# PinHeck.net
KiCad netlist of a schematic drawn in EAGLE
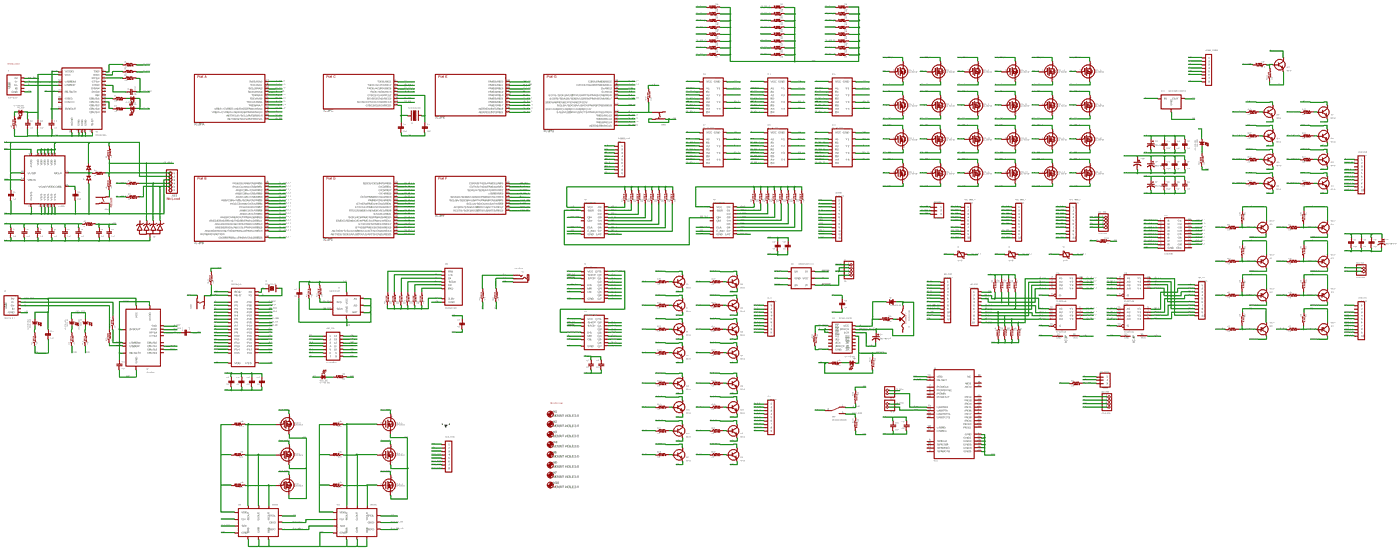
[diagram p0: schematic, sheet 1, overview]
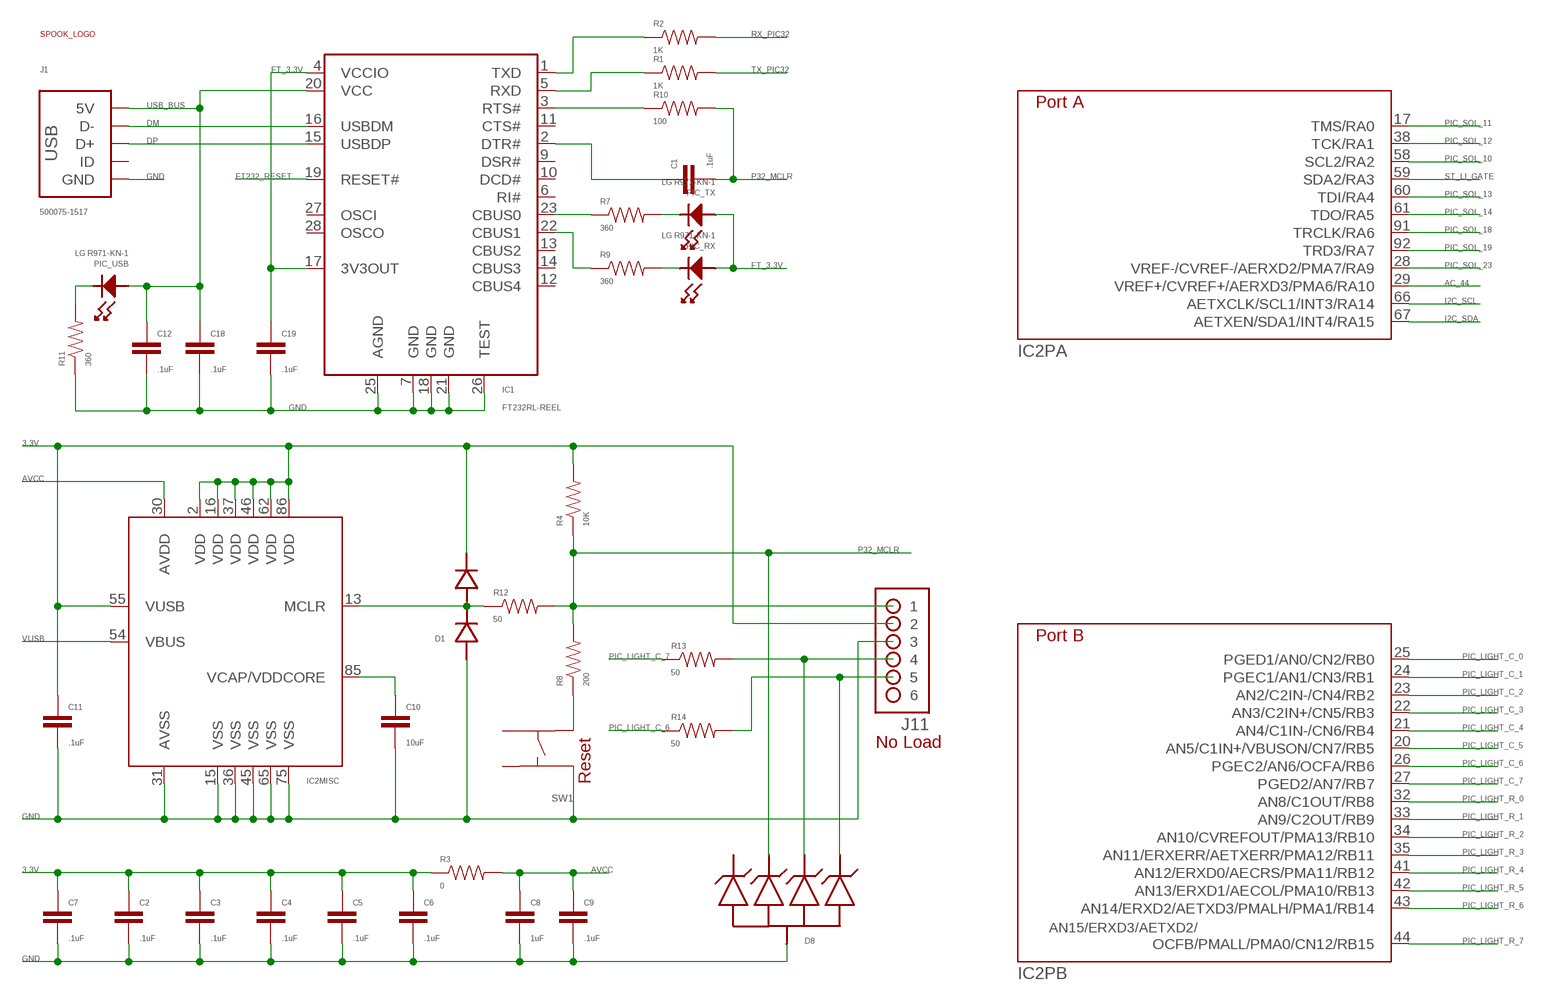
[diagram p1: schematic, sheet 1, part 1 of 9]
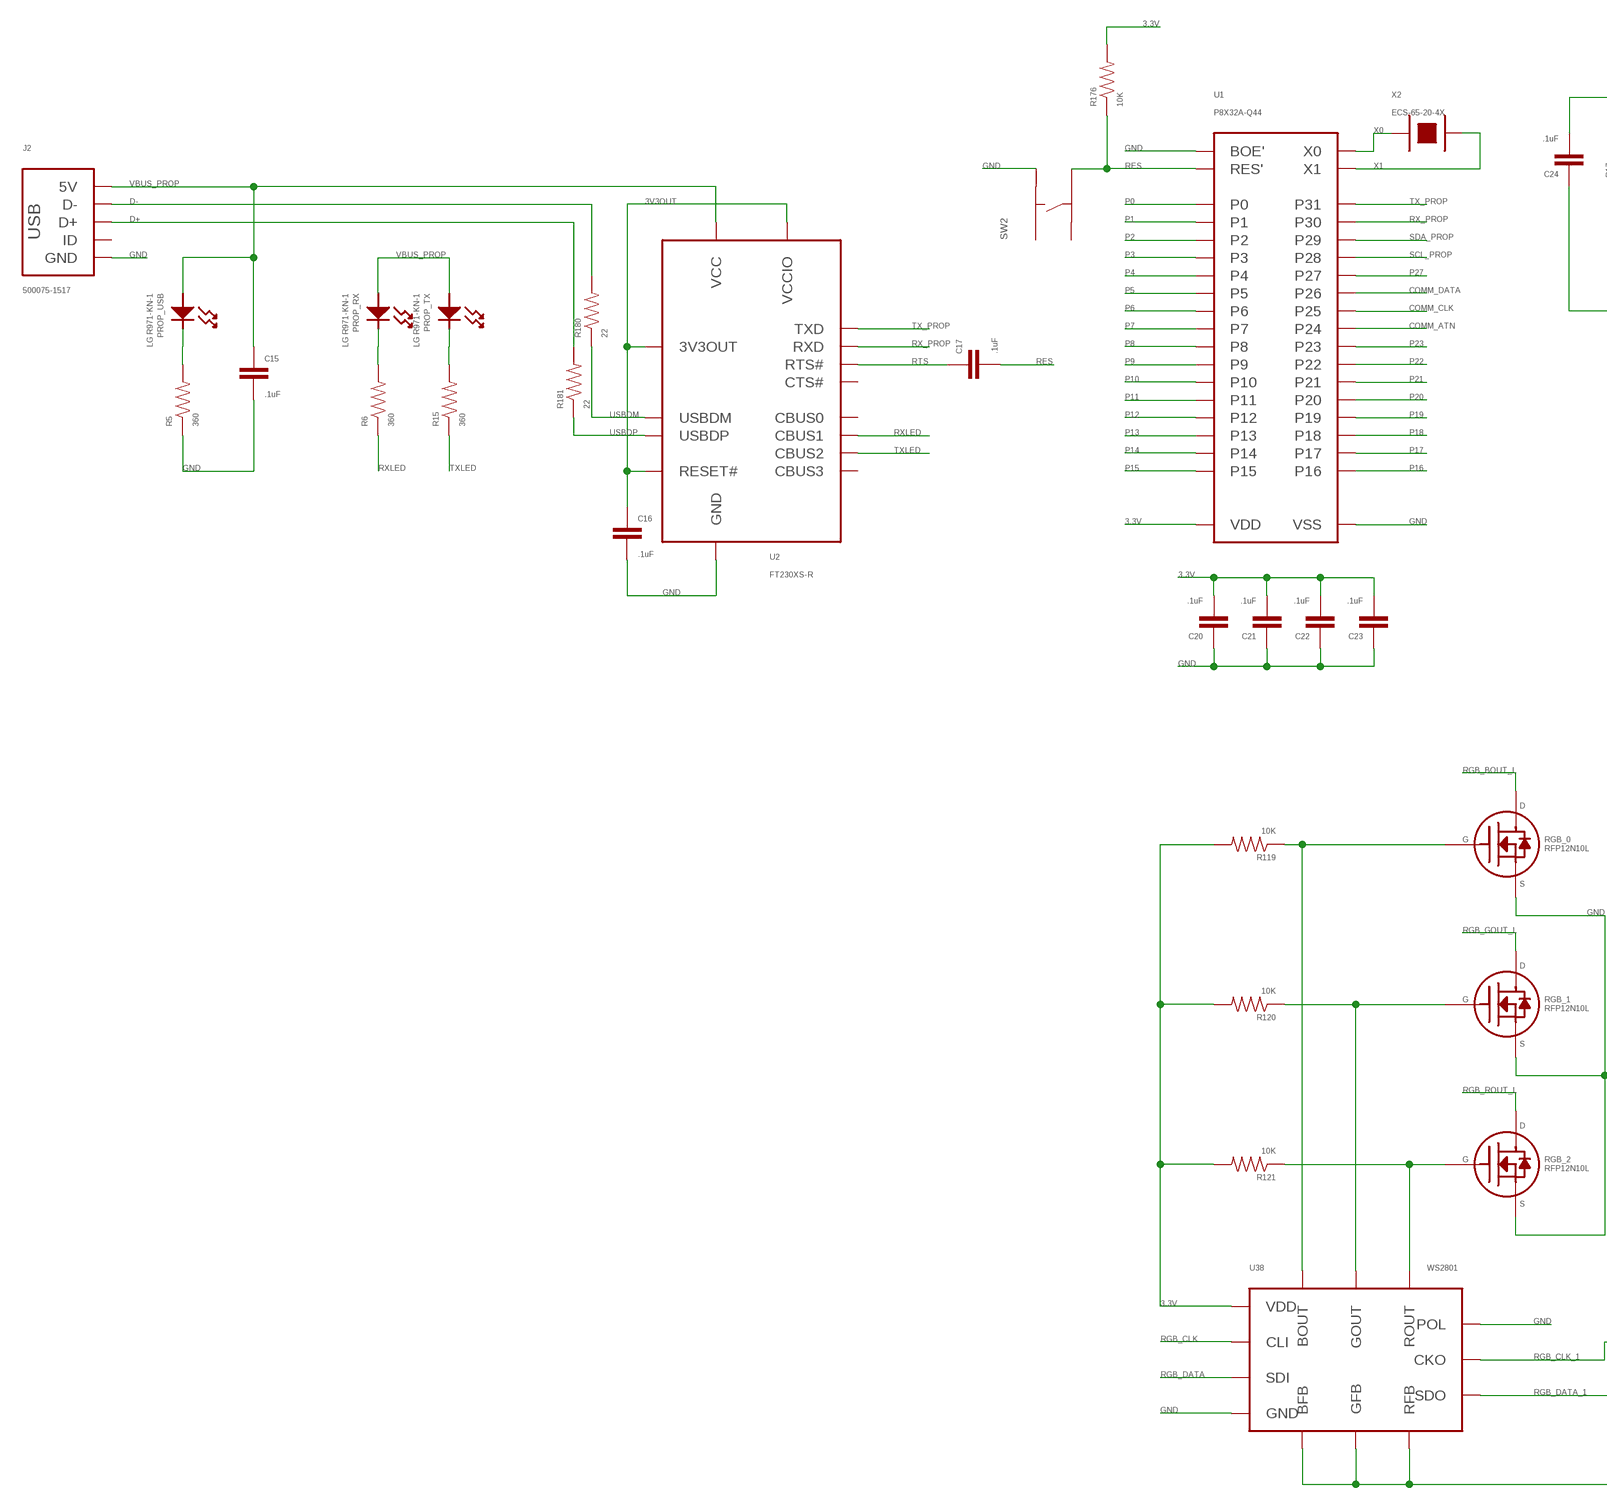
[diagram p2: schematic, sheet 1, part 2 of 9]
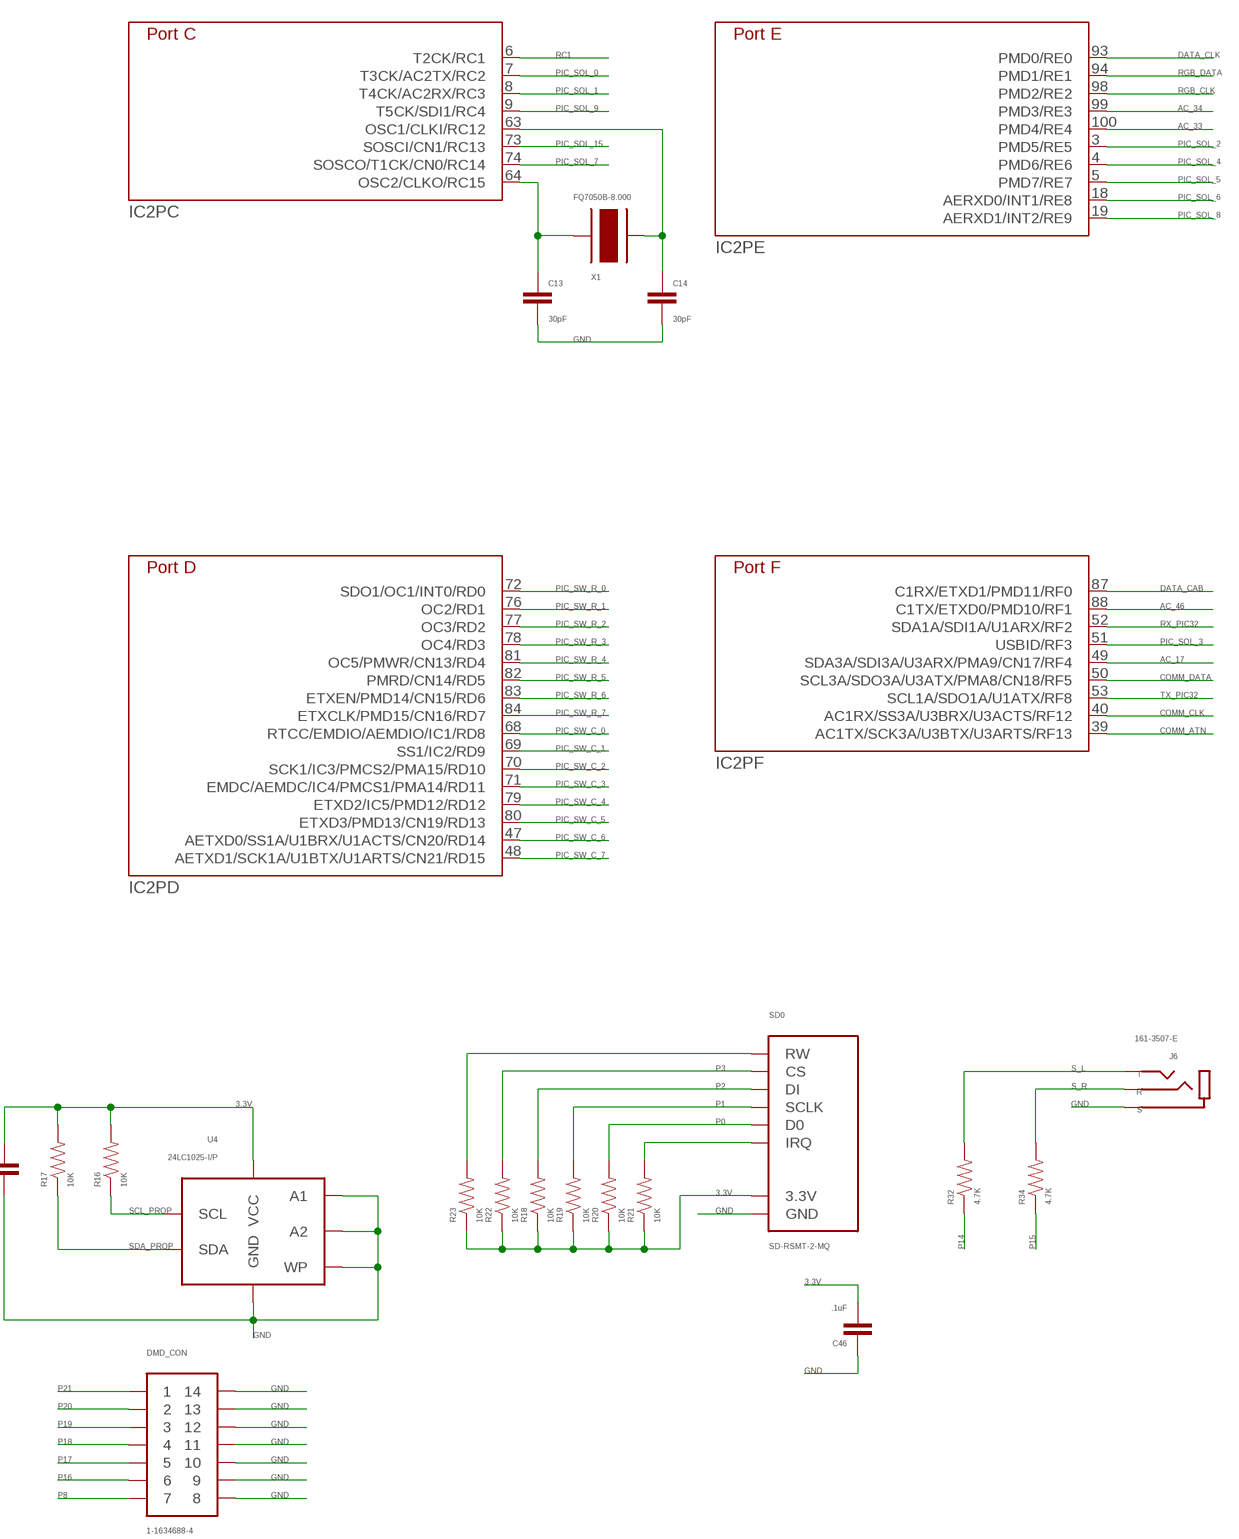
[diagram p3: schematic, sheet 1, part 3 of 9]
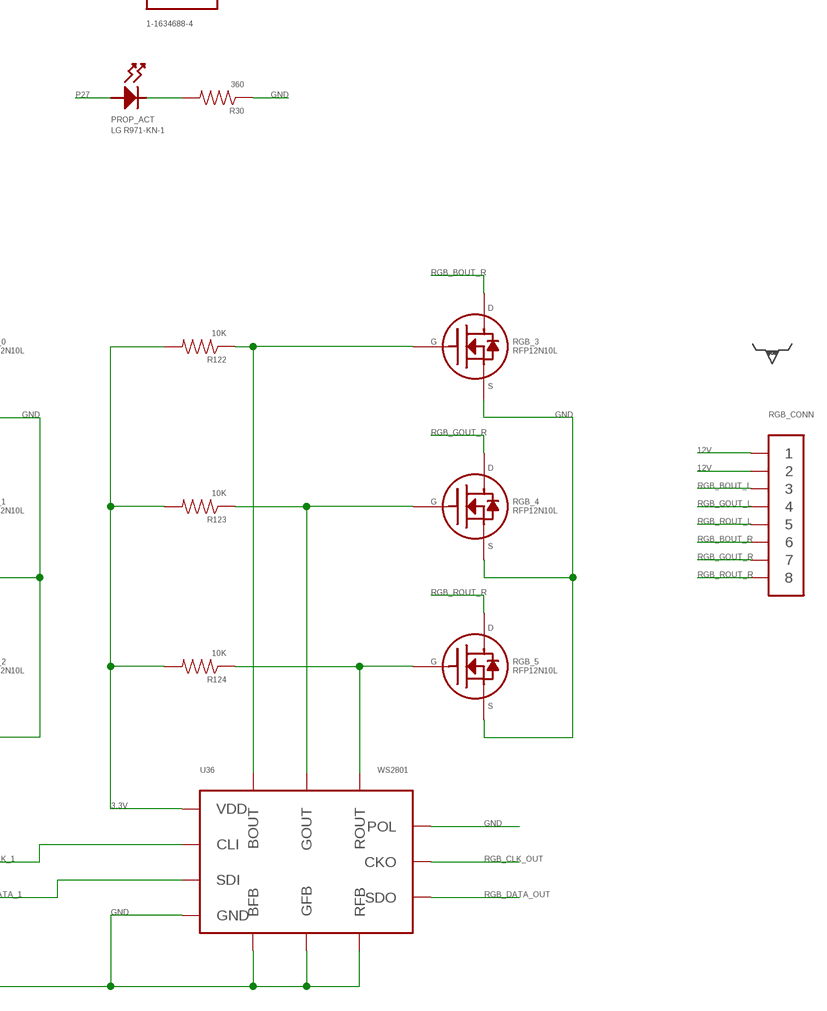
[diagram p4: schematic, sheet 1, part 4 of 9]
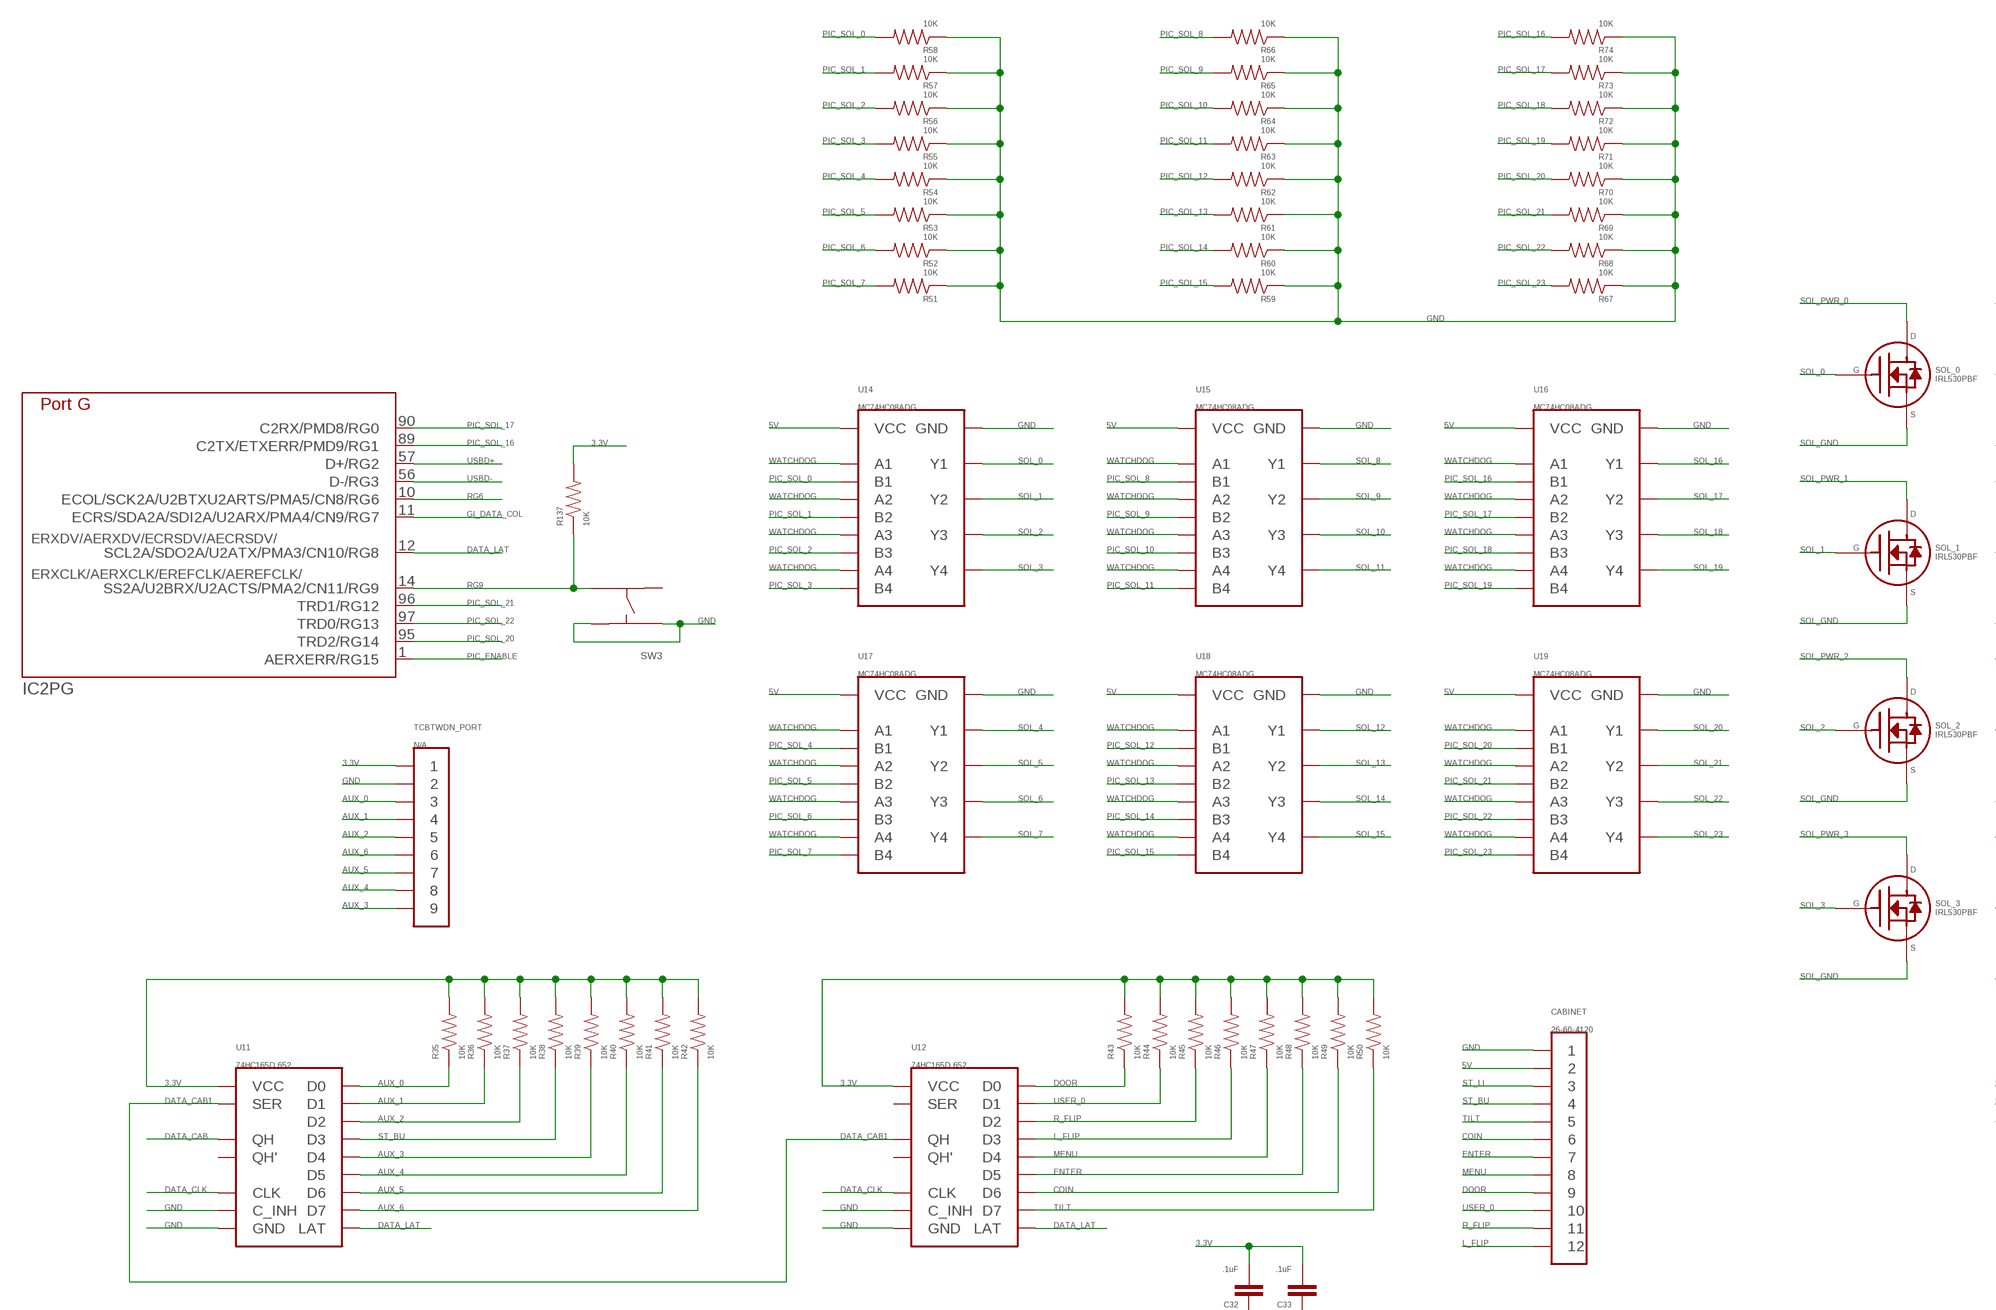
[diagram p5: schematic, sheet 1, part 5 of 9]
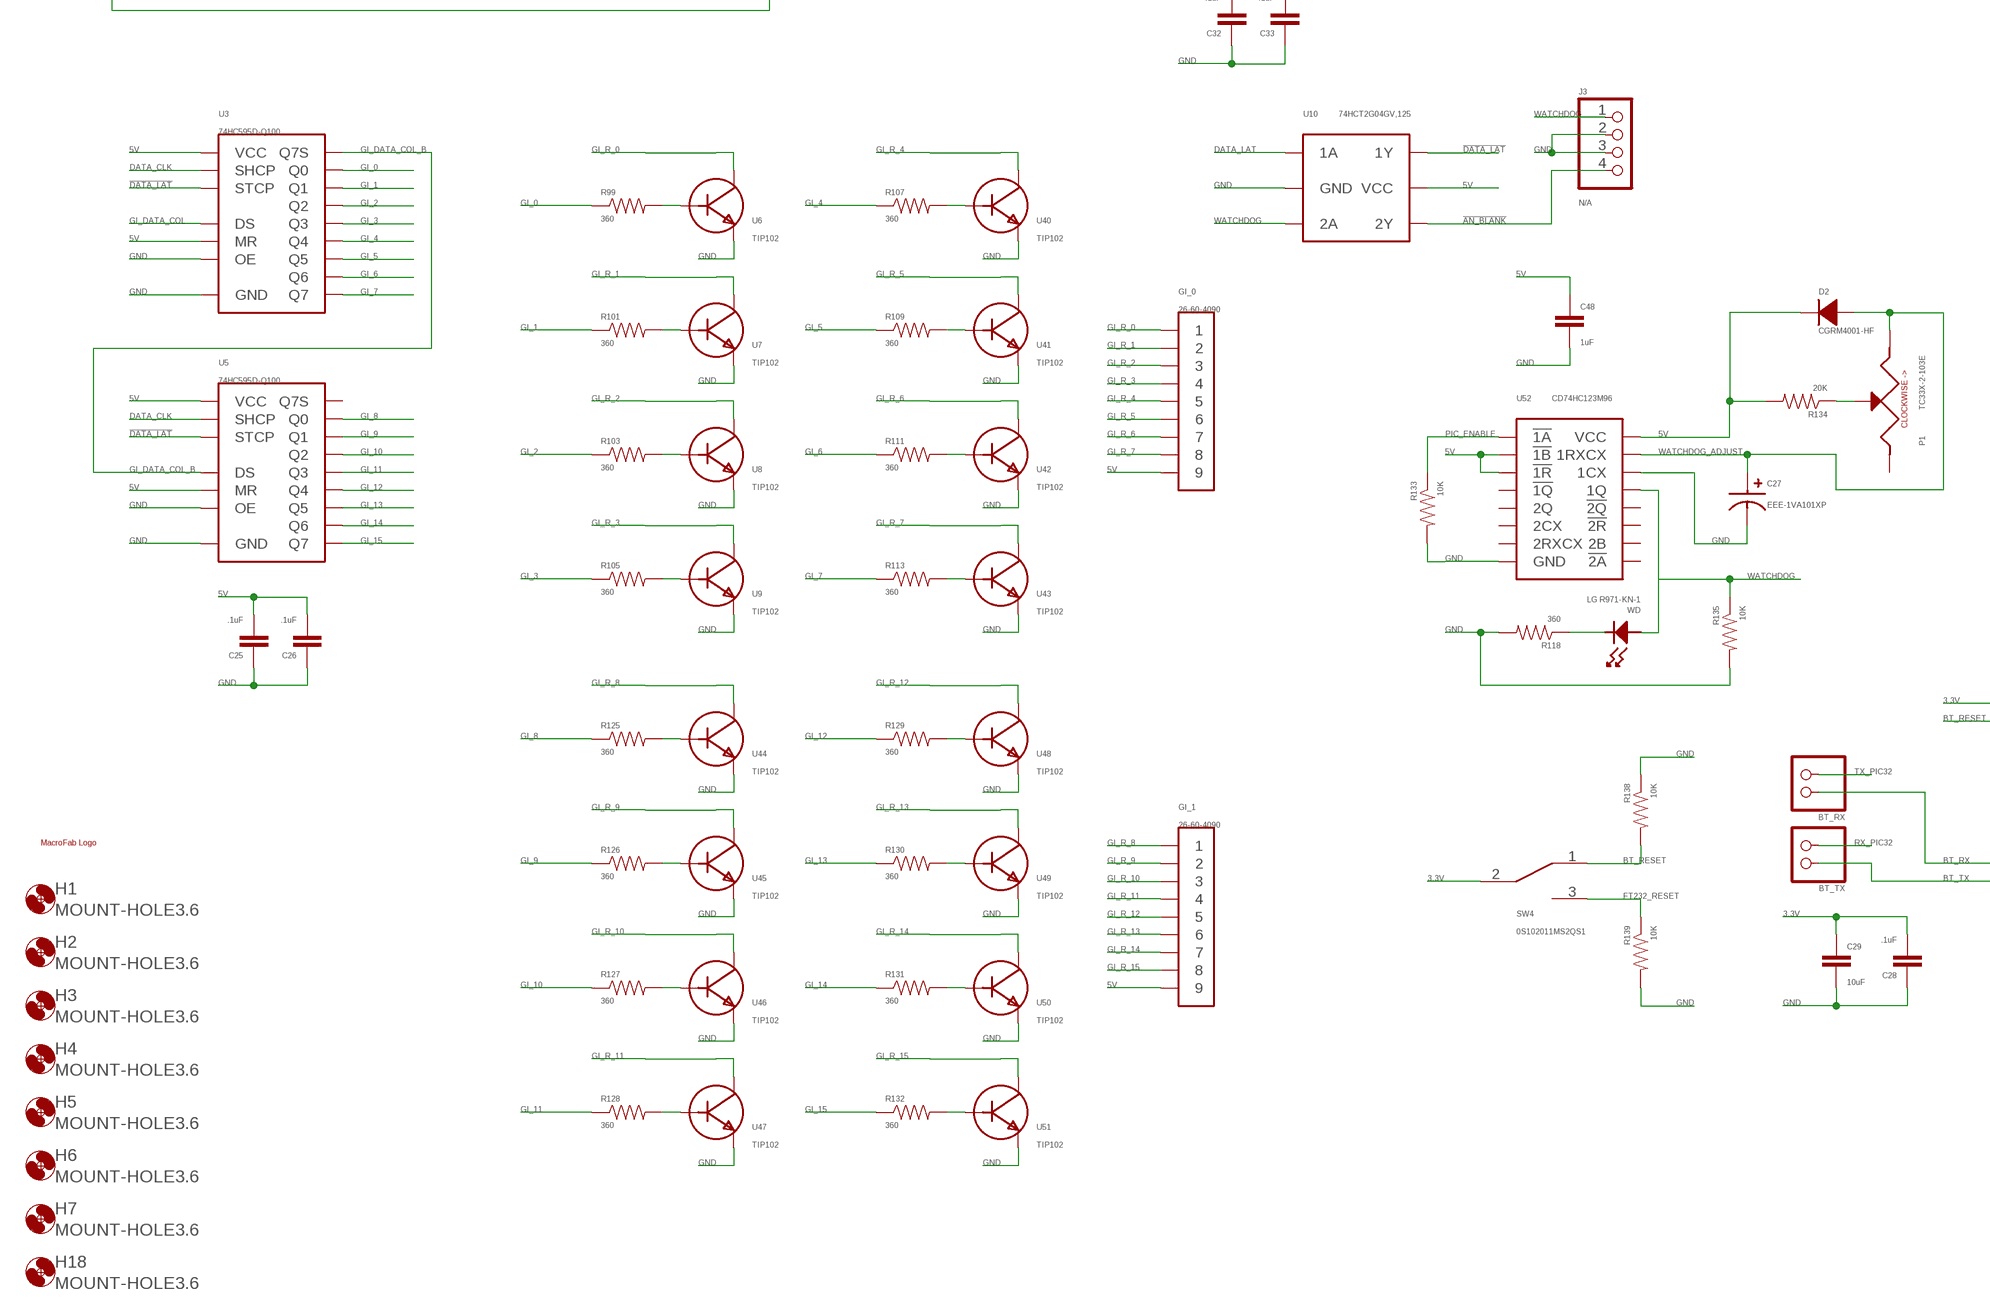
[diagram p6: schematic, sheet 1, part 6 of 9]
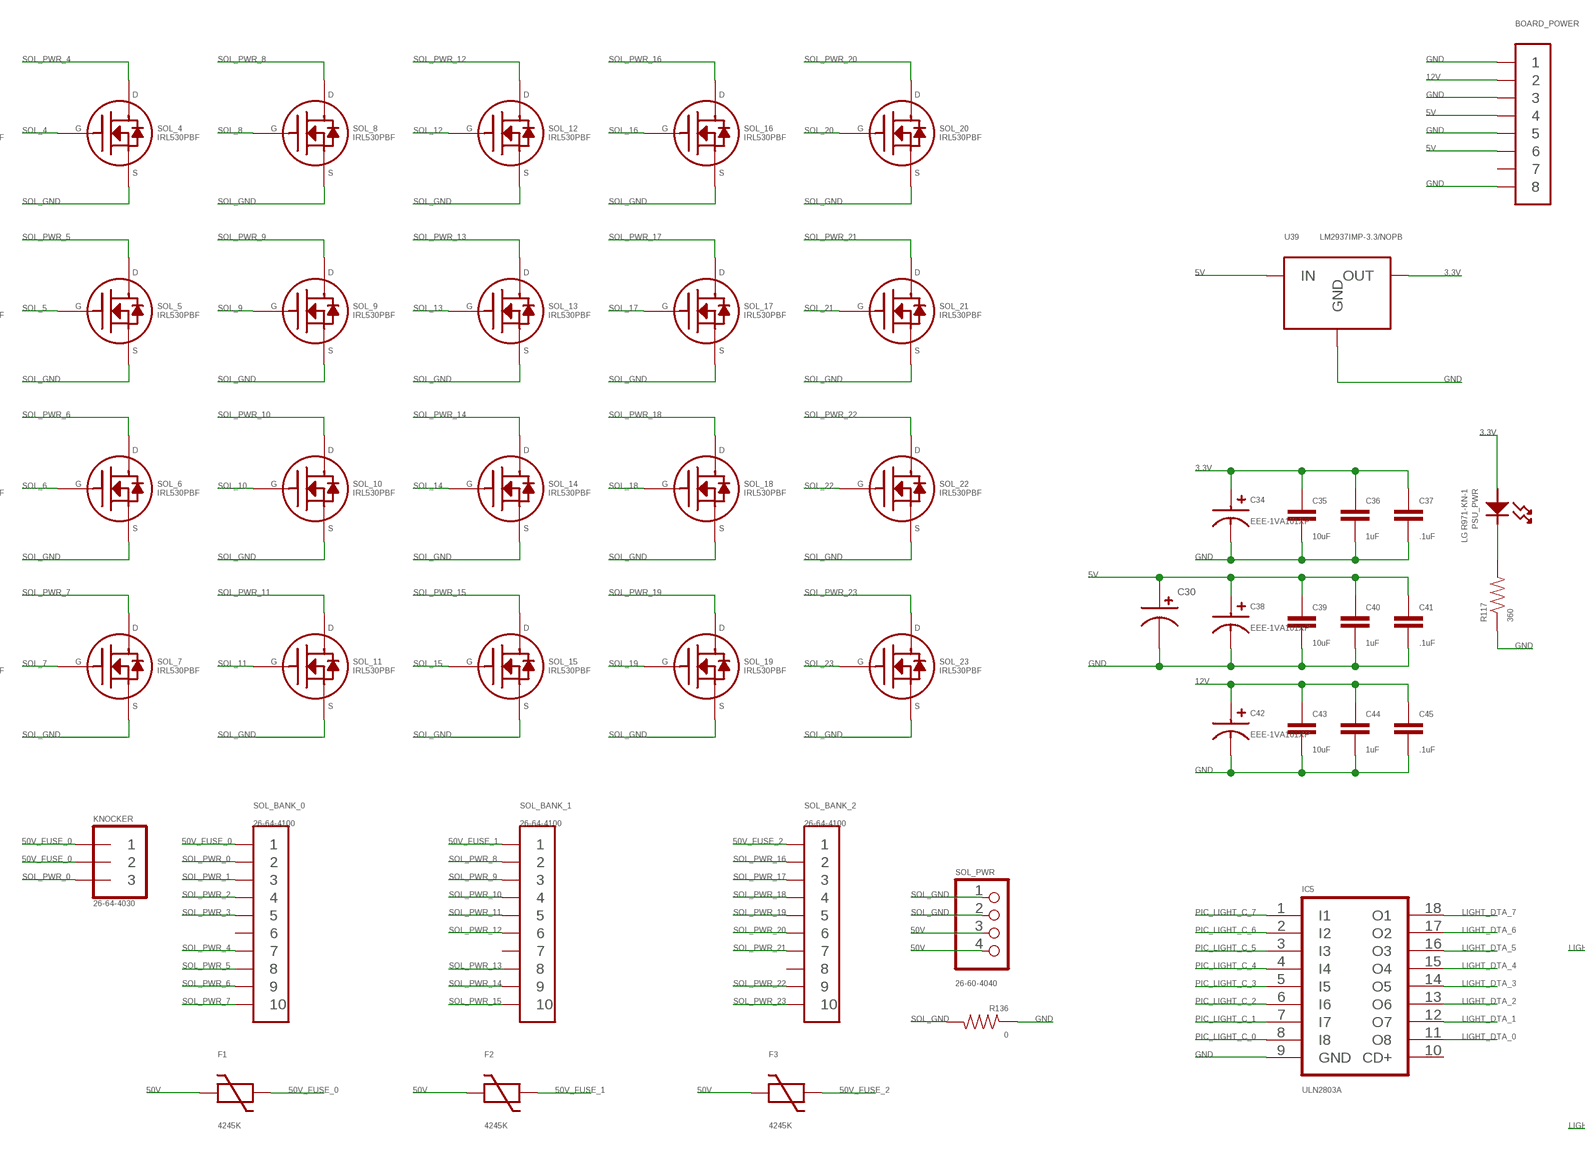
[diagram p7: schematic, sheet 1, part 7 of 9]
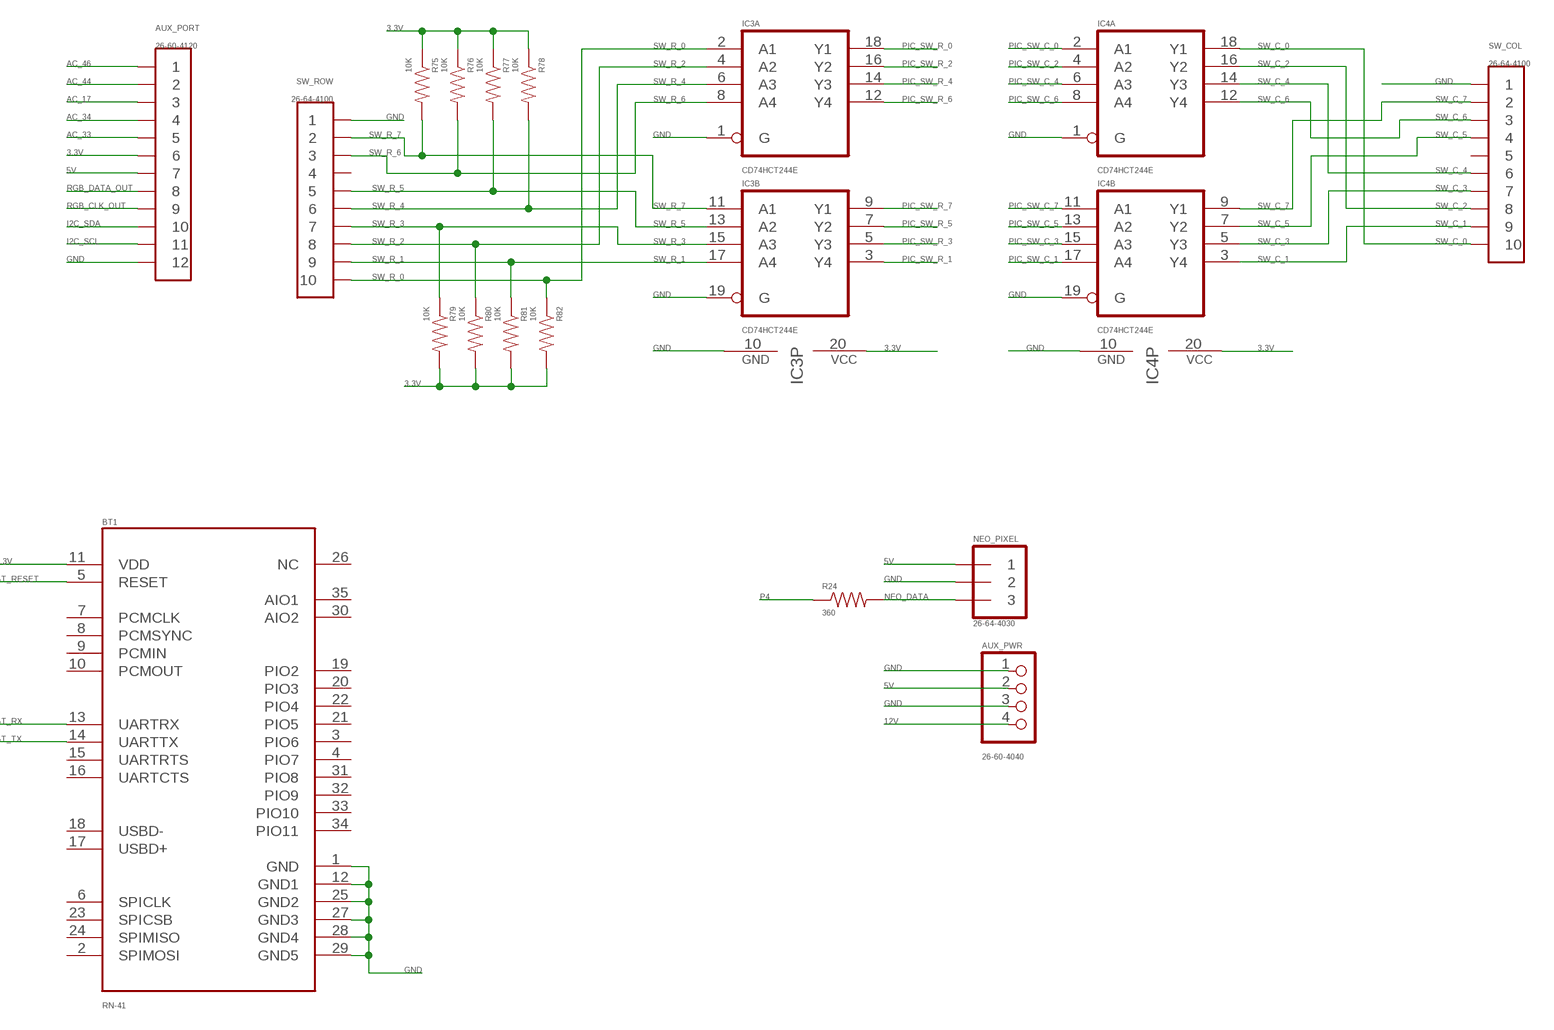
[diagram p8: schematic, sheet 1, part 8 of 9]
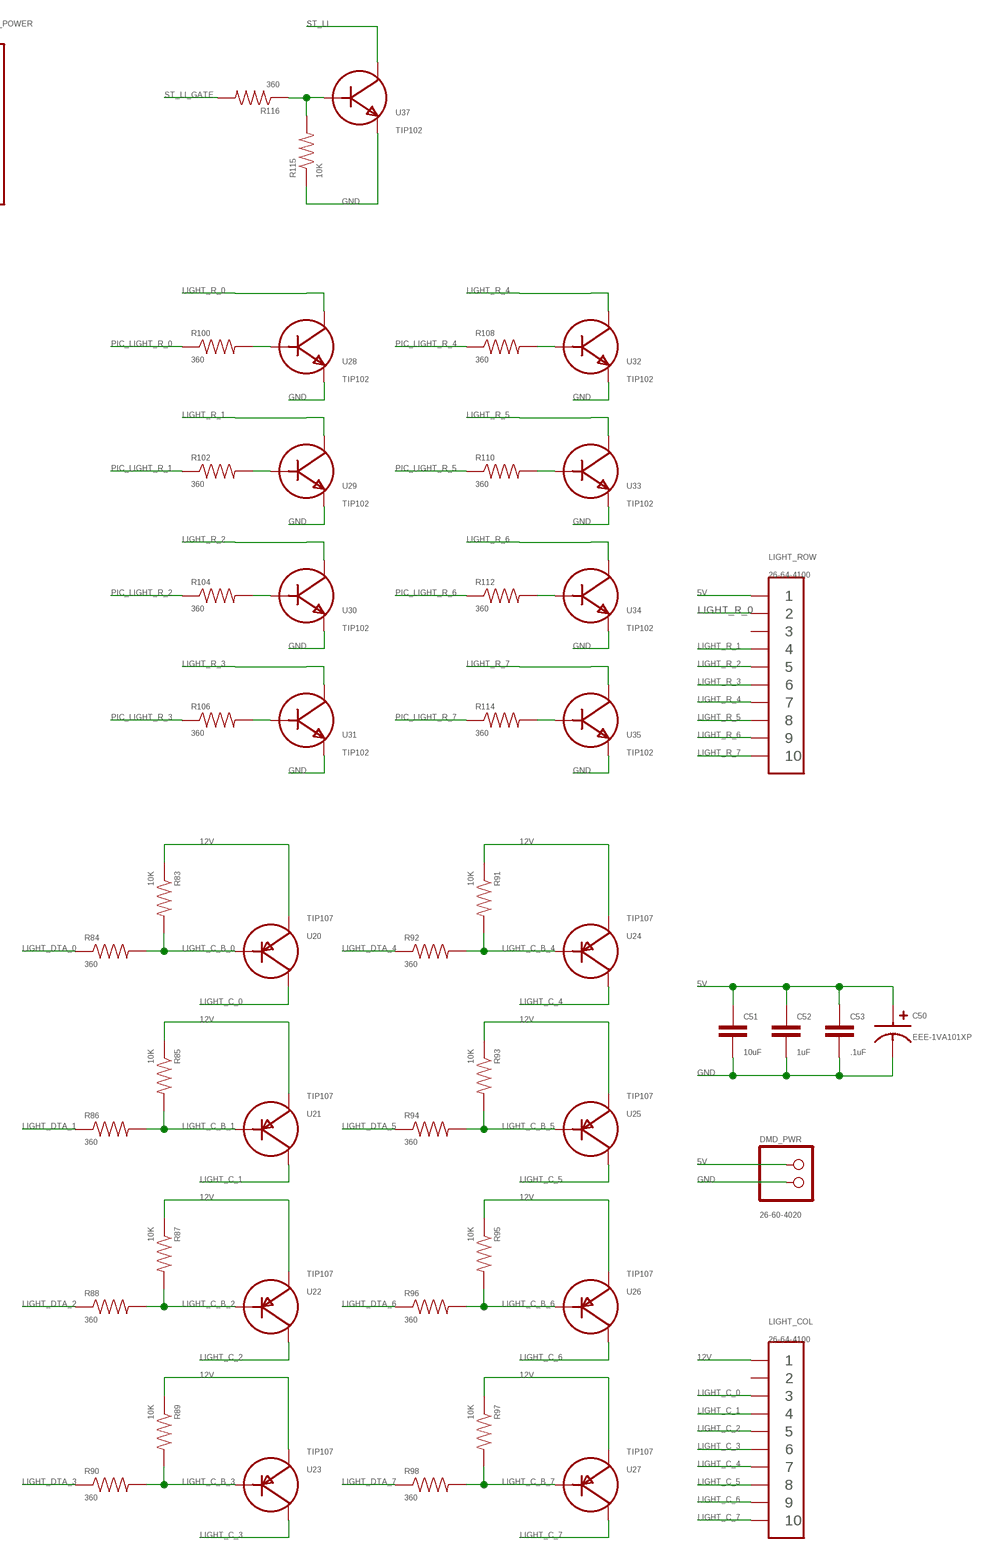
[diagram p9: schematic, sheet 1, part 9 of 9]

(export (version "E")
  (design (tool "Eeschema 10.0.6"))
  (components
    (comp (ref "AUX_PORT")
      (value "26-60-4120")
      (footprint "eagle-import:MOLEX_KK_12")
      (libsource (lib "eagle-import") (part "PH_1X12KK_12"))
    )
    (comp (ref "AUX_PWR")
      (value "26-60-4040")
      (footprint "eagle-import:MOLEX_KK_4")
      (libsource (lib "eagle-import") (part "PH_1X04KK_4"))
    )
    (comp (ref "BOARD_POWER")
      (value "PH_1X08MOLEX_KK_8")
      (footprint "eagle-import:MOLEX_KK_8")
      (libsource (lib "eagle-import") (part "PH_1X08MOLEX_KK_8"))
    )
    (comp (ref "BT1")
      (value "RN-41")
      (footprint "eagle-import:RN-41")
      (libsource (lib "eagle-import") (part "RN-41RN-41"))
    )
    (comp (ref "BT_RX")
      (value "PH_1X02HEADER_PTH")
      (footprint "eagle-import:HEADER_01X02_PTH")
      (libsource (lib "eagle-import") (part "PH_1X02HEADER_PTH"))
    )
    (comp (ref "BT_TX")
      (value "PH_1X02HEADER_PTH")
      (footprint "eagle-import:HEADER_01X02_PTH")
      (libsource (lib "eagle-import") (part "PH_1X02HEADER_PTH"))
    )
    (comp (ref "C1")
      (value ".1uF")
      (footprint "eagle-import:0805")
      (libsource (lib "eagle-import") (part "CAPACITOR_NON_POLAR0805"))
    )
    (comp (ref "C2")
      (value ".1uF")
      (footprint "eagle-import:0805")
      (libsource (lib "eagle-import") (part "CAPACITOR_NON_POLAR0805"))
    )
    (comp (ref "C3")
      (value ".1uF")
      (footprint "eagle-import:0805")
      (libsource (lib "eagle-import") (part "CAPACITOR_NON_POLAR0805"))
    )
    (comp (ref "C4")
      (value ".1uF")
      (footprint "eagle-import:0805")
      (libsource (lib "eagle-import") (part "CAPACITOR_NON_POLAR0805"))
    )
    (comp (ref "C5")
      (value ".1uF")
      (footprint "eagle-import:0805")
      (libsource (lib "eagle-import") (part "CAPACITOR_NON_POLAR0805"))
    )
    (comp (ref "C6")
      (value ".1uF")
      (footprint "eagle-import:0805")
      (libsource (lib "eagle-import") (part "CAPACITOR_NON_POLAR0805"))
    )
    (comp (ref "C7")
      (value ".1uF")
      (footprint "eagle-import:0805")
      (libsource (lib "eagle-import") (part "CAPACITOR_NON_POLAR0805"))
    )
    (comp (ref "C8")
      (value "1uF")
      (footprint "eagle-import:0805")
      (libsource (lib "eagle-import") (part "CAPACITOR_NON_POLAR0805"))
    )
    (comp (ref "C9")
      (value ".1uF")
      (footprint "eagle-import:0805")
      (libsource (lib "eagle-import") (part "CAPACITOR_NON_POLAR0805"))
    )
    (comp (ref "C10")
      (value "10uF")
      (footprint "eagle-import:1206")
      (libsource (lib "eagle-import") (part "CAPACITOR_NON_POLAR1206"))
    )
    (comp (ref "C11")
      (value ".1uF")
      (footprint "eagle-import:0805")
      (libsource (lib "eagle-import") (part "CAPACITOR_NON_POLAR0805"))
    )
    (comp (ref "C12")
      (value ".1uF")
      (footprint "eagle-import:0805")
      (libsource (lib "eagle-import") (part "CAPACITOR_NON_POLAR0805"))
    )
    (comp (ref "C13")
      (value "30pF")
      (footprint "eagle-import:0805")
      (libsource (lib "eagle-import") (part "CAPACITOR_NON_POLAR0805"))
    )
    (comp (ref "C14")
      (value "30pF")
      (footprint "eagle-import:0805")
      (libsource (lib "eagle-import") (part "CAPACITOR_NON_POLAR0805"))
    )
    (comp (ref "C15")
      (value ".1uF")
      (footprint "eagle-import:0805")
      (libsource (lib "eagle-import") (part "CAPACITOR_NON_POLAR0805"))
    )
    (comp (ref "C16")
      (value ".1uF")
      (footprint "eagle-import:0805")
      (libsource (lib "eagle-import") (part "CAPACITOR_NON_POLAR0805"))
    )
    (comp (ref "C17")
      (value ".1uF")
      (footprint "eagle-import:0805")
      (libsource (lib "eagle-import") (part "CAPACITOR_NON_POLAR0805"))
    )
    (comp (ref "C18")
      (value ".1uF")
      (footprint "eagle-import:0805")
      (libsource (lib "eagle-import") (part "CAPACITOR_NON_POLAR0805"))
    )
    (comp (ref "C19")
      (value ".1uF")
      (footprint "eagle-import:0805")
      (libsource (lib "eagle-import") (part "CAPACITOR_NON_POLAR0805"))
    )
    (comp (ref "C20")
      (value ".1uF")
      (footprint "eagle-import:0805")
      (libsource (lib "eagle-import") (part "CAPACITOR_NON_POLAR0805"))
    )
    (comp (ref "C21")
      (value ".1uF")
      (footprint "eagle-import:0805")
      (libsource (lib "eagle-import") (part "CAPACITOR_NON_POLAR0805"))
    )
    (comp (ref "C22")
      (value ".1uF")
      (footprint "eagle-import:0805")
      (libsource (lib "eagle-import") (part "CAPACITOR_NON_POLAR0805"))
    )
    (comp (ref "C23")
      (value ".1uF")
      (footprint "eagle-import:0805")
      (libsource (lib "eagle-import") (part "CAPACITOR_NON_POLAR0805"))
    )
    (comp (ref "C24")
      (value ".1uF")
      (footprint "eagle-import:0805")
      (libsource (lib "eagle-import") (part "CAPACITOR_NON_POLAR0805"))
    )
    (comp (ref "C25")
      (value ".1uF")
      (footprint "eagle-import:0805")
      (libsource (lib "eagle-import") (part "CAPACITOR_NON_POLAR0805"))
    )
    (comp (ref "C26")
      (value ".1uF")
      (footprint "eagle-import:0805")
      (libsource (lib "eagle-import") (part "CAPACITOR_NON_POLAR0805"))
    )
    (comp (ref "C27")
      (value "EEE-1VA101XP")
      (footprint "eagle-import:6.3MM_CAP_SMD")
      (libsource (lib "eagle-import") (part "CAPACITOR_POLARIZED6.3MM_SMD"))
    )
    (comp (ref "C28")
      (value ".1uF")
      (footprint "eagle-import:0805")
      (libsource (lib "eagle-import") (part "CAPACITOR_NON_POLAR0805"))
    )
    (comp (ref "C29")
      (value "10uF")
      (footprint "eagle-import:1206")
      (libsource (lib "eagle-import") (part "CAPACITOR_NON_POLAR1206"))
    )
    (comp (ref "C30")
      (value "CAPACITOR_P_12.5MM")
      (footprint "eagle-import:CP12.5MM")
      (libsource (lib "eagle-import") (part "CAPACITOR_P_12.5MM"))
    )
    (comp (ref "C32")
      (value ".1uF")
      (footprint "eagle-import:0805")
      (libsource (lib "eagle-import") (part "CAPACITOR_NON_POLAR0805"))
    )
    (comp (ref "C33")
      (value ".1uF")
      (footprint "eagle-import:0805")
      (libsource (lib "eagle-import") (part "CAPACITOR_NON_POLAR0805"))
    )
    (comp (ref "C34")
      (value "EEE-1VA101XP")
      (footprint "eagle-import:6.3MM_CAP_SMD")
      (libsource (lib "eagle-import") (part "CAPACITOR_POLARIZED6.3MM_SMD"))
    )
    (comp (ref "C35")
      (value "10uF")
      (footprint "eagle-import:1206")
      (libsource (lib "eagle-import") (part "CAPACITOR_NON_POLAR1206"))
    )
    (comp (ref "C36")
      (value "1uF")
      (footprint "eagle-import:0805")
      (libsource (lib "eagle-import") (part "CAPACITOR_NON_POLAR0805"))
    )
    (comp (ref "C37")
      (value ".1uF")
      (footprint "eagle-import:0805")
      (libsource (lib "eagle-import") (part "CAPACITOR_NON_POLAR0805"))
    )
    (comp (ref "C38")
      (value "EEE-1VA101XP")
      (footprint "eagle-import:6.3MM_CAP_SMD")
      (libsource (lib "eagle-import") (part "CAPACITOR_POLARIZED6.3MM_SMD"))
    )
    (comp (ref "C39")
      (value "10uF")
      (footprint "eagle-import:1206")
      (libsource (lib "eagle-import") (part "CAPACITOR_NON_POLAR1206"))
    )
    (comp (ref "C40")
      (value "1uF")
      (footprint "eagle-import:0805")
      (libsource (lib "eagle-import") (part "CAPACITOR_NON_POLAR0805"))
    )
    (comp (ref "C41")
      (value ".1uF")
      (footprint "eagle-import:0805")
      (libsource (lib "eagle-import") (part "CAPACITOR_NON_POLAR0805"))
    )
    (comp (ref "C42")
      (value "EEE-1VA101XP")
      (footprint "eagle-import:6.3MM_CAP_SMD")
      (libsource (lib "eagle-import") (part "CAPACITOR_POLARIZED6.3MM_SMD"))
    )
    (comp (ref "C43")
      (value "10uF")
      (footprint "eagle-import:1206")
      (libsource (lib "eagle-import") (part "CAPACITOR_NON_POLAR1206"))
    )
    (comp (ref "C44")
      (value "1uF")
      (footprint "eagle-import:0805")
      (libsource (lib "eagle-import") (part "CAPACITOR_NON_POLAR0805"))
    )
    (comp (ref "C45")
      (value ".1uF")
      (footprint "eagle-import:0805")
      (libsource (lib "eagle-import") (part "CAPACITOR_NON_POLAR0805"))
    )
    (comp (ref "C46")
      (value ".1uF")
      (footprint "eagle-import:0805")
      (libsource (lib "eagle-import") (part "CAPACITOR_NON_POLAR0805"))
    )
    (comp (ref "C48")
      (value "1uF")
      (footprint "eagle-import:0805")
      (libsource (lib "eagle-import") (part "CAPACITOR_NON_POLAR0805"))
    )
    (comp (ref "C50")
      (value "EEE-1VA101XP")
      (footprint "eagle-import:6.3MM_CAP_SMD")
      (libsource (lib "eagle-import") (part "CAPACITOR_POLARIZED6.3MM_SMD"))
    )
    (comp (ref "C51")
      (value "10uF")
      (footprint "eagle-import:1206")
      (libsource (lib "eagle-import") (part "CAPACITOR_NON_POLAR1206"))
    )
    (comp (ref "C52")
      (value "1uF")
      (footprint "eagle-import:0805")
      (libsource (lib "eagle-import") (part "CAPACITOR_NON_POLAR0805"))
    )
    (comp (ref "C53")
      (value ".1uF")
      (footprint "eagle-import:0805")
      (libsource (lib "eagle-import") (part "CAPACITOR_NON_POLAR0805"))
    )
    (comp (ref "CABINET")
      (value "26-60-4120")
      (footprint "eagle-import:MOLEX_KK_12")
      (libsource (lib "eagle-import") (part "PH_1X12KK_12"))
    )
    (comp (ref "D1")
      (value "BAV99W,115")
      (footprint "eagle-import:SOT-323")
      (libsource (lib "eagle-import") (part "BAV99W"))
    )
    (comp (ref "D2")
      (value "CGRM4001-HF")
      (footprint "eagle-import:SOD-123")
      (libsource (lib "eagle-import") (part "DIODESOD-123"))
    )
    (comp (ref "D8")
      (value "NSQA6V8AW5T2G")
      (footprint "eagle-import:SOT-323-5")
      (libsource (lib "eagle-import") (part "NSQA6V8"))
    )
    (comp (ref "DMD_CON")
      (value "1-1634688-4")
      (footprint "eagle-import:HEADER_02X07_PTH")
      (libsource (lib "eagle-import") (part "PH_2X07PTH"))
    )
    (comp (ref "DMD_PWR")
      (value "26-60-4020")
      (footprint "eagle-import:MOLEX_KK_2")
      (libsource (lib "eagle-import") (part "PH_1X02MOLEX_26-61-4020"))
    )
    (comp (ref "F1")
      (value "4245K")
      (footprint "eagle-import:4245K")
      (libsource (lib "eagle-import") (part "PTC_FUSE4245K"))
    )
    (comp (ref "F2")
      (value "4245K")
      (footprint "eagle-import:4245K")
      (libsource (lib "eagle-import") (part "PTC_FUSE4245K"))
    )
    (comp (ref "F3")
      (value "4245K")
      (footprint "eagle-import:4245K")
      (libsource (lib "eagle-import") (part "PTC_FUSE4245K"))
    )
    (comp (ref "GI_0")
      (value "26-60-4090")
      (footprint "eagle-import:MOLEX_KK_9")
      (libsource (lib "eagle-import") (part "PH_1X09MOLEX_KK_9"))
    )
    (comp (ref "GI_1")
      (value "26-60-4090")
      (footprint "eagle-import:MOLEX_KK_9")
      (libsource (lib "eagle-import") (part "PH_1X09MOLEX_KK_9"))
    )
    (comp (ref "H1")
      (value "MOUNT-HOLE3.6")
      (footprint "eagle-import:3,6")
      (libsource (lib "eagle-import") (part "MOUNT-HOLE3.6"))
    )
    (comp (ref "H2")
      (value "MOUNT-HOLE3.6")
      (footprint "eagle-import:3,6")
      (libsource (lib "eagle-import") (part "MOUNT-HOLE3.6"))
    )
    (comp (ref "H3")
      (value "MOUNT-HOLE3.6")
      (footprint "eagle-import:3,6")
      (libsource (lib "eagle-import") (part "MOUNT-HOLE3.6"))
    )
    (comp (ref "H4")
      (value "MOUNT-HOLE3.6")
      (footprint "eagle-import:3,6")
      (libsource (lib "eagle-import") (part "MOUNT-HOLE3.6"))
    )
    (comp (ref "H5")
      (value "MOUNT-HOLE3.6")
      (footprint "eagle-import:3,6")
      (libsource (lib "eagle-import") (part "MOUNT-HOLE3.6"))
    )
    (comp (ref "H6")
      (value "MOUNT-HOLE3.6")
      (footprint "eagle-import:3,6")
      (libsource (lib "eagle-import") (part "MOUNT-HOLE3.6"))
    )
    (comp (ref "H7")
      (value "MOUNT-HOLE3.6")
      (footprint "eagle-import:3,6")
      (libsource (lib "eagle-import") (part "MOUNT-HOLE3.6"))
    )
    (comp (ref "H18")
      (value "MOUNT-HOLE3.6")
      (footprint "eagle-import:3,6")
      (libsource (lib "eagle-import") (part "MOUNT-HOLE3.6"))
    )
    (comp (ref "IC1")
      (value "FT232RL-REEL")
      (footprint "eagle-import:SSOP28L")
      (libsource (lib "eagle-import") (part "FT232RL"))
    )
    (comp (ref "IC2")
      (value "PIC32MX795F512L-80I/PT")
      (footprint "eagle-import:TQ100-PT")
      (libsource (lib "eagle-import") (part "PIC32MX7X5FL-PT"))
    )
    (comp (ref "IC3")
      (value "CD74HCT244E")
      (footprint "eagle-import:DIL20")
      (libsource (lib "eagle-import") (part "74244NLS"))
    )
    (comp (ref "IC4")
      (value "CD74HCT244E")
      (footprint "eagle-import:DIL20")
      (libsource (lib "eagle-import") (part "74244NLS"))
    )
    (comp (ref "IC5")
      (value "ULN2803A")
      (footprint "eagle-import:DIL18")
      (libsource (lib "eagle-import") (part "ULN2803A"))
    )
    (comp (ref "J1")
      (value "500075-1517")
      (footprint "eagle-import:500075-1517")
      (libsource (lib "eagle-import") (part "USB500075-1517"))
    )
    (comp (ref "J2")
      (value "500075-1517")
      (footprint "eagle-import:500075-1517")
      (libsource (lib "eagle-import") (part "USB500075-1517"))
    )
    (comp (ref "J3")
      (value "N/A")
      (footprint "eagle-import:HEADER_01X04_PTH")
      (libsource (lib "eagle-import") (part "PH_1X04HEADER_PTH"))
    )
    (comp (ref "J6")
      (value "161-3507-E")
      (footprint "eagle-import:161-3507-E")
      (libsource (lib "eagle-import") (part "TRS_JACK161-3507-E"))
    )
    (comp (ref "J11")
      (value "No Load")
      (footprint "eagle-import:HDR-1X6_OFFSET")
      (libsource (lib "eagle-import") (part "HDR-1X6-OFFSET"))
    )
    (comp (ref "KNOCKER")
      (value "26-64-4030")
      (footprint "eagle-import:MOLEX_KK_3")
      (libsource (lib "eagle-import") (part "PH_1X03KK_3"))
    )
    (comp (ref "LIGHT_COL")
      (value "26-64-4100")
      (footprint "eagle-import:MOLEX_KK_10")
      (libsource (lib "eagle-import") (part "PH_1X10KK_10"))
    )
    (comp (ref "LIGHT_ROW")
      (value "26-64-4100")
      (footprint "eagle-import:MOLEX_KK_10")
      (libsource (lib "eagle-import") (part "PH_1X10KK_10"))
    )
    (comp (ref "LOGO1")
      (value "SPOOKY_LOGOSPOOKY_LOGO")
      (footprint "eagle-import:SPOOKY_LOGO")
      (libsource (lib "eagle-import") (part "SPOOKY_LOGOSPOOKY_LOGO"))
    )
    (comp (ref "NEO_PIXEL")
      (value "26-64-4030")
      (footprint "eagle-import:MOLEX_KK_3")
      (libsource (lib "eagle-import") (part "PH_1X03KK_3"))
    )
    (comp (ref "P1")
      (value "TC33X-2-103E")
      (footprint "eagle-import:TC33_TRIMMER")
      (libsource (lib "eagle-import") (part "TC33X-1TC33X-1"))
    )
    (comp (ref "PIC_RX")
      (value "LG R971-KN-1")
      (footprint "eagle-import:LED_0805")
      (libsource (lib "eagle-import") (part "LED_SINGLE0805"))
    )
    (comp (ref "PIC_TX")
      (value "LG R971-KN-1")
      (footprint "eagle-import:LED_0805")
      (libsource (lib "eagle-import") (part "LED_SINGLE0805"))
    )
    (comp (ref "PIC_USB")
      (value "LG R971-KN-1")
      (footprint "eagle-import:LED_0805")
      (libsource (lib "eagle-import") (part "LED_SINGLE0805"))
    )
    (comp (ref "PROP_ACT")
      (value "LG R971-KN-1")
      (footprint "eagle-import:LED_0805")
      (libsource (lib "eagle-import") (part "LED_SINGLE0805"))
    )
    (comp (ref "PROP_RX")
      (value "LG R971-KN-1")
      (footprint "eagle-import:LED_0805")
      (libsource (lib "eagle-import") (part "LED_SINGLE0805"))
    )
    (comp (ref "PROP_TX")
      (value "LG R971-KN-1")
      (footprint "eagle-import:LED_0805")
      (libsource (lib "eagle-import") (part "LED_SINGLE0805"))
    )
    (comp (ref "PROP_USB")
      (value "LG R971-KN-1")
      (footprint "eagle-import:LED_0805")
      (libsource (lib "eagle-import") (part "LED_SINGLE0805"))
    )
    (comp (ref "PSU_PWR")
      (value "LG R971-KN-1")
      (footprint "eagle-import:LED_0805")
      (libsource (lib "eagle-import") (part "LED_SINGLE0805"))
    )
    (comp (ref "R1")
      (value "1K")
      (footprint "eagle-import:0805")
      (libsource (lib "eagle-import") (part "RESISTOR0805"))
    )
    (comp (ref "R2")
      (value "1K")
      (footprint "eagle-import:0805")
      (libsource (lib "eagle-import") (part "RESISTOR0805"))
    )
    (comp (ref "R3")
      (value "0")
      (footprint "eagle-import:0805")
      (libsource (lib "eagle-import") (part "RESISTOR0805"))
    )
    (comp (ref "R4")
      (value "10K")
      (footprint "eagle-import:0805")
      (libsource (lib "eagle-import") (part "RESISTOR0805"))
    )
    (comp (ref "R5")
      (value "360")
      (footprint "eagle-import:0805")
      (libsource (lib "eagle-import") (part "RESISTOR0805"))
    )
    (comp (ref "R6")
      (value "360")
      (footprint "eagle-import:0805")
      (libsource (lib "eagle-import") (part "RESISTOR0805"))
    )
    (comp (ref "R7")
      (value "360")
      (footprint "eagle-import:0805")
      (libsource (lib "eagle-import") (part "RESISTOR0805"))
    )
    (comp (ref "R8")
      (value "200")
      (footprint "eagle-import:0805")
      (libsource (lib "eagle-import") (part "RESISTOR0805"))
    )
    (comp (ref "R9")
      (value "360")
      (footprint "eagle-import:0805")
      (libsource (lib "eagle-import") (part "RESISTOR0805"))
    )
    (comp (ref "R10")
      (value "100")
      (footprint "eagle-import:0805")
      (libsource (lib "eagle-import") (part "RESISTOR0805"))
    )
    (comp (ref "R11")
      (value "360")
      (footprint "eagle-import:0805")
      (libsource (lib "eagle-import") (part "RESISTOR0805"))
    )
    (comp (ref "R12")
      (value "50")
      (footprint "eagle-import:0805")
      (libsource (lib "eagle-import") (part "RESISTOR0805"))
    )
    (comp (ref "R13")
      (value "50")
      (footprint "eagle-import:0805")
      (libsource (lib "eagle-import") (part "RESISTOR0805"))
    )
    (comp (ref "R14")
      (value "50")
      (footprint "eagle-import:0805")
      (libsource (lib "eagle-import") (part "RESISTOR0805"))
    )
    (comp (ref "R15")
      (value "360")
      (footprint "eagle-import:0805")
      (libsource (lib "eagle-import") (part "RESISTOR0805"))
    )
    (comp (ref "R16")
      (value "10K")
      (footprint "eagle-import:0805")
      (libsource (lib "eagle-import") (part "RESISTOR0805"))
    )
    (comp (ref "R17")
      (value "10K")
      (footprint "eagle-import:0805")
      (libsource (lib "eagle-import") (part "RESISTOR0805"))
    )
    (comp (ref "R18")
      (value "10K")
      (footprint "eagle-import:0805")
      (libsource (lib "eagle-import") (part "RESISTOR0805"))
    )
    (comp (ref "R19")
      (value "10K")
      (footprint "eagle-import:0805")
      (libsource (lib "eagle-import") (part "RESISTOR0805"))
    )
    (comp (ref "R20")
      (value "10K")
      (footprint "eagle-import:0805")
      (libsource (lib "eagle-import") (part "RESISTOR0805"))
    )
    (comp (ref "R21")
      (value "10K")
      (footprint "eagle-import:0805")
      (libsource (lib "eagle-import") (part "RESISTOR0805"))
    )
    (comp (ref "R22")
      (value "10K")
      (footprint "eagle-import:0805")
      (libsource (lib "eagle-import") (part "RESISTOR0805"))
    )
    (comp (ref "R23")
      (value "10K")
      (footprint "eagle-import:0805")
      (libsource (lib "eagle-import") (part "RESISTOR0805"))
    )
    (comp (ref "R24")
      (value "360")
      (footprint "eagle-import:0805")
      (libsource (lib "eagle-import") (part "RESISTOR0805"))
    )
    (comp (ref "R30")
      (value "360")
      (footprint "eagle-import:0805")
      (libsource (lib "eagle-import") (part "RESISTOR0805"))
    )
    (comp (ref "R32")
      (value "4.7K")
      (footprint "eagle-import:0805")
      (libsource (lib "eagle-import") (part "RESISTOR0805"))
    )
    (comp (ref "R34")
      (value "4.7K")
      (footprint "eagle-import:0805")
      (libsource (lib "eagle-import") (part "RESISTOR0805"))
    )
    (comp (ref "R35")
      (value "10K")
      (footprint "eagle-import:0805")
      (libsource (lib "eagle-import") (part "RESISTOR0805"))
    )
    (comp (ref "R36")
      (value "10K")
      (footprint "eagle-import:0805")
      (libsource (lib "eagle-import") (part "RESISTOR0805"))
    )
    (comp (ref "R37")
      (value "10K")
      (footprint "eagle-import:0805")
      (libsource (lib "eagle-import") (part "RESISTOR0805"))
    )
    (comp (ref "R38")
      (value "10K")
      (footprint "eagle-import:0805")
      (libsource (lib "eagle-import") (part "RESISTOR0805"))
    )
    (comp (ref "R39")
      (value "10K")
      (footprint "eagle-import:0805")
      (libsource (lib "eagle-import") (part "RESISTOR0805"))
    )
    (comp (ref "R40")
      (value "10K")
      (footprint "eagle-import:0805")
      (libsource (lib "eagle-import") (part "RESISTOR0805"))
    )
    (comp (ref "R41")
      (value "10K")
      (footprint "eagle-import:0805")
      (libsource (lib "eagle-import") (part "RESISTOR0805"))
    )
    (comp (ref "R42")
      (value "10K")
      (footprint "eagle-import:0805")
      (libsource (lib "eagle-import") (part "RESISTOR0805"))
    )
    (comp (ref "R43")
      (value "10K")
      (footprint "eagle-import:0805")
      (libsource (lib "eagle-import") (part "RESISTOR0805"))
    )
    (comp (ref "R44")
      (value "10K")
      (footprint "eagle-import:0805")
      (libsource (lib "eagle-import") (part "RESISTOR0805"))
    )
    (comp (ref "R45")
      (value "10K")
      (footprint "eagle-import:0805")
      (libsource (lib "eagle-import") (part "RESISTOR0805"))
    )
    (comp (ref "R46")
      (value "10K")
      (footprint "eagle-import:0805")
      (libsource (lib "eagle-import") (part "RESISTOR0805"))
    )
    (comp (ref "R47")
      (value "10K")
      (footprint "eagle-import:0805")
      (libsource (lib "eagle-import") (part "RESISTOR0805"))
    )
    (comp (ref "R48")
      (value "10K")
      (footprint "eagle-import:0805")
      (libsource (lib "eagle-import") (part "RESISTOR0805"))
    )
    (comp (ref "R49")
      (value "10K")
      (footprint "eagle-import:0805")
      (libsource (lib "eagle-import") (part "RESISTOR0805"))
    )
    (comp (ref "R50")
      (value "10K")
      (footprint "eagle-import:0805")
      (libsource (lib "eagle-import") (part "RESISTOR0805"))
    )
    (comp (ref "R51")
      (value "10K")
      (footprint "eagle-import:0805")
      (libsource (lib "eagle-import") (part "RESISTOR0805"))
    )
    (comp (ref "R52")
      (value "10K")
      (footprint "eagle-import:0805")
      (libsource (lib "eagle-import") (part "RESISTOR0805"))
    )
    (comp (ref "R53")
      (value "10K")
      (footprint "eagle-import:0805")
      (libsource (lib "eagle-import") (part "RESISTOR0805"))
    )
    (comp (ref "R54")
      (value "10K")
      (footprint "eagle-import:0805")
      (libsource (lib "eagle-import") (part "RESISTOR0805"))
    )
    (comp (ref "R55")
      (value "10K")
      (footprint "eagle-import:0805")
      (libsource (lib "eagle-import") (part "RESISTOR0805"))
    )
    (comp (ref "R56")
      (value "10K")
      (footprint "eagle-import:0805")
      (libsource (lib "eagle-import") (part "RESISTOR0805"))
    )
    (comp (ref "R57")
      (value "10K")
      (footprint "eagle-import:0805")
      (libsource (lib "eagle-import") (part "RESISTOR0805"))
    )
    (comp (ref "R58")
      (value "10K")
      (footprint "eagle-import:0805")
      (libsource (lib "eagle-import") (part "RESISTOR0805"))
    )
    (comp (ref "R59")
      (value "10K")
      (footprint "eagle-import:0805")
      (libsource (lib "eagle-import") (part "RESISTOR0805"))
    )
    (comp (ref "R60")
      (value "10K")
      (footprint "eagle-import:0805")
      (libsource (lib "eagle-import") (part "RESISTOR0805"))
    )
    (comp (ref "R61")
      (value "10K")
      (footprint "eagle-import:0805")
      (libsource (lib "eagle-import") (part "RESISTOR0805"))
    )
    (comp (ref "R62")
      (value "10K")
      (footprint "eagle-import:0805")
      (libsource (lib "eagle-import") (part "RESISTOR0805"))
    )
    (comp (ref "R63")
      (value "10K")
      (footprint "eagle-import:0805")
      (libsource (lib "eagle-import") (part "RESISTOR0805"))
    )
    (comp (ref "R64")
      (value "10K")
      (footprint "eagle-import:0805")
      (libsource (lib "eagle-import") (part "RESISTOR0805"))
    )
    (comp (ref "R65")
      (value "10K")
      (footprint "eagle-import:0805")
      (libsource (lib "eagle-import") (part "RESISTOR0805"))
    )
    (comp (ref "R66")
      (value "10K")
      (footprint "eagle-import:0805")
      (libsource (lib "eagle-import") (part "RESISTOR0805"))
    )
    (comp (ref "R67")
      (value "10K")
      (footprint "eagle-import:0805")
      (libsource (lib "eagle-import") (part "RESISTOR0805"))
    )
    (comp (ref "R68")
      (value "10K")
      (footprint "eagle-import:0805")
      (libsource (lib "eagle-import") (part "RESISTOR0805"))
    )
    (comp (ref "R69")
      (value "10K")
      (footprint "eagle-import:0805")
      (libsource (lib "eagle-import") (part "RESISTOR0805"))
    )
    (comp (ref "R70")
      (value "10K")
      (footprint "eagle-import:0805")
      (libsource (lib "eagle-import") (part "RESISTOR0805"))
    )
    (comp (ref "R71")
      (value "10K")
      (footprint "eagle-import:0805")
      (libsource (lib "eagle-import") (part "RESISTOR0805"))
    )
    (comp (ref "R72")
      (value "10K")
      (footprint "eagle-import:0805")
      (libsource (lib "eagle-import") (part "RESISTOR0805"))
    )
    (comp (ref "R73")
      (value "10K")
      (footprint "eagle-import:0805")
      (libsource (lib "eagle-import") (part "RESISTOR0805"))
    )
    (comp (ref "R74")
      (value "10K")
      (footprint "eagle-import:0805")
      (libsource (lib "eagle-import") (part "RESISTOR0805"))
    )
    (comp (ref "R75")
      (value "10K")
      (footprint "eagle-import:0805")
      (libsource (lib "eagle-import") (part "RESISTOR0805"))
    )
    (comp (ref "R76")
      (value "10K")
      (footprint "eagle-import:0805")
      (libsource (lib "eagle-import") (part "RESISTOR0805"))
    )
    (comp (ref "R77")
      (value "10K")
      (footprint "eagle-import:0805")
      (libsource (lib "eagle-import") (part "RESISTOR0805"))
    )
    (comp (ref "R78")
      (value "10K")
      (footprint "eagle-import:0805")
      (libsource (lib "eagle-import") (part "RESISTOR0805"))
    )
    (comp (ref "R79")
      (value "10K")
      (footprint "eagle-import:0805")
      (libsource (lib "eagle-import") (part "RESISTOR0805"))
    )
    (comp (ref "R80")
      (value "10K")
      (footprint "eagle-import:0805")
      (libsource (lib "eagle-import") (part "RESISTOR0805"))
    )
    (comp (ref "R81")
      (value "10K")
      (footprint "eagle-import:0805")
      (libsource (lib "eagle-import") (part "RESISTOR0805"))
    )
    (comp (ref "R82")
      (value "10K")
      (footprint "eagle-import:0805")
      (libsource (lib "eagle-import") (part "RESISTOR0805"))
    )
    (comp (ref "R83")
      (value "10K")
      (footprint "eagle-import:0805")
      (libsource (lib "eagle-import") (part "RESISTOR0805"))
    )
    (comp (ref "R84")
      (value "360")
      (footprint "eagle-import:0805")
      (libsource (lib "eagle-import") (part "RESISTOR0805"))
    )
    (comp (ref "R85")
      (value "10K")
      (footprint "eagle-import:0805")
      (libsource (lib "eagle-import") (part "RESISTOR0805"))
    )
    (comp (ref "R86")
      (value "360")
      (footprint "eagle-import:0805")
      (libsource (lib "eagle-import") (part "RESISTOR0805"))
    )
    (comp (ref "R87")
      (value "10K")
      (footprint "eagle-import:0805")
      (libsource (lib "eagle-import") (part "RESISTOR0805"))
    )
    (comp (ref "R88")
      (value "360")
      (footprint "eagle-import:0805")
      (libsource (lib "eagle-import") (part "RESISTOR0805"))
    )
    (comp (ref "R89")
      (value "10K")
      (footprint "eagle-import:0805")
      (libsource (lib "eagle-import") (part "RESISTOR0805"))
    )
    (comp (ref "R90")
      (value "360")
      (footprint "eagle-import:0805")
      (libsource (lib "eagle-import") (part "RESISTOR0805"))
    )
    (comp (ref "R91")
      (value "10K")
      (footprint "eagle-import:0805")
      (libsource (lib "eagle-import") (part "RESISTOR0805"))
    )
    (comp (ref "R92")
      (value "360")
      (footprint "eagle-import:0805")
      (libsource (lib "eagle-import") (part "RESISTOR0805"))
    )
    (comp (ref "R93")
      (value "10K")
      (footprint "eagle-import:0805")
      (libsource (lib "eagle-import") (part "RESISTOR0805"))
    )
    (comp (ref "R94")
      (value "360")
      (footprint "eagle-import:0805")
      (libsource (lib "eagle-import") (part "RESISTOR0805"))
    )
    (comp (ref "R95")
      (value "10K")
      (footprint "eagle-import:0805")
      (libsource (lib "eagle-import") (part "RESISTOR0805"))
    )
    (comp (ref "R96")
      (value "360")
      (footprint "eagle-import:0805")
      (libsource (lib "eagle-import") (part "RESISTOR0805"))
    )
    (comp (ref "R97")
      (value "10K")
      (footprint "eagle-import:0805")
      (libsource (lib "eagle-import") (part "RESISTOR0805"))
    )
    (comp (ref "R98")
      (value "360")
      (footprint "eagle-import:0805")
      (libsource (lib "eagle-import") (part "RESISTOR0805"))
    )
    (comp (ref "R99")
      (value "360")
      (footprint "eagle-import:0805")
      (libsource (lib "eagle-import") (part "RESISTOR0805"))
    )
    (comp (ref "R100")
      (value "360")
      (footprint "eagle-import:0805")
      (libsource (lib "eagle-import") (part "RESISTOR0805"))
    )
    (comp (ref "R101")
      (value "360")
      (footprint "eagle-import:0805")
      (libsource (lib "eagle-import") (part "RESISTOR0805"))
    )
    (comp (ref "R102")
      (value "360")
      (footprint "eagle-import:0805")
      (libsource (lib "eagle-import") (part "RESISTOR0805"))
    )
    (comp (ref "R103")
      (value "360")
      (footprint "eagle-import:0805")
      (libsource (lib "eagle-import") (part "RESISTOR0805"))
    )
    (comp (ref "R104")
      (value "360")
      (footprint "eagle-import:0805")
      (libsource (lib "eagle-import") (part "RESISTOR0805"))
    )
    (comp (ref "R105")
      (value "360")
      (footprint "eagle-import:0805")
      (libsource (lib "eagle-import") (part "RESISTOR0805"))
    )
    (comp (ref "R106")
      (value "360")
      (footprint "eagle-import:0805")
      (libsource (lib "eagle-import") (part "RESISTOR0805"))
    )
    (comp (ref "R107")
      (value "360")
      (footprint "eagle-import:0805")
      (libsource (lib "eagle-import") (part "RESISTOR0805"))
    )
    (comp (ref "R108")
      (value "360")
      (footprint "eagle-import:0805")
      (libsource (lib "eagle-import") (part "RESISTOR0805"))
    )
    (comp (ref "R109")
      (value "360")
      (footprint "eagle-import:0805")
      (libsource (lib "eagle-import") (part "RESISTOR0805"))
    )
    (comp (ref "R110")
      (value "360")
      (footprint "eagle-import:0805")
      (libsource (lib "eagle-import") (part "RESISTOR0805"))
    )
    (comp (ref "R111")
      (value "360")
      (footprint "eagle-import:0805")
      (libsource (lib "eagle-import") (part "RESISTOR0805"))
    )
    (comp (ref "R112")
      (value "360")
      (footprint "eagle-import:0805")
      (libsource (lib "eagle-import") (part "RESISTOR0805"))
    )
    (comp (ref "R113")
      (value "360")
      (footprint "eagle-import:0805")
      (libsource (lib "eagle-import") (part "RESISTOR0805"))
    )
    (comp (ref "R114")
      (value "360")
      (footprint "eagle-import:0805")
      (libsource (lib "eagle-import") (part "RESISTOR0805"))
    )
    (comp (ref "R115")
      (value "10K")
      (footprint "eagle-import:0805")
      (libsource (lib "eagle-import") (part "RESISTOR0805"))
    )
    (comp (ref "R116")
      (value "360")
      (footprint "eagle-import:0805")
      (libsource (lib "eagle-import") (part "RESISTOR0805"))
    )
    (comp (ref "R117")
      (value "360")
      (footprint "eagle-import:0805")
      (libsource (lib "eagle-import") (part "RESISTOR0805"))
    )
    (comp (ref "R118")
      (value "360")
      (footprint "eagle-import:0805")
      (libsource (lib "eagle-import") (part "RESISTOR0805"))
    )
    (comp (ref "R119")
      (value "10K")
      (footprint "eagle-import:0805")
      (libsource (lib "eagle-import") (part "RESISTOR0805"))
    )
    (comp (ref "R120")
      (value "10K")
      (footprint "eagle-import:0805")
      (libsource (lib "eagle-import") (part "RESISTOR0805"))
    )
    (comp (ref "R121")
      (value "10K")
      (footprint "eagle-import:0805")
      (libsource (lib "eagle-import") (part "RESISTOR0805"))
    )
    (comp (ref "R122")
      (value "10K")
      (footprint "eagle-import:0805")
      (libsource (lib "eagle-import") (part "RESISTOR0805"))
    )
    (comp (ref "R123")
      (value "10K")
      (footprint "eagle-import:0805")
      (libsource (lib "eagle-import") (part "RESISTOR0805"))
    )
    (comp (ref "R124")
      (value "10K")
      (footprint "eagle-import:0805")
      (libsource (lib "eagle-import") (part "RESISTOR0805"))
    )
    (comp (ref "R125")
      (value "360")
      (footprint "eagle-import:0805")
      (libsource (lib "eagle-import") (part "RESISTOR0805"))
    )
    (comp (ref "R126")
      (value "360")
      (footprint "eagle-import:0805")
      (libsource (lib "eagle-import") (part "RESISTOR0805"))
    )
    (comp (ref "R127")
      (value "360")
      (footprint "eagle-import:0805")
      (libsource (lib "eagle-import") (part "RESISTOR0805"))
    )
    (comp (ref "R128")
      (value "360")
      (footprint "eagle-import:0805")
      (libsource (lib "eagle-import") (part "RESISTOR0805"))
    )
    (comp (ref "R129")
      (value "360")
      (footprint "eagle-import:0805")
      (libsource (lib "eagle-import") (part "RESISTOR0805"))
    )
    (comp (ref "R130")
      (value "360")
      (footprint "eagle-import:0805")
      (libsource (lib "eagle-import") (part "RESISTOR0805"))
    )
    (comp (ref "R131")
      (value "360")
      (footprint "eagle-import:0805")
      (libsource (lib "eagle-import") (part "RESISTOR0805"))
    )
    (comp (ref "R132")
      (value "360")
      (footprint "eagle-import:0805")
      (libsource (lib "eagle-import") (part "RESISTOR0805"))
    )
    (comp (ref "R133")
      (value "10K")
      (footprint "eagle-import:0805")
      (libsource (lib "eagle-import") (part "RESISTOR0805"))
    )
    (comp (ref "R134")
      (value "20K")
      (footprint "eagle-import:0805")
      (libsource (lib "eagle-import") (part "RESISTOR0805"))
    )
    (comp (ref "R135")
      (value "10K")
      (footprint "eagle-import:0805")
      (libsource (lib "eagle-import") (part "RESISTOR0805"))
    )
    (comp (ref "R136")
      (value "0")
      (footprint "eagle-import:0805")
      (libsource (lib "eagle-import") (part "RESISTOR0805"))
    )
    (comp (ref "R137")
      (value "10K")
      (footprint "eagle-import:0805")
      (libsource (lib "eagle-import") (part "RESISTOR0805"))
    )
    (comp (ref "R138")
      (value "10K")
      (footprint "eagle-import:0805")
      (libsource (lib "eagle-import") (part "RESISTOR0805"))
    )
    (comp (ref "R139")
      (value "10K")
      (footprint "eagle-import:0805")
      (libsource (lib "eagle-import") (part "RESISTOR0805"))
    )
    (comp (ref "R176")
      (value "10K")
      (footprint "eagle-import:0805")
      (libsource (lib "eagle-import") (part "RESISTOR0805"))
    )
    (comp (ref "R180")
      (value "22")
      (footprint "eagle-import:0805")
      (libsource (lib "eagle-import") (part "RESISTOR0805"))
    )
    (comp (ref "R181")
      (value "22")
      (footprint "eagle-import:0805")
      (libsource (lib "eagle-import") (part "RESISTOR0805"))
    )
    (comp (ref "RGB_0")
      (value "RFP12N10L")
      (footprint "eagle-import:TO-220AB")
      (libsource (lib "eagle-import") (part "MOSFET_N-CHANNEL_SINGLETO-220AB"))
    )
    (comp (ref "RGB_1")
      (value "RFP12N10L")
      (footprint "eagle-import:TO-220AB")
      (libsource (lib "eagle-import") (part "MOSFET_N-CHANNEL_SINGLETO-220AB"))
    )
    (comp (ref "RGB_2")
      (value "RFP12N10L")
      (footprint "eagle-import:TO-220AB")
      (libsource (lib "eagle-import") (part "MOSFET_N-CHANNEL_SINGLETO-220AB"))
    )
    (comp (ref "RGB_3")
      (value "RFP12N10L")
      (footprint "eagle-import:TO-220AB")
      (libsource (lib "eagle-import") (part "MOSFET_N-CHANNEL_SINGLETO-220AB"))
    )
    (comp (ref "RGB_4")
      (value "RFP12N10L")
      (footprint "eagle-import:TO-220AB")
      (libsource (lib "eagle-import") (part "MOSFET_N-CHANNEL_SINGLETO-220AB"))
    )
    (comp (ref "RGB_5")
      (value "RFP12N10L")
      (footprint "eagle-import:TO-220AB")
      (libsource (lib "eagle-import") (part "MOSFET_N-CHANNEL_SINGLETO-220AB"))
    )
    (comp (ref "RGB_CONN")
      (value "26-60-4080")
      (footprint "eagle-import:MOLEX_KK_8")
      (libsource (lib "eagle-import") (part "PH_1X08MOLEX_KK_8"))
    )
    (comp (ref "SD0")
      (value "SD-RSMT-2-MQ")
      (footprint "eagle-import:SD-RSMT-2-MQ")
      (libsource (lib "eagle-import") (part "SD_CARDSD-RSMT-2-MQ"))
    )
    (comp (ref "SOL_0")
      (value "IRL530PBF")
      (footprint "eagle-import:TO-220AB")
      (libsource (lib "eagle-import") (part "MOSFET_N-CHANNEL_SINGLETO-220AB"))
    )
    (comp (ref "SOL_1")
      (value "IRL530PBF")
      (footprint "eagle-import:TO-220AB")
      (libsource (lib "eagle-import") (part "MOSFET_N-CHANNEL_SINGLETO-220AB"))
    )
    (comp (ref "SOL_2")
      (value "IRL530PBF")
      (footprint "eagle-import:TO-220AB")
      (libsource (lib "eagle-import") (part "MOSFET_N-CHANNEL_SINGLETO-220AB"))
    )
    (comp (ref "SOL_3")
      (value "IRL530PBF")
      (footprint "eagle-import:TO-220AB")
      (libsource (lib "eagle-import") (part "MOSFET_N-CHANNEL_SINGLETO-220AB"))
    )
    (comp (ref "SOL_4")
      (value "IRL530PBF")
      (footprint "eagle-import:TO-220AB")
      (libsource (lib "eagle-import") (part "MOSFET_N-CHANNEL_SINGLETO-220AB"))
    )
    (comp (ref "SOL_5")
      (value "IRL530PBF")
      (footprint "eagle-import:TO-220AB")
      (libsource (lib "eagle-import") (part "MOSFET_N-CHANNEL_SINGLETO-220AB"))
    )
    (comp (ref "SOL_6")
      (value "IRL530PBF")
      (footprint "eagle-import:TO-220AB")
      (libsource (lib "eagle-import") (part "MOSFET_N-CHANNEL_SINGLETO-220AB"))
    )
    (comp (ref "SOL_7")
      (value "IRL530PBF")
      (footprint "eagle-import:TO-220AB")
      (libsource (lib "eagle-import") (part "MOSFET_N-CHANNEL_SINGLETO-220AB"))
    )
    (comp (ref "SOL_8")
      (value "IRL530PBF")
      (footprint "eagle-import:TO-220AB")
      (libsource (lib "eagle-import") (part "MOSFET_N-CHANNEL_SINGLETO-220AB"))
    )
    (comp (ref "SOL_9")
      (value "IRL530PBF")
      (footprint "eagle-import:TO-220AB")
      (libsource (lib "eagle-import") (part "MOSFET_N-CHANNEL_SINGLETO-220AB"))
    )
    (comp (ref "SOL_10")
      (value "IRL530PBF")
      (footprint "eagle-import:TO-220AB")
      (libsource (lib "eagle-import") (part "MOSFET_N-CHANNEL_SINGLETO-220AB"))
    )
    (comp (ref "SOL_11")
      (value "IRL530PBF")
      (footprint "eagle-import:TO-220AB")
      (libsource (lib "eagle-import") (part "MOSFET_N-CHANNEL_SINGLETO-220AB"))
    )
    (comp (ref "SOL_12")
      (value "IRL530PBF")
      (footprint "eagle-import:TO-220AB")
      (libsource (lib "eagle-import") (part "MOSFET_N-CHANNEL_SINGLETO-220AB"))
    )
    (comp (ref "SOL_13")
      (value "IRL530PBF")
      (footprint "eagle-import:TO-220AB")
      (libsource (lib "eagle-import") (part "MOSFET_N-CHANNEL_SINGLETO-220AB"))
    )
    (comp (ref "SOL_14")
      (value "IRL530PBF")
      (footprint "eagle-import:TO-220AB")
      (libsource (lib "eagle-import") (part "MOSFET_N-CHANNEL_SINGLETO-220AB"))
    )
    (comp (ref "SOL_15")
      (value "IRL530PBF")
      (footprint "eagle-import:TO-220AB")
      (libsource (lib "eagle-import") (part "MOSFET_N-CHANNEL_SINGLETO-220AB"))
    )
    (comp (ref "SOL_16")
      (value "IRL530PBF")
      (footprint "eagle-import:TO-220AB")
      (libsource (lib "eagle-import") (part "MOSFET_N-CHANNEL_SINGLETO-220AB"))
    )
    (comp (ref "SOL_17")
      (value "IRL530PBF")
      (footprint "eagle-import:TO-220AB")
      (libsource (lib "eagle-import") (part "MOSFET_N-CHANNEL_SINGLETO-220AB"))
    )
    (comp (ref "SOL_18")
      (value "IRL530PBF")
      (footprint "eagle-import:TO-220AB")
      (libsource (lib "eagle-import") (part "MOSFET_N-CHANNEL_SINGLETO-220AB"))
    )
    (comp (ref "SOL_19")
      (value "IRL530PBF")
      (footprint "eagle-import:TO-220AB")
      (libsource (lib "eagle-import") (part "MOSFET_N-CHANNEL_SINGLETO-220AB"))
    )
    (comp (ref "SOL_20")
      (value "IRL530PBF")
      (footprint "eagle-import:TO-220AB")
      (libsource (lib "eagle-import") (part "MOSFET_N-CHANNEL_SINGLETO-220AB"))
    )
    (comp (ref "SOL_21")
      (value "IRL530PBF")
      (footprint "eagle-import:TO-220AB")
      (libsource (lib "eagle-import") (part "MOSFET_N-CHANNEL_SINGLETO-220AB"))
    )
    (comp (ref "SOL_22")
      (value "IRL530PBF")
      (footprint "eagle-import:TO-220AB")
      (libsource (lib "eagle-import") (part "MOSFET_N-CHANNEL_SINGLETO-220AB"))
    )
    (comp (ref "SOL_23")
      (value "IRL530PBF")
      (footprint "eagle-import:TO-220AB")
      (libsource (lib "eagle-import") (part "MOSFET_N-CHANNEL_SINGLETO-220AB"))
    )
    (comp (ref "SOL_BANK_0")
      (value "26-64-4100")
      (footprint "eagle-import:MOLEX_KK_10")
      (libsource (lib "eagle-import") (part "PH_1X10KK_10"))
    )
    (comp (ref "SOL_BANK_1")
      (value "26-64-4100")
      (footprint "eagle-import:MOLEX_KK_10")
      (libsource (lib "eagle-import") (part "PH_1X10KK_10"))
    )
    (comp (ref "SOL_BANK_2")
      (value "26-64-4100")
      (footprint "eagle-import:MOLEX_KK_10")
      (libsource (lib "eagle-import") (part "PH_1X10KK_10"))
    )
    (comp (ref "SOL_PWR")
      (value "26-60-4040")
      (footprint "eagle-import:MOLEX_KK_4")
      (libsource (lib "eagle-import") (part "PH_1X04KK_4"))
    )
    (comp (ref "SW1")
      (value "TACT_6MM")
      (footprint "eagle-import:TACT6MM")
      (libsource (lib "eagle-import") (part "TACT_6MM"))
    )
    (comp (ref "SW2")
      (value "TACT_6MM")
      (footprint "eagle-import:TACT6MM")
      (libsource (lib "eagle-import") (part "TACT_6MM"))
    )
    (comp (ref "SW3")
      (value "TACT_6MM")
      (footprint "eagle-import:TACT6MM")
      (libsource (lib "eagle-import") (part "TACT_6MM"))
    )
    (comp (ref "SW4")
      (value "0S102011MS2QS1")
      (footprint "eagle-import:0S102011MS2QS1")
      (libsource (lib "eagle-import") (part "SPDT0S102011MS2QS1"))
    )
    (comp (ref "SW_COL")
      (value "26-64-4100")
      (footprint "eagle-import:MOLEX_KK_10")
      (libsource (lib "eagle-import") (part "PH_1X10KK_10"))
    )
    (comp (ref "SW_ROW")
      (value "26-64-4100")
      (footprint "eagle-import:MOLEX_KK_10")
      (libsource (lib "eagle-import") (part "PH_1X10KK_10"))
    )
    (comp (ref "TCBTWDN_PORT")
      (value "N/A")
      (footprint "eagle-import:HEADER_01X09_PTH")
      (libsource (lib "eagle-import") (part "PH_1X09PTH"))
    )
    (comp (ref "U$1")
      (value "LHE_LOGOLHE_LOGO")
      (footprint "eagle-import:LHE_LOGO")
      (libsource (lib "eagle-import") (part "LHE_LOGOLHE_LOGO"))
    )
    (comp (ref "U$2")
      (value "MF_LOGOLOGO_TEXT")
      (footprint "eagle-import:MF_LOGO_TEXT")
      (libsource (lib "eagle-import") (part "MF_LOGOLOGO_TEXT"))
    )
    (comp (ref "U1")
      (value "P8X32A-Q44")
      (footprint "eagle-import:LQFP-44")
      (libsource (lib "eagle-import") (part "P8X32A_PROPELLERLQFP-44"))
    )
    (comp (ref "U2")
      (value "FT230XS-R")
      (footprint "eagle-import:SSOP-16")
      (libsource (lib "eagle-import") (part "FT230XSSOP-16"))
    )
    (comp (ref "U3")
      (value "74HC595D-Q100")
      (footprint "eagle-import:SO-16")
      (libsource (lib "eagle-import") (part "74HC595SO-16"))
    )
    (comp (ref "U4")
      (value "24LC1025-I/P")
      (footprint "eagle-import:DIP-8")
      (libsource (lib "eagle-import") (part "CAT24M01XI-T2DIP-8"))
    )
    (comp (ref "U5")
      (value "74HC595D-Q100")
      (footprint "eagle-import:SO-16")
      (libsource (lib "eagle-import") (part "74HC595SO-16"))
    )
    (comp (ref "U6")
      (value "TIP102")
      (footprint "eagle-import:TO-220AB")
      (libsource (lib "eagle-import") (part "BJT_NPN_SINGLETO-220"))
    )
    (comp (ref "U7")
      (value "TIP102")
      (footprint "eagle-import:TO-220AB")
      (libsource (lib "eagle-import") (part "BJT_NPN_SINGLETO-220"))
    )
    (comp (ref "U8")
      (value "TIP102")
      (footprint "eagle-import:TO-220AB")
      (libsource (lib "eagle-import") (part "BJT_NPN_SINGLETO-220"))
    )
    (comp (ref "U9")
      (value "TIP102")
      (footprint "eagle-import:TO-220AB")
      (libsource (lib "eagle-import") (part "BJT_NPN_SINGLETO-220"))
    )
    (comp (ref "U10")
      (value "74HCT2G04GV,125")
      (footprint "eagle-import:TTSOP-6")
      (libsource (lib "eagle-import") (part "74HCT2G04GV,125TTSOP-6"))
    )
    (comp (ref "U11")
      (value "74HC165D,652")
      (footprint "eagle-import:SO-16")
      (libsource (lib "eagle-import") (part "74HC165SO-16"))
    )
    (comp (ref "U12")
      (value "74HC165D,652")
      (footprint "eagle-import:SO-16")
      (libsource (lib "eagle-import") (part "74HC165SO-16"))
    )
    (comp (ref "U14")
      (value "MC74HC08ADG")
      (footprint "eagle-import:SOIC-14")
      (libsource (lib "eagle-import") (part "MC74HC08ADGSOIC-14"))
    )
    (comp (ref "U15")
      (value "MC74HC08ADG")
      (footprint "eagle-import:SOIC-14")
      (libsource (lib "eagle-import") (part "MC74HC08ADGSOIC-14"))
    )
    (comp (ref "U16")
      (value "MC74HC08ADG")
      (footprint "eagle-import:SOIC-14")
      (libsource (lib "eagle-import") (part "MC74HC08ADGSOIC-14"))
    )
    (comp (ref "U17")
      (value "MC74HC08ADG")
      (footprint "eagle-import:SOIC-14")
      (libsource (lib "eagle-import") (part "MC74HC08ADGSOIC-14"))
    )
    (comp (ref "U18")
      (value "MC74HC08ADG")
      (footprint "eagle-import:SOIC-14")
      (libsource (lib "eagle-import") (part "MC74HC08ADGSOIC-14"))
    )
    (comp (ref "U19")
      (value "MC74HC08ADG")
      (footprint "eagle-import:SOIC-14")
      (libsource (lib "eagle-import") (part "MC74HC08ADGSOIC-14"))
    )
    (comp (ref "U20")
      (value "TIP107")
      (footprint "eagle-import:TO-220AB")
      (libsource (lib "eagle-import") (part "BJT_PNP_SINGLETO-220"))
    )
    (comp (ref "U21")
      (value "TIP107")
      (footprint "eagle-import:TO-220AB")
      (libsource (lib "eagle-import") (part "BJT_PNP_SINGLETO-220"))
    )
    (comp (ref "U22")
      (value "TIP107")
      (footprint "eagle-import:TO-220AB")
      (libsource (lib "eagle-import") (part "BJT_PNP_SINGLETO-220"))
    )
    (comp (ref "U23")
      (value "TIP107")
      (footprint "eagle-import:TO-220AB")
      (libsource (lib "eagle-import") (part "BJT_PNP_SINGLETO-220"))
    )
    (comp (ref "U24")
      (value "TIP107")
      (footprint "eagle-import:TO-220AB")
      (libsource (lib "eagle-import") (part "BJT_PNP_SINGLETO-220"))
    )
    (comp (ref "U25")
      (value "TIP107")
      (footprint "eagle-import:TO-220AB")
      (libsource (lib "eagle-import") (part "BJT_PNP_SINGLETO-220"))
    )
    (comp (ref "U26")
      (value "TIP107")
      (footprint "eagle-import:TO-220AB")
      (libsource (lib "eagle-import") (part "BJT_PNP_SINGLETO-220"))
    )
    (comp (ref "U27")
      (value "TIP107")
      (footprint "eagle-import:TO-220AB")
      (libsource (lib "eagle-import") (part "BJT_PNP_SINGLETO-220"))
    )
    (comp (ref "U28")
      (value "TIP102")
      (footprint "eagle-import:TO-220AB")
      (libsource (lib "eagle-import") (part "BJT_NPN_SINGLETO-220"))
    )
    (comp (ref "U29")
      (value "TIP102")
      (footprint "eagle-import:TO-220AB")
      (libsource (lib "eagle-import") (part "BJT_NPN_SINGLETO-220"))
    )
    (comp (ref "U30")
      (value "TIP102")
      (footprint "eagle-import:TO-220AB")
      (libsource (lib "eagle-import") (part "BJT_NPN_SINGLETO-220"))
    )
    (comp (ref "U31")
      (value "TIP102")
      (footprint "eagle-import:TO-220AB")
      (libsource (lib "eagle-import") (part "BJT_NPN_SINGLETO-220"))
    )
    (comp (ref "U32")
      (value "TIP102")
      (footprint "eagle-import:TO-220AB")
      (libsource (lib "eagle-import") (part "BJT_NPN_SINGLETO-220"))
    )
    (comp (ref "U33")
      (value "TIP102")
      (footprint "eagle-import:TO-220AB")
      (libsource (lib "eagle-import") (part "BJT_NPN_SINGLETO-220"))
    )
    (comp (ref "U34")
      (value "TIP102")
      (footprint "eagle-import:TO-220AB")
      (libsource (lib "eagle-import") (part "BJT_NPN_SINGLETO-220"))
    )
    (comp (ref "U35")
      (value "TIP102")
      (footprint "eagle-import:TO-220AB")
      (libsource (lib "eagle-import") (part "BJT_NPN_SINGLETO-220"))
    )
    (comp (ref "U36")
      (value "WS2801")
      (footprint "eagle-import:SOP-14")
      (libsource (lib "eagle-import") (part "WS2801SOP-14"))
    )
    (comp (ref "U37")
      (value "TIP102")
      (footprint "eagle-import:TO-220AB")
      (libsource (lib "eagle-import") (part "BJT_NPN_SINGLETO-220"))
    )
    (comp (ref "U38")
      (value "WS2801")
      (footprint "eagle-import:SOP-14")
      (libsource (lib "eagle-import") (part "WS2801SOP-14"))
    )
    (comp (ref "U39")
      (value "LM2937IMP-3.3/NOPB")
      (footprint "eagle-import:SOT-223")
      (libsource (lib "eagle-import") (part "FIXED_VOLTAGE_REGSOT-223"))
    )
    (comp (ref "U40")
      (value "TIP102")
      (footprint "eagle-import:TO-220AB")
      (libsource (lib "eagle-import") (part "BJT_NPN_SINGLETO-220"))
    )
    (comp (ref "U41")
      (value "TIP102")
      (footprint "eagle-import:TO-220AB")
      (libsource (lib "eagle-import") (part "BJT_NPN_SINGLETO-220"))
    )
    (comp (ref "U42")
      (value "TIP102")
      (footprint "eagle-import:TO-220AB")
      (libsource (lib "eagle-import") (part "BJT_NPN_SINGLETO-220"))
    )
    (comp (ref "U43")
      (value "TIP102")
      (footprint "eagle-import:TO-220AB")
      (libsource (lib "eagle-import") (part "BJT_NPN_SINGLETO-220"))
    )
    (comp (ref "U44")
      (value "TIP102")
      (footprint "eagle-import:TO-220AB")
      (libsource (lib "eagle-import") (part "BJT_NPN_SINGLETO-220"))
    )
    (comp (ref "U45")
      (value "TIP102")
      (footprint "eagle-import:TO-220AB")
      (libsource (lib "eagle-import") (part "BJT_NPN_SINGLETO-220"))
    )
    (comp (ref "U46")
      (value "TIP102")
      (footprint "eagle-import:TO-220AB")
      (libsource (lib "eagle-import") (part "BJT_NPN_SINGLETO-220"))
    )
    (comp (ref "U47")
      (value "TIP102")
      (footprint "eagle-import:TO-220AB")
      (libsource (lib "eagle-import") (part "BJT_NPN_SINGLETO-220"))
    )
    (comp (ref "U48")
      (value "TIP102")
      (footprint "eagle-import:TO-220AB")
      (libsource (lib "eagle-import") (part "BJT_NPN_SINGLETO-220"))
    )
    (comp (ref "U49")
      (value "TIP102")
      (footprint "eagle-import:TO-220AB")
      (libsource (lib "eagle-import") (part "BJT_NPN_SINGLETO-220"))
    )
    (comp (ref "U50")
      (value "TIP102")
      (footprint "eagle-import:TO-220AB")
      (libsource (lib "eagle-import") (part "BJT_NPN_SINGLETO-220"))
    )
    (comp (ref "U51")
      (value "TIP102")
      (footprint "eagle-import:TO-220AB")
      (libsource (lib "eagle-import") (part "BJT_NPN_SINGLETO-220"))
    )
    (comp (ref "U52")
      (value "CD74HC123M96")
      (footprint "eagle-import:SOIC-16")
      (libsource (lib "eagle-import") (part "74HC123SOIC-16"))
    )
    (comp (ref "WD")
      (value "LG R971-KN-1")
      (footprint "eagle-import:LED_0805")
      (libsource (lib "eagle-import") (part "LED_SINGLE0805"))
    )
    (comp (ref "X1")
      (value "FQ7050B-8.000")
      (footprint "eagle-import:FQ7050B")
      (libsource (lib "eagle-import") (part "XTAL-FQ7050B"))
    )
    (comp (ref "X2")
      (value "ECS-65-20-4X")
      (footprint "eagle-import:HC-49_US_PTH")
      (libsource (lib "eagle-import") (part "CRYSTALHC-49/US_PTH"))
    )
  )
  (nets
    (net (code "1") (name "/3.3V") (class "Default")
      (node (ref "AUX_PORT") (pin "P$6") (pinfunction "6_P$6") (pintype "bidirectional"))
      (node (ref "BT1") (pin "11") (pinfunction "VDD_11") (pintype "bidirectional"))
      (node (ref "C11") (pin "1") (pinfunction "1_1") (pintype "passive"))
      (node (ref "C2") (pin "1") (pinfunction "1_1") (pintype "passive"))
      (node (ref "C20") (pin "2") (pinfunction "2_2") (pintype "passive"))
      (node (ref "C21") (pin "2") (pinfunction "2_2") (pintype "passive"))
      (node (ref "C22") (pin "2") (pinfunction "2_2") (pintype "passive"))
      (node (ref "C23") (pin "2") (pinfunction "2_2") (pintype "passive"))
      (node (ref "C24") (pin "2") (pinfunction "2_2") (pintype "passive"))
      (node (ref "C28") (pin "2") (pinfunction "2_2") (pintype "passive"))
      (node (ref "C29") (pin "1") (pinfunction "1_1") (pintype "passive"))
      (node (ref "C3") (pin "1") (pinfunction "1_1") (pintype "passive"))
      (node (ref "C32") (pin "2") (pinfunction "2_2") (pintype "passive"))
      (node (ref "C33") (pin "2") (pinfunction "2_2") (pintype "passive"))
      (node (ref "C34") (pin "POS") (pinfunction "POS_POS") (pintype "bidirectional"))
      (node (ref "C35") (pin "1") (pinfunction "1_1") (pintype "passive"))
      (node (ref "C36") (pin "1") (pinfunction "1_1") (pintype "passive"))
      (node (ref "C37") (pin "1") (pinfunction "1_1") (pintype "passive"))
      (node (ref "C4") (pin "1") (pinfunction "1_1") (pintype "passive"))
      (node (ref "C46") (pin "2") (pinfunction "2_2") (pintype "passive"))
      (node (ref "C5") (pin "1") (pinfunction "1_1") (pintype "passive"))
      (node (ref "C6") (pin "1") (pinfunction "1_1") (pintype "passive"))
      (node (ref "C7") (pin "1") (pinfunction "1_1") (pintype "passive"))
      (node (ref "D1") (pin "2") (pinfunction "AN_2") (pintype "bidirectional"))
      (node (ref "IC2") (pin "16") (pinfunction "VDD_16") (pintype "bidirectional"))
      (node (ref "IC2") (pin "2") (pinfunction "VDD_2") (pintype "bidirectional"))
      (node (ref "IC2") (pin "37") (pinfunction "VDD_37") (pintype "bidirectional"))
      (node (ref "IC2") (pin "46") (pinfunction "VDD_46") (pintype "bidirectional"))
      (node (ref "IC2") (pin "55") (pinfunction "VUSB_55") (pintype "bidirectional"))
      (node (ref "IC2") (pin "62") (pinfunction "VDD_62") (pintype "bidirectional"))
      (node (ref "IC2") (pin "86") (pinfunction "VDD_86") (pintype "bidirectional"))
      (node (ref "IC3") (pin "20") (pinfunction "VCC_20") (pintype "power_in"))
      (node (ref "IC4") (pin "20") (pinfunction "VCC_20") (pintype "power_in"))
      (node (ref "J11") (pin "2") (pinfunction "2_2") (pintype "passive"))
      (node (ref "PSU_PWR") (pin "ANODE") (pinfunction "ANODE_ANODE") (pintype "bidirectional"))
      (node (ref "R119") (pin "2") (pinfunction "2_2") (pintype "passive"))
      (node (ref "R120") (pin "2") (pinfunction "2_2") (pintype "passive"))
      (node (ref "R121") (pin "2") (pinfunction "2_2") (pintype "passive"))
      (node (ref "R122") (pin "2") (pinfunction "2_2") (pintype "passive"))
      (node (ref "R123") (pin "2") (pinfunction "2_2") (pintype "passive"))
      (node (ref "R124") (pin "2") (pinfunction "2_2") (pintype "passive"))
      (node (ref "R137") (pin "2") (pinfunction "2_2") (pintype "passive"))
      (node (ref "R16") (pin "2") (pinfunction "2_2") (pintype "passive"))
      (node (ref "R17") (pin "2") (pinfunction "2_2") (pintype "passive"))
      (node (ref "R176") (pin "2") (pinfunction "2_2") (pintype "passive"))
      (node (ref "R18") (pin "1") (pinfunction "1_1") (pintype "passive"))
      (node (ref "R19") (pin "1") (pinfunction "1_1") (pintype "passive"))
      (node (ref "R20") (pin "1") (pinfunction "1_1") (pintype "passive"))
      (node (ref "R21") (pin "1") (pinfunction "1_1") (pintype "passive"))
      (node (ref "R22") (pin "1") (pinfunction "1_1") (pintype "passive"))
      (node (ref "R23") (pin "1") (pinfunction "1_1") (pintype "passive"))
      (node (ref "R3") (pin "1") (pinfunction "1_1") (pintype "passive"))
      (node (ref "R35") (pin "2") (pinfunction "2_2") (pintype "passive"))
      (node (ref "R36") (pin "2") (pinfunction "2_2") (pintype "passive"))
      (node (ref "R37") (pin "2") (pinfunction "2_2") (pintype "passive"))
      (node (ref "R38") (pin "2") (pinfunction "2_2") (pintype "passive"))
      (node (ref "R39") (pin "2") (pinfunction "2_2") (pintype "passive"))
      (node (ref "R4") (pin "2") (pinfunction "2_2") (pintype "passive"))
      (node (ref "R40") (pin "2") (pinfunction "2_2") (pintype "passive"))
      (node (ref "R41") (pin "2") (pinfunction "2_2") (pintype "passive"))
      (node (ref "R42") (pin "2") (pinfunction "2_2") (pintype "passive"))
      (node (ref "R43") (pin "2") (pinfunction "2_2") (pintype "passive"))
      (node (ref "R44") (pin "2") (pinfunction "2_2") (pintype "passive"))
      (node (ref "R45") (pin "2") (pinfunction "2_2") (pintype "passive"))
      (node (ref "R46") (pin "2") (pinfunction "2_2") (pintype "passive"))
      (node (ref "R47") (pin "2") (pinfunction "2_2") (pintype "passive"))
      (node (ref "R48") (pin "2") (pinfunction "2_2") (pintype "passive"))
      (node (ref "R49") (pin "2") (pinfunction "2_2") (pintype "passive"))
      (node (ref "R50") (pin "2") (pinfunction "2_2") (pintype "passive"))
      (node (ref "R75") (pin "1") (pinfunction "1_1") (pintype "passive"))
      (node (ref "R76") (pin "1") (pinfunction "1_1") (pintype "passive"))
      (node (ref "R77") (pin "1") (pinfunction "1_1") (pintype "passive"))
      (node (ref "R78") (pin "1") (pinfunction "1_1") (pintype "passive"))
      (node (ref "R79") (pin "2") (pinfunction "2_2") (pintype "passive"))
      (node (ref "R80") (pin "2") (pinfunction "2_2") (pintype "passive"))
      (node (ref "R81") (pin "2") (pinfunction "2_2") (pintype "passive"))
      (node (ref "R82") (pin "2") (pinfunction "2_2") (pintype "passive"))
      (node (ref "SD0") (pin "4") (pinfunction "3.3V_4") (pintype "bidirectional"))
      (node (ref "SW4") (pin "2") (pinfunction "2_2") (pintype "bidirectional"))
      (node (ref "TCBTWDN_PORT") (pin "1") (pinfunction "1_1") (pintype "bidirectional"))
      (node (ref "U1") (pin "18") (pinfunction "VDD_18") (pintype "bidirectional"))
      (node (ref "U1") (pin "30") (pinfunction "VDD_30") (pintype "bidirectional"))
      (node (ref "U1") (pin "40") (pinfunction "VDD_40") (pintype "bidirectional"))
      (node (ref "U1") (pin "8") (pinfunction "VDD_8") (pintype "bidirectional"))
      (node (ref "U11") (pin "16") (pinfunction "VCC_16") (pintype "bidirectional"))
      (node (ref "U12") (pin "16") (pinfunction "VCC_16") (pintype "bidirectional"))
      (node (ref "U36") (pin "14") (pinfunction "VDD_14") (pintype "bidirectional"))
      (node (ref "U38") (pin "14") (pinfunction "VDD_14") (pintype "bidirectional"))
      (node (ref "U39") (pin "OUT") (pinfunction "OUT_OUT") (pintype "bidirectional"))
      (node (ref "U4") (pin "8") (pinfunction "VCC_8") (pintype "bidirectional"))
    )
    (net (code "2") (name "/3V3OUT") (class "Default")
      (node (ref "C16") (pin "1") (pinfunction "1_1") (pintype "passive"))
      (node (ref "U2") (pin "10") (pinfunction "3V3OUT_10") (pintype "bidirectional"))
      (node (ref "U2") (pin "11") (pinfunction "RESET#_11") (pintype "bidirectional"))
      (node (ref "U2") (pin "3") (pinfunction "VCCIO_3") (pintype "bidirectional"))
    )
    (net (code "3") (name "/5V") (class "Default")
      (node (ref "AUX_PORT") (pin "P$7") (pinfunction "7_P$7") (pintype "bidirectional"))
      (node (ref "AUX_PWR") (pin "2") (pinfunction "2_2") (pintype "passive"))
      (node (ref "BOARD_POWER") (pin "4") (pinfunction "4_4") (pintype "bidirectional"))
      (node (ref "BOARD_POWER") (pin "6") (pinfunction "6_6") (pintype "bidirectional"))
      (node (ref "C25") (pin "2") (pinfunction "2_2") (pintype "passive"))
      (node (ref "C26") (pin "2") (pinfunction "2_2") (pintype "passive"))
      (node (ref "C30") (pin "P$1") (pinfunction "P$1_P$1") (pintype "passive"))
      (node (ref "C38") (pin "POS") (pinfunction "POS_POS") (pintype "bidirectional"))
      (node (ref "C39") (pin "1") (pinfunction "1_1") (pintype "passive"))
      (node (ref "C40") (pin "1") (pinfunction "1_1") (pintype "passive"))
      (node (ref "C41") (pin "1") (pinfunction "1_1") (pintype "passive"))
      (node (ref "C48") (pin "1") (pinfunction "1_1") (pintype "passive"))
      (node (ref "C50") (pin "POS") (pinfunction "POS_POS") (pintype "bidirectional"))
      (node (ref "C51") (pin "1") (pinfunction "1_1") (pintype "passive"))
      (node (ref "C52") (pin "1") (pinfunction "1_1") (pintype "passive"))
      (node (ref "C53") (pin "1") (pinfunction "1_1") (pintype "passive"))
      (node (ref "CABINET") (pin "P$2") (pinfunction "2_P$2") (pintype "bidirectional"))
      (node (ref "D2") (pin "1") (pinfunction "CATHODE_1") (pintype "bidirectional"))
      (node (ref "DMD_PWR") (pin "P$1") (pinfunction "1_P$1") (pintype "passive"))
      (node (ref "GI_0") (pin "P$9") (pinfunction "9_P$9") (pintype "bidirectional"))
      (node (ref "GI_1") (pin "P$9") (pinfunction "9_P$9") (pintype "bidirectional"))
      (node (ref "LIGHT_ROW") (pin "P$1") (pinfunction "1_P$1") (pintype "bidirectional"))
      (node (ref "NEO_PIXEL") (pin "1") (pinfunction "1_1") (pintype "passive"))
      (node (ref "R134") (pin "2") (pinfunction "2_2") (pintype "passive"))
      (node (ref "U10") (pin "5") (pinfunction "VCC_5") (pintype "bidirectional"))
      (node (ref "U14") (pin "14") (pinfunction "VCC_14") (pintype "bidirectional"))
      (node (ref "U15") (pin "14") (pinfunction "VCC_14") (pintype "bidirectional"))
      (node (ref "U16") (pin "14") (pinfunction "VCC_14") (pintype "bidirectional"))
      (node (ref "U17") (pin "14") (pinfunction "VCC_14") (pintype "bidirectional"))
      (node (ref "U18") (pin "14") (pinfunction "VCC_14") (pintype "bidirectional"))
      (node (ref "U19") (pin "14") (pinfunction "VCC_14") (pintype "bidirectional"))
      (node (ref "U3") (pin "10") (pinfunction "MR_10") (pintype "bidirectional"))
      (node (ref "U3") (pin "16") (pinfunction "VCC_16") (pintype "bidirectional"))
      (node (ref "U39") (pin "IN") (pinfunction "IN_IN") (pintype "bidirectional"))
      (node (ref "U5") (pin "10") (pinfunction "MR_10") (pintype "bidirectional"))
      (node (ref "U5") (pin "16") (pinfunction "VCC_16") (pintype "bidirectional"))
      (node (ref "U52") (pin "16") (pinfunction "VCC_16") (pintype "bidirectional"))
      (node (ref "U52") (pin "2") (pinfunction "~{1B}_2") (pintype "bidirectional"))
      (node (ref "U52") (pin "3") (pinfunction "~{1R}_3") (pintype "bidirectional"))
    )
    (net (code "4") (name "/12V") (class "Default")
      (node (ref "AUX_PWR") (pin "4") (pinfunction "4_4") (pintype "passive"))
      (node (ref "BOARD_POWER") (pin "2") (pinfunction "2_2") (pintype "bidirectional"))
      (node (ref "C42") (pin "POS") (pinfunction "POS_POS") (pintype "bidirectional"))
      (node (ref "C43") (pin "1") (pinfunction "1_1") (pintype "passive"))
      (node (ref "C44") (pin "1") (pinfunction "1_1") (pintype "passive"))
      (node (ref "C45") (pin "1") (pinfunction "1_1") (pintype "passive"))
      (node (ref "LIGHT_COL") (pin "P$1") (pinfunction "1_P$1") (pintype "bidirectional"))
      (node (ref "R83") (pin "1") (pinfunction "1_1") (pintype "passive"))
      (node (ref "R85") (pin "1") (pinfunction "1_1") (pintype "passive"))
      (node (ref "R87") (pin "1") (pinfunction "1_1") (pintype "passive"))
      (node (ref "R89") (pin "1") (pinfunction "1_1") (pintype "passive"))
      (node (ref "R91") (pin "1") (pinfunction "1_1") (pintype "passive"))
      (node (ref "R93") (pin "1") (pinfunction "1_1") (pintype "passive"))
      (node (ref "R95") (pin "1") (pinfunction "1_1") (pintype "passive"))
      (node (ref "R97") (pin "1") (pinfunction "1_1") (pintype "passive"))
      (node (ref "RGB_CONN") (pin "1") (pinfunction "1_1") (pintype "bidirectional"))
      (node (ref "RGB_CONN") (pin "2") (pinfunction "2_2") (pintype "bidirectional"))
      (node (ref "U20") (pin "S") (pinfunction "EMITTER_S") (pintype "bidirectional"))
      (node (ref "U21") (pin "S") (pinfunction "EMITTER_S") (pintype "bidirectional"))
      (node (ref "U22") (pin "S") (pinfunction "EMITTER_S") (pintype "bidirectional"))
      (node (ref "U23") (pin "S") (pinfunction "EMITTER_S") (pintype "bidirectional"))
      (node (ref "U24") (pin "S") (pinfunction "EMITTER_S") (pintype "bidirectional"))
      (node (ref "U25") (pin "S") (pinfunction "EMITTER_S") (pintype "bidirectional"))
      (node (ref "U26") (pin "S") (pinfunction "EMITTER_S") (pintype "bidirectional"))
      (node (ref "U27") (pin "S") (pinfunction "EMITTER_S") (pintype "bidirectional"))
    )
    (net (code "5") (name "/50V") (class "Default")
      (node (ref "F1") (pin "1A") (pinfunction "P$1_1A") (pintype "bidirectional"))
      (node (ref "F1") (pin "1B") (pinfunction "P$1_1B") (pintype "bidirectional"))
      (node (ref "F2") (pin "1A") (pinfunction "P$1_1A") (pintype "bidirectional"))
      (node (ref "F2") (pin "1B") (pinfunction "P$1_1B") (pintype "bidirectional"))
      (node (ref "F3") (pin "1A") (pinfunction "P$1_1A") (pintype "bidirectional"))
      (node (ref "F3") (pin "1B") (pinfunction "P$1_1B") (pintype "bidirectional"))
      (node (ref "SOL_PWR") (pin "3") (pinfunction "3_3") (pintype "passive"))
      (node (ref "SOL_PWR") (pin "4") (pinfunction "4_4") (pintype "passive"))
    )
    (net (code "6") (name "/50V_FUSE_0") (class "Default")
      (node (ref "F1") (pin "2A") (pinfunction "P$2_2A") (pintype "bidirectional"))
      (node (ref "F1") (pin "2B") (pinfunction "P$2_2B") (pintype "bidirectional"))
      (node (ref "KNOCKER") (pin "1") (pinfunction "1_1") (pintype "passive"))
      (node (ref "KNOCKER") (pin "2") (pinfunction "2_2") (pintype "passive"))
      (node (ref "SOL_BANK_0") (pin "P$1") (pinfunction "1_P$1") (pintype "bidirectional"))
    )
    (net (code "7") (name "/50V_FUSE_1") (class "Default")
      (node (ref "F2") (pin "2A") (pinfunction "P$2_2A") (pintype "bidirectional"))
      (node (ref "F2") (pin "2B") (pinfunction "P$2_2B") (pintype "bidirectional"))
      (node (ref "SOL_BANK_1") (pin "P$1") (pinfunction "1_P$1") (pintype "bidirectional"))
    )
    (net (code "8") (name "/50V_FUSE_2") (class "Default")
      (node (ref "F3") (pin "2A") (pinfunction "P$2_2A") (pintype "bidirectional"))
      (node (ref "F3") (pin "2B") (pinfunction "P$2_2B") (pintype "bidirectional"))
      (node (ref "SOL_BANK_2") (pin "P$1") (pinfunction "1_P$1") (pintype "bidirectional"))
    )
    (net (code "9") (name "/AC_17") (class "Default")
      (node (ref "AUX_PORT") (pin "P$3") (pinfunction "3_P$3") (pintype "bidirectional"))
      (node (ref "IC2") (pin "49") (pinfunction "SDA3A/SDI3A/U3ARX/PMA9/CN17/RF4_49") (pintype "bidirectional"))
    )
    (net (code "10") (name "/AC_33") (class "Default")
      (node (ref "AUX_PORT") (pin "P$5") (pinfunction "5_P$5") (pintype "bidirectional"))
      (node (ref "IC2") (pin "100") (pinfunction "PMD4/RE4_100") (pintype "bidirectional"))
    )
    (net (code "11") (name "/AC_34") (class "Default")
      (node (ref "AUX_PORT") (pin "P$4") (pinfunction "4_P$4") (pintype "bidirectional"))
      (node (ref "IC2") (pin "99") (pinfunction "PMD3/RE3_99") (pintype "bidirectional"))
    )
    (net (code "12") (name "/AC_44") (class "Default")
      (node (ref "AUX_PORT") (pin "P$2") (pinfunction "2_P$2") (pintype "bidirectional"))
      (node (ref "IC2") (pin "29") (pinfunction "VREF+/CVREF+/AERXD3/PMA6/RA10_29") (pintype "bidirectional"))
    )
    (net (code "13") (name "/AC_46") (class "Default")
      (node (ref "AUX_PORT") (pin "P$1") (pinfunction "1_P$1") (pintype "bidirectional"))
      (node (ref "IC2") (pin "88") (pinfunction "C1TX/ETXD0/PMD10/RF1_88") (pintype "bidirectional"))
    )
    (net (code "14") (name "/AUX_0") (class "Default")
      (node (ref "R35") (pin "1") (pinfunction "1_1") (pintype "passive"))
      (node (ref "TCBTWDN_PORT") (pin "3") (pinfunction "3_3") (pintype "bidirectional"))
      (node (ref "U11") (pin "11") (pinfunction "D0_11") (pintype "bidirectional"))
    )
    (net (code "15") (name "/AUX_1") (class "Default")
      (node (ref "R36") (pin "1") (pinfunction "1_1") (pintype "passive"))
      (node (ref "TCBTWDN_PORT") (pin "4") (pinfunction "4_4") (pintype "bidirectional"))
      (node (ref "U11") (pin "12") (pinfunction "D1_12") (pintype "bidirectional"))
    )
    (net (code "16") (name "/AUX_2") (class "Default")
      (node (ref "R37") (pin "1") (pinfunction "1_1") (pintype "passive"))
      (node (ref "TCBTWDN_PORT") (pin "5") (pinfunction "5_5") (pintype "bidirectional"))
      (node (ref "U11") (pin "13") (pinfunction "D2_13") (pintype "bidirectional"))
    )
    (net (code "17") (name "/AUX_3") (class "Default")
      (node (ref "R39") (pin "1") (pinfunction "1_1") (pintype "passive"))
      (node (ref "TCBTWDN_PORT") (pin "9") (pinfunction "9_9") (pintype "bidirectional"))
      (node (ref "U11") (pin "3") (pinfunction "D4_3") (pintype "bidirectional"))
    )
    (net (code "18") (name "/AUX_4") (class "Default")
      (node (ref "R40") (pin "1") (pinfunction "1_1") (pintype "passive"))
      (node (ref "TCBTWDN_PORT") (pin "8") (pinfunction "8_8") (pintype "bidirectional"))
      (node (ref "U11") (pin "4") (pinfunction "D5_4") (pintype "bidirectional"))
    )
    (net (code "19") (name "/AUX_5") (class "Default")
      (node (ref "R41") (pin "1") (pinfunction "1_1") (pintype "passive"))
      (node (ref "TCBTWDN_PORT") (pin "7") (pinfunction "7_7") (pintype "bidirectional"))
      (node (ref "U11") (pin "5") (pinfunction "D6_5") (pintype "bidirectional"))
    )
    (net (code "20") (name "/AUX_6") (class "Default")
      (node (ref "R42") (pin "1") (pinfunction "1_1") (pintype "passive"))
      (node (ref "TCBTWDN_PORT") (pin "6") (pinfunction "6_6") (pintype "bidirectional"))
      (node (ref "U11") (pin "6") (pinfunction "D7_6") (pintype "bidirectional"))
    )
    (net (code "21") (name "/AVCC") (class "Default")
      (node (ref "C8") (pin "1") (pinfunction "1_1") (pintype "passive"))
      (node (ref "C9") (pin "1") (pinfunction "1_1") (pintype "passive"))
      (node (ref "IC2") (pin "30") (pinfunction "AVDD_30") (pintype "bidirectional"))
      (node (ref "R3") (pin "2") (pinfunction "2_2") (pintype "passive"))
    )
    (net (code "22") (name "/BT_RESET") (class "Default")
      (node (ref "BT1") (pin "5") (pinfunction "RESET_5") (pintype "bidirectional"))
      (node (ref "R138") (pin "2") (pinfunction "2_2") (pintype "passive"))
      (node (ref "SW4") (pin "1") (pinfunction "1_1") (pintype "bidirectional"))
    )
    (net (code "23") (name "/BT_RX") (class "Default")
      (node (ref "BT1") (pin "13") (pinfunction "UARTRX_13") (pintype "bidirectional"))
      (node (ref "BT_RX") (pin "1") (pinfunction "1_1") (pintype "passive"))
    )
    (net (code "24") (name "/BT_TX") (class "Default")
      (node (ref "BT1") (pin "14") (pinfunction "UARTTX_14") (pintype "bidirectional"))
      (node (ref "BT_TX") (pin "1") (pinfunction "1_1") (pintype "passive"))
    )
    (net (code "25") (name "/COIN") (class "Default")
      (node (ref "CABINET") (pin "P$6") (pinfunction "6_P$6") (pintype "bidirectional"))
      (node (ref "R49") (pin "1") (pinfunction "1_1") (pintype "passive"))
      (node (ref "U12") (pin "5") (pinfunction "D6_5") (pintype "bidirectional"))
    )
    (net (code "26") (name "/COMM_ATN") (class "Default")
      (node (ref "IC2") (pin "39") (pinfunction "AC1TX/SCK3A/U3BTX/U3ARTS/RF13_39") (pintype "bidirectional"))
      (node (ref "U1") (pin "31") (pinfunction "P24_31") (pintype "bidirectional"))
    )
    (net (code "27") (name "/COMM_CLK") (class "Default")
      (node (ref "IC2") (pin "40") (pinfunction "AC1RX/SS3A/U3BRX/U3ACTS/RF12_40") (pintype "bidirectional"))
      (node (ref "U1") (pin "32") (pinfunction "P25_32") (pintype "bidirectional"))
    )
    (net (code "28") (name "/COMM_DATA") (class "Default")
      (node (ref "IC2") (pin "50") (pinfunction "SCL3A/SDO3A/U3ATX/PMA8/CN18/RF5_50") (pintype "bidirectional"))
      (node (ref "U1") (pin "33") (pinfunction "P26_33") (pintype "bidirectional"))
    )
    (net (code "29") (name "/D+") (class "Default")
      (node (ref "J2") (pin "D+") (pinfunction "D+_D+") (pintype "bidirectional"))
      (node (ref "R181") (pin "2") (pinfunction "2_2") (pintype "passive"))
    )
    (net (code "30") (name "/D-") (class "Default")
      (node (ref "J2") (pin "D-") (pinfunction "D-_D-") (pintype "bidirectional"))
      (node (ref "R180") (pin "2") (pinfunction "2_2") (pintype "passive"))
    )
    (net (code "31") (name "/DATA_CAB") (class "Default")
      (node (ref "IC2") (pin "87") (pinfunction "C1RX/ETXD1/PMD11/RF0_87") (pintype "bidirectional"))
      (node (ref "U11") (pin "9") (pinfunction "QH_9") (pintype "bidirectional"))
    )
    (net (code "32") (name "/DATA_CAB1") (class "Default")
      (node (ref "U11") (pin "10") (pinfunction "SER_10") (pintype "bidirectional"))
      (node (ref "U12") (pin "9") (pinfunction "QH_9") (pintype "bidirectional"))
    )
    (net (code "33") (name "/DATA_CLK") (class "Default")
      (node (ref "IC2") (pin "93") (pinfunction "PMD0/RE0_93") (pintype "bidirectional"))
      (node (ref "U11") (pin "2") (pinfunction "CLK_2") (pintype "bidirectional"))
      (node (ref "U12") (pin "2") (pinfunction "CLK_2") (pintype "bidirectional"))
      (node (ref "U3") (pin "11") (pinfunction "SHCP_11") (pintype "bidirectional"))
      (node (ref "U5") (pin "11") (pinfunction "SHCP_11") (pintype "bidirectional"))
    )
    (net (code "34") (name "/DATA_LAT") (class "Default")
      (node (ref "IC2") (pin "12") (pinfunction "SCL2A/SDO2A/U2ATX/PMA3/CN10/RG8_12") (pintype "bidirectional"))
      (node (ref "U10") (pin "1") (pinfunction "1A_1") (pintype "bidirectional"))
      (node (ref "U11") (pin "1") (pinfunction "LAT_1") (pintype "bidirectional"))
      (node (ref "U12") (pin "1") (pinfunction "LAT_1") (pintype "bidirectional"))
    )
    (net (code "35") (name "/DM") (class "Default")
      (node (ref "IC1") (pin "16") (pinfunction "USBDM_16") (pintype "bidirectional"))
      (node (ref "J1") (pin "D-") (pinfunction "D-_D-") (pintype "bidirectional"))
    )
    (net (code "36") (name "/DOOR") (class "Default")
      (node (ref "CABINET") (pin "P$9") (pinfunction "9_P$9") (pintype "bidirectional"))
      (node (ref "R43") (pin "1") (pinfunction "1_1") (pintype "passive"))
      (node (ref "U12") (pin "11") (pinfunction "D0_11") (pintype "bidirectional"))
    )
    (net (code "37") (name "/DP") (class "Default")
      (node (ref "IC1") (pin "15") (pinfunction "USBDP_15") (pintype "bidirectional"))
      (node (ref "J1") (pin "D+") (pinfunction "D+_D+") (pintype "bidirectional"))
    )
    (net (code "38") (name "/ENTER") (class "Default")
      (node (ref "CABINET") (pin "P$7") (pinfunction "7_P$7") (pintype "bidirectional"))
      (node (ref "R48") (pin "1") (pinfunction "1_1") (pintype "passive"))
      (node (ref "U12") (pin "4") (pinfunction "D5_4") (pintype "bidirectional"))
    )
    (net (code "39") (name "/FT232_RESET") (class "Default")
      (node (ref "IC1") (pin "19") (pinfunction "RESET#_19") (pintype "bidirectional"))
      (node (ref "R139") (pin "1") (pinfunction "1_1") (pintype "passive"))
      (node (ref "SW4") (pin "3") (pinfunction "3_3") (pintype "bidirectional"))
    )
    (net (code "40") (name "/FT_3.3V") (class "Default")
      (node (ref "C19") (pin "1") (pinfunction "1_1") (pintype "passive"))
      (node (ref "IC1") (pin "17") (pinfunction "3V3OUT_17") (pintype "bidirectional"))
      (node (ref "IC1") (pin "4") (pinfunction "VCCIO_4") (pintype "bidirectional"))
      (node (ref "PIC_RX") (pin "ANODE") (pinfunction "ANODE_ANODE") (pintype "bidirectional"))
      (node (ref "PIC_TX") (pin "ANODE") (pinfunction "ANODE_ANODE") (pintype "bidirectional"))
    )
    (net (code "41") (name "/GI_0") (class "Default")
      (node (ref "R99") (pin "1") (pinfunction "1_1") (pintype "passive"))
      (node (ref "U3") (pin "15") (pinfunction "Q0_15") (pintype "bidirectional"))
    )
    (net (code "42") (name "/GI_1") (class "Default")
      (node (ref "R101") (pin "1") (pinfunction "1_1") (pintype "passive"))
      (node (ref "U3") (pin "1") (pinfunction "Q1_1") (pintype "bidirectional"))
    )
    (net (code "43") (name "/GI_2") (class "Default")
      (node (ref "R103") (pin "1") (pinfunction "1_1") (pintype "passive"))
      (node (ref "U3") (pin "2") (pinfunction "Q2_2") (pintype "bidirectional"))
    )
    (net (code "44") (name "/GI_3") (class "Default")
      (node (ref "R105") (pin "1") (pinfunction "1_1") (pintype "passive"))
      (node (ref "U3") (pin "3") (pinfunction "Q3_3") (pintype "bidirectional"))
    )
    (net (code "45") (name "/GI_4") (class "Default")
      (node (ref "R107") (pin "1") (pinfunction "1_1") (pintype "passive"))
      (node (ref "U3") (pin "4") (pinfunction "Q4_4") (pintype "bidirectional"))
    )
    (net (code "46") (name "/GI_5") (class "Default")
      (node (ref "R109") (pin "1") (pinfunction "1_1") (pintype "passive"))
      (node (ref "U3") (pin "5") (pinfunction "Q5_5") (pintype "bidirectional"))
    )
    (net (code "47") (name "/GI_6") (class "Default")
      (node (ref "R111") (pin "1") (pinfunction "1_1") (pintype "passive"))
      (node (ref "U3") (pin "6") (pinfunction "Q6_6") (pintype "bidirectional"))
    )
    (net (code "48") (name "/GI_7") (class "Default")
      (node (ref "R113") (pin "1") (pinfunction "1_1") (pintype "passive"))
      (node (ref "U3") (pin "7") (pinfunction "Q7_7") (pintype "bidirectional"))
    )
    (net (code "49") (name "/GI_8") (class "Default")
      (node (ref "R125") (pin "1") (pinfunction "1_1") (pintype "passive"))
      (node (ref "U5") (pin "15") (pinfunction "Q0_15") (pintype "bidirectional"))
    )
    (net (code "50") (name "/GI_9") (class "Default")
      (node (ref "R126") (pin "1") (pinfunction "1_1") (pintype "passive"))
      (node (ref "U5") (pin "1") (pinfunction "Q1_1") (pintype "bidirectional"))
    )
    (net (code "51") (name "/GI_10") (class "Default")
      (node (ref "R127") (pin "1") (pinfunction "1_1") (pintype "passive"))
      (node (ref "U5") (pin "2") (pinfunction "Q2_2") (pintype "bidirectional"))
    )
    (net (code "52") (name "/GI_11") (class "Default")
      (node (ref "R128") (pin "1") (pinfunction "1_1") (pintype "passive"))
      (node (ref "U5") (pin "3") (pinfunction "Q3_3") (pintype "bidirectional"))
    )
    (net (code "53") (name "/GI_12") (class "Default")
      (node (ref "R129") (pin "1") (pinfunction "1_1") (pintype "passive"))
      (node (ref "U5") (pin "4") (pinfunction "Q4_4") (pintype "bidirectional"))
    )
    (net (code "54") (name "/GI_13") (class "Default")
      (node (ref "R130") (pin "1") (pinfunction "1_1") (pintype "passive"))
      (node (ref "U5") (pin "5") (pinfunction "Q5_5") (pintype "bidirectional"))
    )
    (net (code "55") (name "/GI_14") (class "Default")
      (node (ref "R131") (pin "1") (pinfunction "1_1") (pintype "passive"))
      (node (ref "U5") (pin "6") (pinfunction "Q6_6") (pintype "bidirectional"))
    )
    (net (code "56") (name "/GI_15") (class "Default")
      (node (ref "R132") (pin "1") (pinfunction "1_1") (pintype "passive"))
      (node (ref "U5") (pin "7") (pinfunction "Q7_7") (pintype "bidirectional"))
    )
    (net (code "57") (name "/GI_DATA_COL") (class "Default")
      (node (ref "IC2") (pin "11") (pinfunction "ECRS/SDA2A/SDI2A/U2ARX/PMA4/CN9/RG7_11") (pintype "bidirectional"))
      (node (ref "U3") (pin "14") (pinfunction "DS_14") (pintype "bidirectional"))
    )
    (net (code "58") (name "/GI_DATA_COL_B") (class "Default")
      (node (ref "U3") (pin "9") (pinfunction "Q7S_9") (pintype "bidirectional"))
      (node (ref "U5") (pin "14") (pinfunction "DS_14") (pintype "bidirectional"))
    )
    (net (code "59") (name "/GI_R_0") (class "Default")
      (node (ref "GI_0") (pin "P$1") (pinfunction "1_P$1") (pintype "bidirectional"))
      (node (ref "U6") (pin "D") (pinfunction "COLLECTOR_D") (pintype "bidirectional"))
    )
    (net (code "60") (name "/GI_R_1") (class "Default")
      (node (ref "GI_0") (pin "P$2") (pinfunction "2_P$2") (pintype "bidirectional"))
      (node (ref "U7") (pin "D") (pinfunction "COLLECTOR_D") (pintype "bidirectional"))
    )
    (net (code "61") (name "/GI_R_2") (class "Default")
      (node (ref "GI_0") (pin "P$3") (pinfunction "3_P$3") (pintype "bidirectional"))
      (node (ref "U8") (pin "D") (pinfunction "COLLECTOR_D") (pintype "bidirectional"))
    )
    (net (code "62") (name "/GI_R_3") (class "Default")
      (node (ref "GI_0") (pin "P$4") (pinfunction "4_P$4") (pintype "bidirectional"))
      (node (ref "U9") (pin "D") (pinfunction "COLLECTOR_D") (pintype "bidirectional"))
    )
    (net (code "63") (name "/GI_R_4") (class "Default")
      (node (ref "GI_0") (pin "P$5") (pinfunction "5_P$5") (pintype "bidirectional"))
      (node (ref "U40") (pin "D") (pinfunction "COLLECTOR_D") (pintype "bidirectional"))
    )
    (net (code "64") (name "/GI_R_5") (class "Default")
      (node (ref "GI_0") (pin "P$6") (pinfunction "6_P$6") (pintype "bidirectional"))
      (node (ref "U41") (pin "D") (pinfunction "COLLECTOR_D") (pintype "bidirectional"))
    )
    (net (code "65") (name "/GI_R_6") (class "Default")
      (node (ref "GI_0") (pin "P$7") (pinfunction "7_P$7") (pintype "bidirectional"))
      (node (ref "U42") (pin "D") (pinfunction "COLLECTOR_D") (pintype "bidirectional"))
    )
    (net (code "66") (name "/GI_R_7") (class "Default")
      (node (ref "GI_0") (pin "P$8") (pinfunction "8_P$8") (pintype "bidirectional"))
      (node (ref "U43") (pin "D") (pinfunction "COLLECTOR_D") (pintype "bidirectional"))
    )
    (net (code "67") (name "/GI_R_8") (class "Default")
      (node (ref "GI_1") (pin "P$1") (pinfunction "1_P$1") (pintype "bidirectional"))
      (node (ref "U44") (pin "D") (pinfunction "COLLECTOR_D") (pintype "bidirectional"))
    )
    (net (code "68") (name "/GI_R_9") (class "Default")
      (node (ref "GI_1") (pin "P$2") (pinfunction "2_P$2") (pintype "bidirectional"))
      (node (ref "U45") (pin "D") (pinfunction "COLLECTOR_D") (pintype "bidirectional"))
    )
    (net (code "69") (name "/GI_R_10") (class "Default")
      (node (ref "GI_1") (pin "P$3") (pinfunction "3_P$3") (pintype "bidirectional"))
      (node (ref "U46") (pin "D") (pinfunction "COLLECTOR_D") (pintype "bidirectional"))
    )
    (net (code "70") (name "/GI_R_11") (class "Default")
      (node (ref "GI_1") (pin "P$4") (pinfunction "4_P$4") (pintype "bidirectional"))
      (node (ref "U47") (pin "D") (pinfunction "COLLECTOR_D") (pintype "bidirectional"))
    )
    (net (code "71") (name "/GI_R_12") (class "Default")
      (node (ref "GI_1") (pin "P$5") (pinfunction "5_P$5") (pintype "bidirectional"))
      (node (ref "U48") (pin "D") (pinfunction "COLLECTOR_D") (pintype "bidirectional"))
    )
    (net (code "72") (name "/GI_R_13") (class "Default")
      (node (ref "GI_1") (pin "P$6") (pinfunction "6_P$6") (pintype "bidirectional"))
      (node (ref "U49") (pin "D") (pinfunction "COLLECTOR_D") (pintype "bidirectional"))
    )
    (net (code "73") (name "/GI_R_14") (class "Default")
      (node (ref "GI_1") (pin "P$7") (pinfunction "7_P$7") (pintype "bidirectional"))
      (node (ref "U50") (pin "D") (pinfunction "COLLECTOR_D") (pintype "bidirectional"))
    )
    (net (code "74") (name "/GI_R_15") (class "Default")
      (node (ref "GI_1") (pin "P$8") (pinfunction "8_P$8") (pintype "bidirectional"))
      (node (ref "U51") (pin "D") (pinfunction "COLLECTOR_D") (pintype "bidirectional"))
    )
    (net (code "75") (name "/GND") (class "Default")
      (node (ref "AUX_PORT") (pin "P$12") (pinfunction "12_P$12") (pintype "bidirectional"))
      (node (ref "AUX_PWR") (pin "1") (pinfunction "1_1") (pintype "passive"))
      (node (ref "AUX_PWR") (pin "3") (pinfunction "3_3") (pintype "passive"))
      (node (ref "BOARD_POWER") (pin "1") (pinfunction "1_1") (pintype "bidirectional"))
      (node (ref "BOARD_POWER") (pin "3") (pinfunction "3_3") (pintype "bidirectional"))
      (node (ref "BOARD_POWER") (pin "5") (pinfunction "5_5") (pintype "bidirectional"))
      (node (ref "BOARD_POWER") (pin "8") (pinfunction "8_8") (pintype "bidirectional"))
      (node (ref "BT1") (pin "1") (pinfunction "GND_1") (pintype "bidirectional"))
      (node (ref "BT1") (pin "12") (pinfunction "GND1_12") (pintype "bidirectional"))
      (node (ref "BT1") (pin "25") (pinfunction "GND2_25") (pintype "bidirectional"))
      (node (ref "BT1") (pin "27") (pinfunction "GND3_27") (pintype "bidirectional"))
      (node (ref "BT1") (pin "28") (pinfunction "GND4_28") (pintype "bidirectional"))
      (node (ref "BT1") (pin "29") (pinfunction "GND5_29") (pintype "bidirectional"))
      (node (ref "C10") (pin "2") (pinfunction "2_2") (pintype "passive"))
      (node (ref "C11") (pin "2") (pinfunction "2_2") (pintype "passive"))
      (node (ref "C12") (pin "2") (pinfunction "2_2") (pintype "passive"))
      (node (ref "C13") (pin "2") (pinfunction "2_2") (pintype "passive"))
      (node (ref "C14") (pin "2") (pinfunction "2_2") (pintype "passive"))
      (node (ref "C15") (pin "2") (pinfunction "2_2") (pintype "passive"))
      (node (ref "C16") (pin "2") (pinfunction "2_2") (pintype "passive"))
      (node (ref "C18") (pin "2") (pinfunction "2_2") (pintype "passive"))
      (node (ref "C19") (pin "2") (pinfunction "2_2") (pintype "passive"))
      (node (ref "C2") (pin "2") (pinfunction "2_2") (pintype "passive"))
      (node (ref "C20") (pin "1") (pinfunction "1_1") (pintype "passive"))
      (node (ref "C21") (pin "1") (pinfunction "1_1") (pintype "passive"))
      (node (ref "C22") (pin "1") (pinfunction "1_1") (pintype "passive"))
      (node (ref "C23") (pin "1") (pinfunction "1_1") (pintype "passive"))
      (node (ref "C24") (pin "1") (pinfunction "1_1") (pintype "passive"))
      (node (ref "C25") (pin "1") (pinfunction "1_1") (pintype "passive"))
      (node (ref "C26") (pin "1") (pinfunction "1_1") (pintype "passive"))
      (node (ref "C27") (pin "NEG") (pinfunction "NEG_NEG") (pintype "bidirectional"))
      (node (ref "C28") (pin "1") (pinfunction "1_1") (pintype "passive"))
      (node (ref "C29") (pin "2") (pinfunction "2_2") (pintype "passive"))
      (node (ref "C3") (pin "2") (pinfunction "2_2") (pintype "passive"))
      (node (ref "C30") (pin "P$2") (pinfunction "P$2_P$2") (pintype "passive"))
      (node (ref "C32") (pin "1") (pinfunction "1_1") (pintype "passive"))
      (node (ref "C33") (pin "1") (pinfunction "1_1") (pintype "passive"))
      (node (ref "C34") (pin "NEG") (pinfunction "NEG_NEG") (pintype "bidirectional"))
      (node (ref "C35") (pin "2") (pinfunction "2_2") (pintype "passive"))
      (node (ref "C36") (pin "2") (pinfunction "2_2") (pintype "passive"))
      (node (ref "C37") (pin "2") (pinfunction "2_2") (pintype "passive"))
      (node (ref "C38") (pin "NEG") (pinfunction "NEG_NEG") (pintype "bidirectional"))
      (node (ref "C39") (pin "2") (pinfunction "2_2") (pintype "passive"))
      (node (ref "C4") (pin "2") (pinfunction "2_2") (pintype "passive"))
      (node (ref "C40") (pin "2") (pinfunction "2_2") (pintype "passive"))
      (node (ref "C41") (pin "2") (pinfunction "2_2") (pintype "passive"))
      (node (ref "C42") (pin "NEG") (pinfunction "NEG_NEG") (pintype "bidirectional"))
      (node (ref "C43") (pin "2") (pinfunction "2_2") (pintype "passive"))
      (node (ref "C44") (pin "2") (pinfunction "2_2") (pintype "passive"))
      (node (ref "C45") (pin "2") (pinfunction "2_2") (pintype "passive"))
      (node (ref "C46") (pin "1") (pinfunction "1_1") (pintype "passive"))
      (node (ref "C48") (pin "2") (pinfunction "2_2") (pintype "passive"))
      (node (ref "C5") (pin "2") (pinfunction "2_2") (pintype "passive"))
      (node (ref "C50") (pin "NEG") (pinfunction "NEG_NEG") (pintype "bidirectional"))
      (node (ref "C51") (pin "2") (pinfunction "2_2") (pintype "passive"))
      (node (ref "C52") (pin "2") (pinfunction "2_2") (pintype "passive"))
      (node (ref "C53") (pin "2") (pinfunction "2_2") (pintype "passive"))
      (node (ref "C6") (pin "2") (pinfunction "2_2") (pintype "passive"))
      (node (ref "C7") (pin "2") (pinfunction "2_2") (pintype "passive"))
      (node (ref "C8") (pin "2") (pinfunction "2_2") (pintype "passive"))
      (node (ref "C9") (pin "2") (pinfunction "2_2") (pintype "passive"))
      (node (ref "CABINET") (pin "P$1") (pinfunction "1_P$1") (pintype "bidirectional"))
      (node (ref "D1") (pin "1") (pinfunction "CAT_1") (pintype "bidirectional"))
      (node (ref "D8") (pin "2") (pinfunction "COM_2") (pintype "bidirectional"))
      (node (ref "DMD_CON") (pin "10") (pinfunction "10_10") (pintype "bidirectional"))
      (node (ref "DMD_CON") (pin "11") (pinfunction "11_11") (pintype "bidirectional"))
      (node (ref "DMD_CON") (pin "12") (pinfunction "12_12") (pintype "bidirectional"))
      (node (ref "DMD_CON") (pin "13") (pinfunction "13_13") (pintype "bidirectional"))
      (node (ref "DMD_CON") (pin "14") (pinfunction "14_14") (pintype "bidirectional"))
      (node (ref "DMD_CON") (pin "8") (pinfunction "8_8") (pintype "bidirectional"))
      (node (ref "DMD_CON") (pin "9") (pinfunction "9_9") (pintype "bidirectional"))
      (node (ref "DMD_PWR") (pin "P$2") (pinfunction "2_P$2") (pintype "passive"))
      (node (ref "IC1") (pin "18") (pinfunction "GND_18") (pintype "bidirectional"))
      (node (ref "IC1") (pin "21") (pinfunction "GND_21") (pintype "bidirectional"))
      (node (ref "IC1") (pin "25") (pinfunction "AGND_25") (pintype "bidirectional"))
      (node (ref "IC1") (pin "26") (pinfunction "TEST_26") (pintype "bidirectional"))
      (node (ref "IC1") (pin "7") (pinfunction "GND_7") (pintype "bidirectional"))
      (node (ref "IC2") (pin "15") (pinfunction "VSS_15") (pintype "bidirectional"))
      (node (ref "IC2") (pin "31") (pinfunction "AVSS_31") (pintype "bidirectional"))
      (node (ref "IC2") (pin "36") (pinfunction "VSS_36") (pintype "bidirectional"))
      (node (ref "IC2") (pin "45") (pinfunction "VSS_45") (pintype "bidirectional"))
      (node (ref "IC2") (pin "65") (pinfunction "VSS_65") (pintype "bidirectional"))
      (node (ref "IC2") (pin "75") (pinfunction "VSS_75") (pintype "bidirectional"))
      (node (ref "IC3") (pin "1") (pinfunction "G_1") (pintype "input"))
      (node (ref "IC3") (pin "10") (pinfunction "GND_10") (pintype "power_in"))
      (node (ref "IC3") (pin "19") (pinfunction "G_19") (pintype "input"))
      (node (ref "IC4") (pin "1") (pinfunction "G_1") (pintype "input"))
      (node (ref "IC4") (pin "10") (pinfunction "GND_10") (pintype "power_in"))
      (node (ref "IC4") (pin "19") (pinfunction "G_19") (pintype "input"))
      (node (ref "IC5") (pin "9") (pinfunction "GND_9") (pintype "power_in"))
      (node (ref "J1") (pin "GND") (pinfunction "GND_GND") (pintype "bidirectional"))
      (node (ref "J1") (pin "P$1") (pinfunction "GND_P$1") (pintype "bidirectional"))
      (node (ref "J1") (pin "P$2") (pinfunction "GND_P$2") (pintype "bidirectional"))
      (node (ref "J1") (pin "P$3") (pinfunction "GND_P$3") (pintype "bidirectional"))
      (node (ref "J1") (pin "P$4") (pinfunction "GND_P$4") (pintype "bidirectional"))
      (node (ref "J11") (pin "3") (pinfunction "3_3") (pintype "passive"))
      (node (ref "J2") (pin "GND") (pinfunction "GND_GND") (pintype "bidirectional"))
      (node (ref "J2") (pin "P$1") (pinfunction "GND_P$1") (pintype "bidirectional"))
      (node (ref "J2") (pin "P$2") (pinfunction "GND_P$2") (pintype "bidirectional"))
      (node (ref "J2") (pin "P$3") (pinfunction "GND_P$3") (pintype "bidirectional"))
      (node (ref "J2") (pin "P$4") (pinfunction "GND_P$4") (pintype "bidirectional"))
      (node (ref "J3") (pin "2") (pinfunction "2_2") (pintype "passive"))
      (node (ref "J3") (pin "3") (pinfunction "3_3") (pintype "passive"))
      (node (ref "J6") (pin "1") (pinfunction "S_1") (pintype "bidirectional"))
      (node (ref "NEO_PIXEL") (pin "2") (pinfunction "2_2") (pintype "passive"))
      (node (ref "R11") (pin "1") (pinfunction "1_1") (pintype "passive"))
      (node (ref "R115") (pin "1") (pinfunction "1_1") (pintype "passive"))
      (node (ref "R117") (pin "1") (pinfunction "1_1") (pintype "passive"))
      (node (ref "R118") (pin "2") (pinfunction "2_2") (pintype "passive"))
      (node (ref "R133") (pin "2") (pinfunction "2_2") (pintype "passive"))
      (node (ref "R135") (pin "2") (pinfunction "2_2") (pintype "passive"))
      (node (ref "R136") (pin "1") (pinfunction "1_1") (pintype "passive"))
      (node (ref "R138") (pin "1") (pinfunction "1_1") (pintype "passive"))
      (node (ref "R139") (pin "2") (pinfunction "2_2") (pintype "passive"))
      (node (ref "R30") (pin "1") (pinfunction "1_1") (pintype "passive"))
      (node (ref "R5") (pin "1") (pinfunction "1_1") (pintype "passive"))
      (node (ref "R51") (pin "1") (pinfunction "1_1") (pintype "passive"))
      (node (ref "R52") (pin "1") (pinfunction "1_1") (pintype "passive"))
      (node (ref "R53") (pin "1") (pinfunction "1_1") (pintype "passive"))
      (node (ref "R54") (pin "1") (pinfunction "1_1") (pintype "passive"))
      (node (ref "R55") (pin "1") (pinfunction "1_1") (pintype "passive"))
      (node (ref "R56") (pin "1") (pinfunction "1_1") (pintype "passive"))
      (node (ref "R57") (pin "1") (pinfunction "1_1") (pintype "passive"))
      (node (ref "R58") (pin "1") (pinfunction "1_1") (pintype "passive"))
      (node (ref "R59") (pin "1") (pinfunction "1_1") (pintype "passive"))
      (node (ref "R60") (pin "1") (pinfunction "1_1") (pintype "passive"))
      (node (ref "R61") (pin "1") (pinfunction "1_1") (pintype "passive"))
      (node (ref "R62") (pin "1") (pinfunction "1_1") (pintype "passive"))
      (node (ref "R63") (pin "1") (pinfunction "1_1") (pintype "passive"))
      (node (ref "R64") (pin "1") (pinfunction "1_1") (pintype "passive"))
      (node (ref "R65") (pin "1") (pinfunction "1_1") (pintype "passive"))
      (node (ref "R66") (pin "1") (pinfunction "1_1") (pintype "passive"))
      (node (ref "R67") (pin "1") (pinfunction "1_1") (pintype "passive"))
      (node (ref "R68") (pin "1") (pinfunction "1_1") (pintype "passive"))
      (node (ref "R69") (pin "1") (pinfunction "1_1") (pintype "passive"))
      (node (ref "R70") (pin "1") (pinfunction "1_1") (pintype "passive"))
      (node (ref "R71") (pin "1") (pinfunction "1_1") (pintype "passive"))
      (node (ref "R72") (pin "1") (pinfunction "1_1") (pintype "passive"))
      (node (ref "R73") (pin "1") (pinfunction "1_1") (pintype "passive"))
      (node (ref "R74") (pin "1") (pinfunction "1_1") (pintype "passive"))
      (node (ref "RGB_0") (pin "S") (pinfunction "SOURCE_S") (pintype "bidirectional"))
      (node (ref "RGB_1") (pin "S") (pinfunction "SOURCE_S") (pintype "bidirectional"))
      (node (ref "RGB_2") (pin "S") (pinfunction "SOURCE_S") (pintype "bidirectional"))
      (node (ref "RGB_3") (pin "S") (pinfunction "SOURCE_S") (pintype "bidirectional"))
      (node (ref "RGB_4") (pin "S") (pinfunction "SOURCE_S") (pintype "bidirectional"))
      (node (ref "RGB_5") (pin "S") (pinfunction "SOURCE_S") (pintype "bidirectional"))
      (node (ref "SD0") (pin "3") (pinfunction "GND_3") (pintype "bidirectional"))
      (node (ref "SD0") (pin "6") (pinfunction "GND_6") (pintype "bidirectional"))
      (node (ref "SD0") (pin "GND_1") (pinfunction "GND_GND_1") (pintype "bidirectional"))
      (node (ref "SD0") (pin "GND_2") (pinfunction "GND_GND_2") (pintype "bidirectional"))
      (node (ref "SW1") (pin "P$1") (pinfunction "P$1_P$1") (pintype "bidirectional"))
      (node (ref "SW2") (pin "P$2") (pinfunction "P$2_P$2") (pintype "bidirectional"))
      (node (ref "SW3") (pin "P$1") (pinfunction "P$1_P$1") (pintype "bidirectional"))
      (node (ref "SW3") (pin "P$2") (pinfunction "P$2_P$2") (pintype "bidirectional"))
      (node (ref "SW_COL") (pin "P$1") (pinfunction "1_P$1") (pintype "bidirectional"))
      (node (ref "SW_ROW") (pin "P$1") (pinfunction "1_P$1") (pintype "bidirectional"))
      (node (ref "TCBTWDN_PORT") (pin "2") (pinfunction "2_2") (pintype "bidirectional"))
      (node (ref "U1") (pin "17") (pinfunction "VSS_17") (pintype "bidirectional"))
      (node (ref "U1") (pin "27") (pinfunction "VSS_27") (pintype "bidirectional"))
      (node (ref "U1") (pin "39") (pinfunction "VSS_39") (pintype "bidirectional"))
      (node (ref "U1") (pin "5") (pinfunction "VSS_5") (pintype "bidirectional"))
      (node (ref "U1") (pin "6") (pinfunction "BOE'_6") (pintype "bidirectional"))
      (node (ref "U10") (pin "2") (pinfunction "GND_2") (pintype "bidirectional"))
      (node (ref "U11") (pin "15") (pinfunction "C_INH_15") (pintype "bidirectional"))
      (node (ref "U11") (pin "8") (pinfunction "GND_8") (pintype "bidirectional"))
      (node (ref "U12") (pin "15") (pinfunction "C_INH_15") (pintype "bidirectional"))
      (node (ref "U12") (pin "8") (pinfunction "GND_8") (pintype "bidirectional"))
      (node (ref "U14") (pin "7") (pinfunction "GND_7") (pintype "bidirectional"))
      (node (ref "U15") (pin "7") (pinfunction "GND_7") (pintype "bidirectional"))
      (node (ref "U16") (pin "7") (pinfunction "GND_7") (pintype "bidirectional"))
      (node (ref "U17") (pin "7") (pinfunction "GND_7") (pintype "bidirectional"))
      (node (ref "U18") (pin "7") (pinfunction "GND_7") (pintype "bidirectional"))
      (node (ref "U19") (pin "7") (pinfunction "GND_7") (pintype "bidirectional"))
      (node (ref "U2") (pin "13") (pinfunction "GND_13") (pintype "bidirectional"))
      (node (ref "U2") (pin "5") (pinfunction "GND_5") (pintype "bidirectional"))
      (node (ref "U28") (pin "S") (pinfunction "EMITTER_S") (pintype "bidirectional"))
      (node (ref "U29") (pin "S") (pinfunction "EMITTER_S") (pintype "bidirectional"))
      (node (ref "U3") (pin "13") (pinfunction "OE_13") (pintype "bidirectional"))
      (node (ref "U3") (pin "8") (pinfunction "GND_8") (pintype "bidirectional"))
      (node (ref "U30") (pin "S") (pinfunction "EMITTER_S") (pintype "bidirectional"))
      (node (ref "U31") (pin "S") (pinfunction "EMITTER_S") (pintype "bidirectional"))
      (node (ref "U32") (pin "S") (pinfunction "EMITTER_S") (pintype "bidirectional"))
      (node (ref "U33") (pin "S") (pinfunction "EMITTER_S") (pintype "bidirectional"))
      (node (ref "U34") (pin "S") (pinfunction "EMITTER_S") (pintype "bidirectional"))
      (node (ref "U35") (pin "S") (pinfunction "EMITTER_S") (pintype "bidirectional"))
      (node (ref "U36") (pin "3") (pinfunction "POL_3") (pintype "bidirectional"))
      (node (ref "U36") (pin "4") (pinfunction "RFB_4") (pintype "bidirectional"))
      (node (ref "U36") (pin "5") (pinfunction "GFB_5") (pintype "bidirectional"))
      (node (ref "U36") (pin "6") (pinfunction "BFB_6") (pintype "bidirectional"))
      (node (ref "U36") (pin "7") (pinfunction "GND_7") (pintype "bidirectional"))
      (node (ref "U37") (pin "S") (pinfunction "EMITTER_S") (pintype "bidirectional"))
      (node (ref "U38") (pin "3") (pinfunction "POL_3") (pintype "bidirectional"))
      (node (ref "U38") (pin "4") (pinfunction "RFB_4") (pintype "bidirectional"))
      (node (ref "U38") (pin "5") (pinfunction "GFB_5") (pintype "bidirectional"))
      (node (ref "U38") (pin "6") (pinfunction "BFB_6") (pintype "bidirectional"))
      (node (ref "U38") (pin "7") (pinfunction "GND_7") (pintype "bidirectional"))
      (node (ref "U39") (pin "COM1") (pinfunction "GND_COM1") (pintype "bidirectional"))
      (node (ref "U39") (pin "COM2") (pinfunction "GND_COM2") (pintype "bidirectional"))
      (node (ref "U4") (pin "2") (pinfunction "A1_2") (pintype "bidirectional"))
      (node (ref "U4") (pin "3") (pinfunction "A2_3") (pintype "bidirectional"))
      (node (ref "U4") (pin "4") (pinfunction "GND_4") (pintype "bidirectional"))
      (node (ref "U4") (pin "7") (pinfunction "WP_7") (pintype "bidirectional"))
      (node (ref "U40") (pin "S") (pinfunction "EMITTER_S") (pintype "bidirectional"))
      (node (ref "U41") (pin "S") (pinfunction "EMITTER_S") (pintype "bidirectional"))
      (node (ref "U42") (pin "S") (pinfunction "EMITTER_S") (pintype "bidirectional"))
      (node (ref "U43") (pin "S") (pinfunction "EMITTER_S") (pintype "bidirectional"))
      (node (ref "U44") (pin "S") (pinfunction "EMITTER_S") (pintype "bidirectional"))
      (node (ref "U45") (pin "S") (pinfunction "EMITTER_S") (pintype "bidirectional"))
      (node (ref "U46") (pin "S") (pinfunction "EMITTER_S") (pintype "bidirectional"))
      (node (ref "U47") (pin "S") (pinfunction "EMITTER_S") (pintype "bidirectional"))
      (node (ref "U48") (pin "S") (pinfunction "EMITTER_S") (pintype "bidirectional"))
      (node (ref "U49") (pin "S") (pinfunction "EMITTER_S") (pintype "bidirectional"))
      (node (ref "U5") (pin "13") (pinfunction "OE_13") (pintype "bidirectional"))
      (node (ref "U5") (pin "8") (pinfunction "GND_8") (pintype "bidirectional"))
      (node (ref "U50") (pin "S") (pinfunction "EMITTER_S") (pintype "bidirectional"))
      (node (ref "U51") (pin "S") (pinfunction "EMITTER_S") (pintype "bidirectional"))
      (node (ref "U52") (pin "14") (pinfunction "1CX_14") (pintype "bidirectional"))
      (node (ref "U52") (pin "8") (pinfunction "GND_8") (pintype "bidirectional"))
      (node (ref "U6") (pin "S") (pinfunction "EMITTER_S") (pintype "bidirectional"))
      (node (ref "U7") (pin "S") (pinfunction "EMITTER_S") (pintype "bidirectional"))
      (node (ref "U8") (pin "S") (pinfunction "EMITTER_S") (pintype "bidirectional"))
      (node (ref "U9") (pin "S") (pinfunction "EMITTER_S") (pintype "bidirectional"))
    )
    (net (code "76") (name "/I2C_SCL") (class "Default")
      (node (ref "AUX_PORT") (pin "P$11") (pinfunction "11_P$11") (pintype "bidirectional"))
      (node (ref "IC2") (pin "66") (pinfunction "AETXCLK/SCL1/INT3/RA14_66") (pintype "bidirectional"))
    )
    (net (code "77") (name "/I2C_SDA") (class "Default")
      (node (ref "AUX_PORT") (pin "P$10") (pinfunction "10_P$10") (pintype "bidirectional"))
      (node (ref "IC2") (pin "67") (pinfunction "AETXEN/SDA1/INT4/RA15_67") (pintype "bidirectional"))
    )
    (net (code "78") (name "/LIGHT_C_0") (class "Default")
      (node (ref "LIGHT_COL") (pin "P$3") (pinfunction "3_P$3") (pintype "bidirectional"))
      (node (ref "U20") (pin "D") (pinfunction "COLLECTOR_D") (pintype "bidirectional"))
    )
    (net (code "79") (name "/LIGHT_C_1") (class "Default")
      (node (ref "LIGHT_COL") (pin "P$4") (pinfunction "4_P$4") (pintype "bidirectional"))
      (node (ref "U21") (pin "D") (pinfunction "COLLECTOR_D") (pintype "bidirectional"))
    )
    (net (code "80") (name "/LIGHT_C_2") (class "Default")
      (node (ref "LIGHT_COL") (pin "P$5") (pinfunction "5_P$5") (pintype "bidirectional"))
      (node (ref "U22") (pin "D") (pinfunction "COLLECTOR_D") (pintype "bidirectional"))
    )
    (net (code "81") (name "/LIGHT_C_3") (class "Default")
      (node (ref "LIGHT_COL") (pin "P$6") (pinfunction "6_P$6") (pintype "bidirectional"))
      (node (ref "U23") (pin "D") (pinfunction "COLLECTOR_D") (pintype "bidirectional"))
    )
    (net (code "82") (name "/LIGHT_C_4") (class "Default")
      (node (ref "LIGHT_COL") (pin "P$7") (pinfunction "7_P$7") (pintype "bidirectional"))
      (node (ref "U24") (pin "D") (pinfunction "COLLECTOR_D") (pintype "bidirectional"))
    )
    (net (code "83") (name "/LIGHT_C_5") (class "Default")
      (node (ref "LIGHT_COL") (pin "P$8") (pinfunction "8_P$8") (pintype "bidirectional"))
      (node (ref "U25") (pin "D") (pinfunction "COLLECTOR_D") (pintype "bidirectional"))
    )
    (net (code "84") (name "/LIGHT_C_6") (class "Default")
      (node (ref "LIGHT_COL") (pin "P$9") (pinfunction "9_P$9") (pintype "bidirectional"))
      (node (ref "U26") (pin "D") (pinfunction "COLLECTOR_D") (pintype "bidirectional"))
    )
    (net (code "85") (name "/LIGHT_C_7") (class "Default")
      (node (ref "LIGHT_COL") (pin "P$10") (pinfunction "10_P$10") (pintype "bidirectional"))
      (node (ref "U27") (pin "D") (pinfunction "COLLECTOR_D") (pintype "bidirectional"))
    )
    (net (code "86") (name "/LIGHT_C_B_0") (class "Default")
      (node (ref "R83") (pin "2") (pinfunction "2_2") (pintype "passive"))
      (node (ref "R84") (pin "2") (pinfunction "2_2") (pintype "passive"))
      (node (ref "U20") (pin "G") (pinfunction "BASE_G") (pintype "bidirectional"))
    )
    (net (code "87") (name "/LIGHT_C_B_1") (class "Default")
      (node (ref "R85") (pin "2") (pinfunction "2_2") (pintype "passive"))
      (node (ref "R86") (pin "2") (pinfunction "2_2") (pintype "passive"))
      (node (ref "U21") (pin "G") (pinfunction "BASE_G") (pintype "bidirectional"))
    )
    (net (code "88") (name "/LIGHT_C_B_2") (class "Default")
      (node (ref "R87") (pin "2") (pinfunction "2_2") (pintype "passive"))
      (node (ref "R88") (pin "2") (pinfunction "2_2") (pintype "passive"))
      (node (ref "U22") (pin "G") (pinfunction "BASE_G") (pintype "bidirectional"))
    )
    (net (code "89") (name "/LIGHT_C_B_3") (class "Default")
      (node (ref "R89") (pin "2") (pinfunction "2_2") (pintype "passive"))
      (node (ref "R90") (pin "2") (pinfunction "2_2") (pintype "passive"))
      (node (ref "U23") (pin "G") (pinfunction "BASE_G") (pintype "bidirectional"))
    )
    (net (code "90") (name "/LIGHT_C_B_4") (class "Default")
      (node (ref "R91") (pin "2") (pinfunction "2_2") (pintype "passive"))
      (node (ref "R92") (pin "2") (pinfunction "2_2") (pintype "passive"))
      (node (ref "U24") (pin "G") (pinfunction "BASE_G") (pintype "bidirectional"))
    )
    (net (code "91") (name "/LIGHT_C_B_5") (class "Default")
      (node (ref "R93") (pin "2") (pinfunction "2_2") (pintype "passive"))
      (node (ref "R94") (pin "2") (pinfunction "2_2") (pintype "passive"))
      (node (ref "U25") (pin "G") (pinfunction "BASE_G") (pintype "bidirectional"))
    )
    (net (code "92") (name "/LIGHT_C_B_6") (class "Default")
      (node (ref "R95") (pin "2") (pinfunction "2_2") (pintype "passive"))
      (node (ref "R96") (pin "2") (pinfunction "2_2") (pintype "passive"))
      (node (ref "U26") (pin "G") (pinfunction "BASE_G") (pintype "bidirectional"))
    )
    (net (code "93") (name "/LIGHT_C_B_7") (class "Default")
      (node (ref "R97") (pin "2") (pinfunction "2_2") (pintype "passive"))
      (node (ref "R98") (pin "2") (pinfunction "2_2") (pintype "passive"))
      (node (ref "U27") (pin "G") (pinfunction "BASE_G") (pintype "bidirectional"))
    )
    (net (code "94") (name "/LIGHT_DTA_0") (class "Default")
      (node (ref "IC5") (pin "11") (pinfunction "O8_11") (pintype "open_collector"))
      (node (ref "R84") (pin "1") (pinfunction "1_1") (pintype "passive"))
    )
    (net (code "95") (name "/LIGHT_DTA_1") (class "Default")
      (node (ref "IC5") (pin "12") (pinfunction "O7_12") (pintype "open_collector"))
      (node (ref "R86") (pin "1") (pinfunction "1_1") (pintype "passive"))
    )
    (net (code "96") (name "/LIGHT_DTA_2") (class "Default")
      (node (ref "IC5") (pin "13") (pinfunction "O6_13") (pintype "open_collector"))
      (node (ref "R88") (pin "1") (pinfunction "1_1") (pintype "passive"))
    )
    (net (code "97") (name "/LIGHT_DTA_3") (class "Default")
      (node (ref "IC5") (pin "14") (pinfunction "O5_14") (pintype "open_collector"))
      (node (ref "R90") (pin "1") (pinfunction "1_1") (pintype "passive"))
    )
    (net (code "98") (name "/LIGHT_DTA_4") (class "Default")
      (node (ref "IC5") (pin "15") (pinfunction "O4_15") (pintype "open_collector"))
      (node (ref "R92") (pin "1") (pinfunction "1_1") (pintype "passive"))
    )
    (net (code "99") (name "/LIGHT_DTA_5") (class "Default")
      (node (ref "IC5") (pin "16") (pinfunction "O3_16") (pintype "open_collector"))
      (node (ref "R94") (pin "1") (pinfunction "1_1") (pintype "passive"))
    )
    (net (code "100") (name "/LIGHT_DTA_6") (class "Default")
      (node (ref "IC5") (pin "17") (pinfunction "O2_17") (pintype "open_collector"))
      (node (ref "R96") (pin "1") (pinfunction "1_1") (pintype "passive"))
    )
    (net (code "101") (name "/LIGHT_DTA_7") (class "Default")
      (node (ref "IC5") (pin "18") (pinfunction "O1_18") (pintype "open_collector"))
      (node (ref "R98") (pin "1") (pinfunction "1_1") (pintype "passive"))
    )
    (net (code "102") (name "/LIGHT_R_0") (class "Default")
      (node (ref "LIGHT_ROW") (pin "P$2") (pinfunction "2_P$2") (pintype "bidirectional"))
      (node (ref "U28") (pin "D") (pinfunction "COLLECTOR_D") (pintype "bidirectional"))
    )
    (net (code "103") (name "/LIGHT_R_1") (class "Default")
      (node (ref "LIGHT_ROW") (pin "P$4") (pinfunction "4_P$4") (pintype "bidirectional"))
      (node (ref "U29") (pin "D") (pinfunction "COLLECTOR_D") (pintype "bidirectional"))
    )
    (net (code "104") (name "/LIGHT_R_2") (class "Default")
      (node (ref "LIGHT_ROW") (pin "P$5") (pinfunction "5_P$5") (pintype "bidirectional"))
      (node (ref "U30") (pin "D") (pinfunction "COLLECTOR_D") (pintype "bidirectional"))
    )
    (net (code "105") (name "/LIGHT_R_3") (class "Default")
      (node (ref "LIGHT_ROW") (pin "P$6") (pinfunction "6_P$6") (pintype "bidirectional"))
      (node (ref "U31") (pin "D") (pinfunction "COLLECTOR_D") (pintype "bidirectional"))
    )
    (net (code "106") (name "/LIGHT_R_4") (class "Default")
      (node (ref "LIGHT_ROW") (pin "P$7") (pinfunction "7_P$7") (pintype "bidirectional"))
      (node (ref "U32") (pin "D") (pinfunction "COLLECTOR_D") (pintype "bidirectional"))
    )
    (net (code "107") (name "/LIGHT_R_5") (class "Default")
      (node (ref "LIGHT_ROW") (pin "P$8") (pinfunction "8_P$8") (pintype "bidirectional"))
      (node (ref "U33") (pin "D") (pinfunction "COLLECTOR_D") (pintype "bidirectional"))
    )
    (net (code "108") (name "/LIGHT_R_6") (class "Default")
      (node (ref "LIGHT_ROW") (pin "P$9") (pinfunction "9_P$9") (pintype "bidirectional"))
      (node (ref "U34") (pin "D") (pinfunction "COLLECTOR_D") (pintype "bidirectional"))
    )
    (net (code "109") (name "/LIGHT_R_7") (class "Default")
      (node (ref "LIGHT_ROW") (pin "P$10") (pinfunction "10_P$10") (pintype "bidirectional"))
      (node (ref "U35") (pin "D") (pinfunction "COLLECTOR_D") (pintype "bidirectional"))
    )
    (net (code "110") (name "/L_FLIP") (class "Default")
      (node (ref "CABINET") (pin "P$12") (pinfunction "12_P$12") (pintype "bidirectional"))
      (node (ref "R46") (pin "1") (pinfunction "1_1") (pintype "passive"))
      (node (ref "U12") (pin "14") (pinfunction "D3_14") (pintype "bidirectional"))
    )
    (net (code "111") (name "/MENU") (class "Default")
      (node (ref "CABINET") (pin "P$8") (pinfunction "8_P$8") (pintype "bidirectional"))
      (node (ref "R47") (pin "1") (pinfunction "1_1") (pintype "passive"))
      (node (ref "U12") (pin "3") (pinfunction "D4_3") (pintype "bidirectional"))
    )
    (net (code "112") (name "/NEO_DATA") (class "Default")
      (node (ref "NEO_PIXEL") (pin "3") (pinfunction "3_3") (pintype "passive"))
      (node (ref "R24") (pin "2") (pinfunction "2_2") (pintype "passive"))
    )
    (net (code "113") (name "/P0") (class "Default")
      (node (ref "R20") (pin "2") (pinfunction "2_2") (pintype "passive"))
      (node (ref "SD0") (pin "7") (pinfunction "D0_7") (pintype "bidirectional"))
      (node (ref "U1") (pin "41") (pinfunction "P0_41") (pintype "bidirectional"))
    )
    (net (code "114") (name "/P1") (class "Default")
      (node (ref "R19") (pin "2") (pinfunction "2_2") (pintype "passive"))
      (node (ref "SD0") (pin "5") (pinfunction "SCLK_5") (pintype "bidirectional"))
      (node (ref "U1") (pin "42") (pinfunction "P1_42") (pintype "bidirectional"))
    )
    (net (code "115") (name "/P2") (class "Default")
      (node (ref "R18") (pin "2") (pinfunction "2_2") (pintype "passive"))
      (node (ref "SD0") (pin "2") (pinfunction "DI_2") (pintype "bidirectional"))
      (node (ref "U1") (pin "43") (pinfunction "P2_43") (pintype "bidirectional"))
    )
    (net (code "116") (name "/P3") (class "Default")
      (node (ref "R22") (pin "2") (pinfunction "2_2") (pintype "passive"))
      (node (ref "SD0") (pin "1") (pinfunction "CS_1") (pintype "bidirectional"))
      (node (ref "U1") (pin "44") (pinfunction "P3_44") (pintype "bidirectional"))
    )
    (net (code "117") (name "/P4") (class "Default")
      (node (ref "R24") (pin "1") (pinfunction "1_1") (pintype "passive"))
      (node (ref "U1") (pin "1") (pinfunction "P4_1") (pintype "bidirectional"))
    )
    (net (code "118") (name "/P5") (class "Default")
      (node (ref "U1") (pin "2") (pinfunction "P5_2") (pintype "bidirectional"))
    )
    (net (code "119") (name "/P6") (class "Default")
      (node (ref "U1") (pin "3") (pinfunction "P6_3") (pintype "bidirectional"))
    )
    (net (code "120") (name "/P7") (class "Default")
      (node (ref "U1") (pin "4") (pinfunction "P7_4") (pintype "bidirectional"))
    )
    (net (code "121") (name "/P8") (class "Default")
      (node (ref "DMD_CON") (pin "7") (pinfunction "7_7") (pintype "bidirectional"))
      (node (ref "U1") (pin "9") (pinfunction "P8_9") (pintype "bidirectional"))
    )
    (net (code "122") (name "/P9") (class "Default")
      (node (ref "U1") (pin "10") (pinfunction "P9_10") (pintype "bidirectional"))
    )
    (net (code "123") (name "/P10") (class "Default")
      (node (ref "U1") (pin "11") (pinfunction "P10_11") (pintype "bidirectional"))
    )
    (net (code "124") (name "/P11") (class "Default")
      (node (ref "U1") (pin "12") (pinfunction "P11_12") (pintype "bidirectional"))
    )
    (net (code "125") (name "/P12") (class "Default")
      (node (ref "U1") (pin "13") (pinfunction "P12_13") (pintype "bidirectional"))
    )
    (net (code "126") (name "/P13") (class "Default")
      (node (ref "U1") (pin "14") (pinfunction "P13_14") (pintype "bidirectional"))
    )
    (net (code "127") (name "/P14") (class "Default")
      (node (ref "R32") (pin "1") (pinfunction "1_1") (pintype "passive"))
      (node (ref "U1") (pin "15") (pinfunction "P14_15") (pintype "bidirectional"))
    )
    (net (code "128") (name "/P15") (class "Default")
      (node (ref "R34") (pin "1") (pinfunction "1_1") (pintype "passive"))
      (node (ref "U1") (pin "16") (pinfunction "P15_16") (pintype "bidirectional"))
    )
    (net (code "129") (name "/P16") (class "Default")
      (node (ref "DMD_CON") (pin "6") (pinfunction "6_6") (pintype "bidirectional"))
      (node (ref "U1") (pin "19") (pinfunction "P16_19") (pintype "bidirectional"))
    )
    (net (code "130") (name "/P17") (class "Default")
      (node (ref "DMD_CON") (pin "5") (pinfunction "5_5") (pintype "bidirectional"))
      (node (ref "U1") (pin "20") (pinfunction "P17_20") (pintype "bidirectional"))
    )
    (net (code "131") (name "/P18") (class "Default")
      (node (ref "DMD_CON") (pin "4") (pinfunction "4_4") (pintype "bidirectional"))
      (node (ref "U1") (pin "21") (pinfunction "P18_21") (pintype "bidirectional"))
    )
    (net (code "132") (name "/P19") (class "Default")
      (node (ref "DMD_CON") (pin "3") (pinfunction "3_3") (pintype "bidirectional"))
      (node (ref "U1") (pin "22") (pinfunction "P19_22") (pintype "bidirectional"))
    )
    (net (code "133") (name "/P20") (class "Default")
      (node (ref "DMD_CON") (pin "2") (pinfunction "2_2") (pintype "bidirectional"))
      (node (ref "U1") (pin "23") (pinfunction "P20_23") (pintype "bidirectional"))
    )
    (net (code "134") (name "/P21") (class "Default")
      (node (ref "DMD_CON") (pin "1") (pinfunction "1_1") (pintype "bidirectional"))
      (node (ref "U1") (pin "24") (pinfunction "P21_24") (pintype "bidirectional"))
    )
    (net (code "135") (name "/P22") (class "Default")
      (node (ref "U1") (pin "25") (pinfunction "P22_25") (pintype "bidirectional"))
    )
    (net (code "136") (name "/P23") (class "Default")
      (node (ref "U1") (pin "26") (pinfunction "P23_26") (pintype "bidirectional"))
    )
    (net (code "137") (name "/P27") (class "Default")
      (node (ref "PROP_ACT") (pin "ANODE") (pinfunction "ANODE_ANODE") (pintype "bidirectional"))
      (node (ref "U1") (pin "34") (pinfunction "P27_34") (pintype "bidirectional"))
    )
    (net (code "138") (name "/P32_MCLR") (class "Default")
      (node (ref "C1") (pin "2") (pinfunction "2_2") (pintype "passive"))
      (node (ref "D8") (pin "3") (pinfunction "D2_3") (pintype "bidirectional"))
      (node (ref "J11") (pin "1") (pinfunction "1_1") (pintype "passive"))
      (node (ref "R10") (pin "2") (pinfunction "2_2") (pintype "passive"))
      (node (ref "R12") (pin "2") (pinfunction "2_2") (pintype "passive"))
      (node (ref "R4") (pin "1") (pinfunction "1_1") (pintype "passive"))
      (node (ref "R8") (pin "2") (pinfunction "2_2") (pintype "passive"))
    )
    (net (code "139") (name "/PIC_ENABLE") (class "Default")
      (node (ref "IC2") (pin "1") (pinfunction "AERXERR/RG15_1") (pintype "bidirectional"))
      (node (ref "R133") (pin "1") (pinfunction "1_1") (pintype "passive"))
      (node (ref "U52") (pin "1") (pinfunction "~{1A}_1") (pintype "bidirectional"))
    )
    (net (code "140") (name "/PIC_LIGHT_C_0") (class "Default")
      (node (ref "IC2") (pin "25") (pinfunction "PGED1/AN0/CN2/RB0_25") (pintype "bidirectional"))
      (node (ref "IC5") (pin "8") (pinfunction "I8_8") (pintype "input"))
    )
    (net (code "141") (name "/PIC_LIGHT_C_1") (class "Default")
      (node (ref "IC2") (pin "24") (pinfunction "PGEC1/AN1/CN3/RB1_24") (pintype "bidirectional"))
      (node (ref "IC5") (pin "7") (pinfunction "I7_7") (pintype "input"))
    )
    (net (code "142") (name "/PIC_LIGHT_C_2") (class "Default")
      (node (ref "IC2") (pin "23") (pinfunction "AN2/C2IN-/CN4/RB2_23") (pintype "bidirectional"))
      (node (ref "IC5") (pin "6") (pinfunction "I6_6") (pintype "input"))
    )
    (net (code "143") (name "/PIC_LIGHT_C_3") (class "Default")
      (node (ref "IC2") (pin "22") (pinfunction "AN3/C2IN+/CN5/RB3_22") (pintype "bidirectional"))
      (node (ref "IC5") (pin "5") (pinfunction "I5_5") (pintype "input"))
    )
    (net (code "144") (name "/PIC_LIGHT_C_4") (class "Default")
      (node (ref "IC2") (pin "21") (pinfunction "AN4/C1IN-/CN6/RB4_21") (pintype "bidirectional"))
      (node (ref "IC5") (pin "4") (pinfunction "I4_4") (pintype "input"))
    )
    (net (code "145") (name "/PIC_LIGHT_C_5") (class "Default")
      (node (ref "IC2") (pin "20") (pinfunction "AN5/C1IN+/VBUSON/CN7/RB5_20") (pintype "bidirectional"))
      (node (ref "IC5") (pin "3") (pinfunction "I3_3") (pintype "input"))
    )
    (net (code "146") (name "/PIC_LIGHT_C_6") (class "Default")
      (node (ref "IC2") (pin "26") (pinfunction "PGEC2/AN6/OCFA/RB6_26") (pintype "bidirectional"))
      (node (ref "IC5") (pin "2") (pinfunction "I2_2") (pintype "input"))
      (node (ref "R14") (pin "1") (pinfunction "1_1") (pintype "passive"))
    )
    (net (code "147") (name "/PIC_LIGHT_C_7") (class "Default")
      (node (ref "IC2") (pin "27") (pinfunction "PGED2/AN7/RB7_27") (pintype "bidirectional"))
      (node (ref "IC5") (pin "1") (pinfunction "I1_1") (pintype "input"))
      (node (ref "R13") (pin "1") (pinfunction "1_1") (pintype "passive"))
    )
    (net (code "148") (name "/PIC_LIGHT_R_0") (class "Default")
      (node (ref "IC2") (pin "32") (pinfunction "AN8/C1OUT/RB8_32") (pintype "bidirectional"))
      (node (ref "R100") (pin "1") (pinfunction "1_1") (pintype "passive"))
    )
    (net (code "149") (name "/PIC_LIGHT_R_1") (class "Default")
      (node (ref "IC2") (pin "33") (pinfunction "AN9/C2OUT/RB9_33") (pintype "bidirectional"))
      (node (ref "R102") (pin "1") (pinfunction "1_1") (pintype "passive"))
    )
    (net (code "150") (name "/PIC_LIGHT_R_2") (class "Default")
      (node (ref "IC2") (pin "34") (pinfunction "AN10/CVREFOUT/PMA13/RB10_34") (pintype "bidirectional"))
      (node (ref "R104") (pin "1") (pinfunction "1_1") (pintype "passive"))
    )
    (net (code "151") (name "/PIC_LIGHT_R_3") (class "Default")
      (node (ref "IC2") (pin "35") (pinfunction "AN11/ERXERR/AETXERR/PMA12/RB11_35") (pintype "bidirectional"))
      (node (ref "R106") (pin "1") (pinfunction "1_1") (pintype "passive"))
    )
    (net (code "152") (name "/PIC_LIGHT_R_4") (class "Default")
      (node (ref "IC2") (pin "41") (pinfunction "AN12/ERXD0/AECRS/PMA11/RB12_41") (pintype "bidirectional"))
      (node (ref "R108") (pin "1") (pinfunction "1_1") (pintype "passive"))
    )
    (net (code "153") (name "/PIC_LIGHT_R_5") (class "Default")
      (node (ref "IC2") (pin "42") (pinfunction "AN13/ERXD1/AECOL/PMA10/RB13_42") (pintype "bidirectional"))
      (node (ref "R110") (pin "1") (pinfunction "1_1") (pintype "passive"))
    )
    (net (code "154") (name "/PIC_LIGHT_R_6") (class "Default")
      (node (ref "IC2") (pin "43") (pinfunction "AN14/ERXD2/AETXD3/PMALH/PMA1/RB14_43") (pintype "bidirectional"))
      (node (ref "R112") (pin "1") (pinfunction "1_1") (pintype "passive"))
    )
    (net (code "155") (name "/PIC_LIGHT_R_7") (class "Default")
      (node (ref "IC2") (pin "44") (pinfunction "OCFB/PMALL/PMA0/CN12/RB15_44") (pintype "bidirectional"))
      (node (ref "R114") (pin "1") (pinfunction "1_1") (pintype "passive"))
    )
    (net (code "156") (name "/PIC_SOL_0") (class "Default")
      (node (ref "IC2") (pin "7") (pinfunction "T3CK/AC2TX/RC2_7") (pintype "bidirectional"))
      (node (ref "R58") (pin "2") (pinfunction "2_2") (pintype "passive"))
      (node (ref "U14") (pin "2") (pinfunction "B1_2") (pintype "bidirectional"))
    )
    (net (code "157") (name "/PIC_SOL_1") (class "Default")
      (node (ref "IC2") (pin "8") (pinfunction "T4CK/AC2RX/RC3_8") (pintype "bidirectional"))
      (node (ref "R57") (pin "2") (pinfunction "2_2") (pintype "passive"))
      (node (ref "U14") (pin "5") (pinfunction "B2_5") (pintype "bidirectional"))
    )
    (net (code "158") (name "/PIC_SOL_2") (class "Default")
      (node (ref "IC2") (pin "3") (pinfunction "PMD5/RE5_3") (pintype "bidirectional"))
      (node (ref "R56") (pin "2") (pinfunction "2_2") (pintype "passive"))
      (node (ref "U14") (pin "10") (pinfunction "B3_10") (pintype "bidirectional"))
    )
    (net (code "159") (name "/PIC_SOL_3") (class "Default")
      (node (ref "IC2") (pin "51") (pinfunction "USBID/RF3_51") (pintype "bidirectional"))
      (node (ref "R55") (pin "2") (pinfunction "2_2") (pintype "passive"))
      (node (ref "U14") (pin "13") (pinfunction "B4_13") (pintype "bidirectional"))
    )
    (net (code "160") (name "/PIC_SOL_4") (class "Default")
      (node (ref "IC2") (pin "4") (pinfunction "PMD6/RE6_4") (pintype "bidirectional"))
      (node (ref "R54") (pin "2") (pinfunction "2_2") (pintype "passive"))
      (node (ref "U17") (pin "2") (pinfunction "B1_2") (pintype "bidirectional"))
    )
    (net (code "161") (name "/PIC_SOL_5") (class "Default")
      (node (ref "IC2") (pin "5") (pinfunction "PMD7/RE7_5") (pintype "bidirectional"))
      (node (ref "R53") (pin "2") (pinfunction "2_2") (pintype "passive"))
      (node (ref "U17") (pin "5") (pinfunction "B2_5") (pintype "bidirectional"))
    )
    (net (code "162") (name "/PIC_SOL_6") (class "Default")
      (node (ref "IC2") (pin "18") (pinfunction "AERXD0/INT1/RE8_18") (pintype "bidirectional"))
      (node (ref "R52") (pin "2") (pinfunction "2_2") (pintype "passive"))
      (node (ref "U17") (pin "10") (pinfunction "B3_10") (pintype "bidirectional"))
    )
    (net (code "163") (name "/PIC_SOL_7") (class "Default")
      (node (ref "IC2") (pin "74") (pinfunction "SOSCO/T1CK/CN0/RC14_74") (pintype "bidirectional"))
      (node (ref "R51") (pin "2") (pinfunction "2_2") (pintype "passive"))
      (node (ref "U17") (pin "13") (pinfunction "B4_13") (pintype "bidirectional"))
    )
    (net (code "164") (name "/PIC_SOL_8") (class "Default")
      (node (ref "IC2") (pin "19") (pinfunction "AERXD1/INT2/RE9_19") (pintype "bidirectional"))
      (node (ref "R66") (pin "2") (pinfunction "2_2") (pintype "passive"))
      (node (ref "U15") (pin "2") (pinfunction "B1_2") (pintype "bidirectional"))
    )
    (net (code "165") (name "/PIC_SOL_9") (class "Default")
      (node (ref "IC2") (pin "9") (pinfunction "T5CK/SDI1/RC4_9") (pintype "bidirectional"))
      (node (ref "R65") (pin "2") (pinfunction "2_2") (pintype "passive"))
      (node (ref "U15") (pin "5") (pinfunction "B2_5") (pintype "bidirectional"))
    )
    (net (code "166") (name "/PIC_SOL_10") (class "Default")
      (node (ref "IC2") (pin "58") (pinfunction "SCL2/RA2_58") (pintype "bidirectional"))
      (node (ref "R64") (pin "2") (pinfunction "2_2") (pintype "passive"))
      (node (ref "U15") (pin "10") (pinfunction "B3_10") (pintype "bidirectional"))
    )
    (net (code "167") (name "/PIC_SOL_11") (class "Default")
      (node (ref "IC2") (pin "17") (pinfunction "TMS/RA0_17") (pintype "bidirectional"))
      (node (ref "R63") (pin "2") (pinfunction "2_2") (pintype "passive"))
      (node (ref "U15") (pin "13") (pinfunction "B4_13") (pintype "bidirectional"))
    )
    (net (code "168") (name "/PIC_SOL_12") (class "Default")
      (node (ref "IC2") (pin "38") (pinfunction "TCK/RA1_38") (pintype "bidirectional"))
      (node (ref "R62") (pin "2") (pinfunction "2_2") (pintype "passive"))
      (node (ref "U18") (pin "2") (pinfunction "B1_2") (pintype "bidirectional"))
    )
    (net (code "169") (name "/PIC_SOL_13") (class "Default")
      (node (ref "IC2") (pin "60") (pinfunction "TDI/RA4_60") (pintype "bidirectional"))
      (node (ref "R61") (pin "2") (pinfunction "2_2") (pintype "passive"))
      (node (ref "U18") (pin "5") (pinfunction "B2_5") (pintype "bidirectional"))
    )
    (net (code "170") (name "/PIC_SOL_14") (class "Default")
      (node (ref "IC2") (pin "61") (pinfunction "TDO/RA5_61") (pintype "bidirectional"))
      (node (ref "R60") (pin "2") (pinfunction "2_2") (pintype "passive"))
      (node (ref "U18") (pin "10") (pinfunction "B3_10") (pintype "bidirectional"))
    )
    (net (code "171") (name "/PIC_SOL_15") (class "Default")
      (node (ref "IC2") (pin "73") (pinfunction "SOSCI/CN1/RC13_73") (pintype "bidirectional"))
      (node (ref "R59") (pin "2") (pinfunction "2_2") (pintype "passive"))
      (node (ref "U18") (pin "13") (pinfunction "B4_13") (pintype "bidirectional"))
    )
    (net (code "172") (name "/PIC_SOL_16") (class "Default")
      (node (ref "IC2") (pin "89") (pinfunction "C2TX/ETXERR/PMD9/RG1_89") (pintype "bidirectional"))
      (node (ref "R74") (pin "2") (pinfunction "2_2") (pintype "passive"))
      (node (ref "U16") (pin "2") (pinfunction "B1_2") (pintype "bidirectional"))
    )
    (net (code "173") (name "/PIC_SOL_17") (class "Default")
      (node (ref "IC2") (pin "90") (pinfunction "C2RX/PMD8/RG0_90") (pintype "bidirectional"))
      (node (ref "R73") (pin "2") (pinfunction "2_2") (pintype "passive"))
      (node (ref "U16") (pin "5") (pinfunction "B2_5") (pintype "bidirectional"))
    )
    (net (code "174") (name "/PIC_SOL_18") (class "Default")
      (node (ref "IC2") (pin "91") (pinfunction "TRCLK/RA6_91") (pintype "bidirectional"))
      (node (ref "R72") (pin "2") (pinfunction "2_2") (pintype "passive"))
      (node (ref "U16") (pin "10") (pinfunction "B3_10") (pintype "bidirectional"))
    )
    (net (code "175") (name "/PIC_SOL_19") (class "Default")
      (node (ref "IC2") (pin "92") (pinfunction "TRD3/RA7_92") (pintype "bidirectional"))
      (node (ref "R71") (pin "2") (pinfunction "2_2") (pintype "passive"))
      (node (ref "U16") (pin "13") (pinfunction "B4_13") (pintype "bidirectional"))
    )
    (net (code "176") (name "/PIC_SOL_20") (class "Default")
      (node (ref "IC2") (pin "95") (pinfunction "TRD2/RG14_95") (pintype "bidirectional"))
      (node (ref "R70") (pin "2") (pinfunction "2_2") (pintype "passive"))
      (node (ref "U19") (pin "2") (pinfunction "B1_2") (pintype "bidirectional"))
    )
    (net (code "177") (name "/PIC_SOL_21") (class "Default")
      (node (ref "IC2") (pin "96") (pinfunction "TRD1/RG12_96") (pintype "bidirectional"))
      (node (ref "R69") (pin "2") (pinfunction "2_2") (pintype "passive"))
      (node (ref "U19") (pin "5") (pinfunction "B2_5") (pintype "bidirectional"))
    )
    (net (code "178") (name "/PIC_SOL_22") (class "Default")
      (node (ref "IC2") (pin "97") (pinfunction "TRD0/RG13_97") (pintype "bidirectional"))
      (node (ref "R68") (pin "2") (pinfunction "2_2") (pintype "passive"))
      (node (ref "U19") (pin "10") (pinfunction "B3_10") (pintype "bidirectional"))
    )
    (net (code "179") (name "/PIC_SOL_23") (class "Default")
      (node (ref "IC2") (pin "28") (pinfunction "VREF-/CVREF-/AERXD2/PMA7/RA9_28") (pintype "bidirectional"))
      (node (ref "R67") (pin "2") (pinfunction "2_2") (pintype "passive"))
      (node (ref "U19") (pin "13") (pinfunction "B4_13") (pintype "bidirectional"))
    )
    (net (code "180") (name "/PIC_SW_C_0") (class "Default")
      (node (ref "IC2") (pin "68") (pinfunction "RTCC/EMDIO/AEMDIO/IC1/RD8_68") (pintype "bidirectional"))
      (node (ref "IC4") (pin "2") (pinfunction "A1_2") (pintype "input"))
    )
    (net (code "181") (name "/PIC_SW_C_1") (class "Default")
      (node (ref "IC2") (pin "69") (pinfunction "SS1/IC2/RD9_69") (pintype "bidirectional"))
      (node (ref "IC4") (pin "17") (pinfunction "A4_17") (pintype "input"))
    )
    (net (code "182") (name "/PIC_SW_C_2") (class "Default")
      (node (ref "IC2") (pin "70") (pinfunction "SCK1/IC3/PMCS2/PMA15/RD10_70") (pintype "bidirectional"))
      (node (ref "IC4") (pin "4") (pinfunction "A2_4") (pintype "input"))
    )
    (net (code "183") (name "/PIC_SW_C_3") (class "Default")
      (node (ref "IC2") (pin "71") (pinfunction "EMDC/AEMDC/IC4/PMCS1/PMA14/RD11_71") (pintype "bidirectional"))
      (node (ref "IC4") (pin "15") (pinfunction "A3_15") (pintype "input"))
    )
    (net (code "184") (name "/PIC_SW_C_4") (class "Default")
      (node (ref "IC2") (pin "79") (pinfunction "ETXD2/IC5/PMD12/RD12_79") (pintype "bidirectional"))
      (node (ref "IC4") (pin "6") (pinfunction "A3_6") (pintype "input"))
    )
    (net (code "185") (name "/PIC_SW_C_5") (class "Default")
      (node (ref "IC2") (pin "80") (pinfunction "ETXD3/PMD13/CN19/RD13_80") (pintype "bidirectional"))
      (node (ref "IC4") (pin "13") (pinfunction "A2_13") (pintype "input"))
    )
    (net (code "186") (name "/PIC_SW_C_6") (class "Default")
      (node (ref "IC2") (pin "47") (pinfunction "AETXD0/SS1A/U1BRX/U1ACTS/CN20/RD14_47") (pintype "bidirectional"))
      (node (ref "IC4") (pin "8") (pinfunction "A4_8") (pintype "input"))
    )
    (net (code "187") (name "/PIC_SW_C_7") (class "Default")
      (node (ref "IC2") (pin "48") (pinfunction "AETXD1/SCK1A/U1BTX/U1ARTS/CN21/RD15_48") (pintype "bidirectional"))
      (node (ref "IC4") (pin "11") (pinfunction "A1_11") (pintype "input"))
    )
    (net (code "188") (name "/PIC_SW_R_0") (class "Default")
      (node (ref "IC2") (pin "72") (pinfunction "SDO1/OC1/INT0/RD0_72") (pintype "bidirectional"))
      (node (ref "IC3") (pin "18") (pinfunction "Y1_18") (pintype "tri_state"))
    )
    (net (code "189") (name "/PIC_SW_R_1") (class "Default")
      (node (ref "IC2") (pin "76") (pinfunction "OC2/RD1_76") (pintype "bidirectional"))
      (node (ref "IC3") (pin "3") (pinfunction "Y4_3") (pintype "tri_state"))
    )
    (net (code "190") (name "/PIC_SW_R_2") (class "Default")
      (node (ref "IC2") (pin "77") (pinfunction "OC3/RD2_77") (pintype "bidirectional"))
      (node (ref "IC3") (pin "16") (pinfunction "Y2_16") (pintype "tri_state"))
    )
    (net (code "191") (name "/PIC_SW_R_3") (class "Default")
      (node (ref "IC2") (pin "78") (pinfunction "OC4/RD3_78") (pintype "bidirectional"))
      (node (ref "IC3") (pin "5") (pinfunction "Y3_5") (pintype "tri_state"))
    )
    (net (code "192") (name "/PIC_SW_R_4") (class "Default")
      (node (ref "IC2") (pin "81") (pinfunction "OC5/PMWR/CN13/RD4_81") (pintype "bidirectional"))
      (node (ref "IC3") (pin "14") (pinfunction "Y3_14") (pintype "tri_state"))
    )
    (net (code "193") (name "/PIC_SW_R_5") (class "Default")
      (node (ref "IC2") (pin "82") (pinfunction "PMRD/CN14/RD5_82") (pintype "bidirectional"))
      (node (ref "IC3") (pin "7") (pinfunction "Y2_7") (pintype "tri_state"))
    )
    (net (code "194") (name "/PIC_SW_R_6") (class "Default")
      (node (ref "IC2") (pin "83") (pinfunction "ETXEN/PMD14/CN15/RD6_83") (pintype "bidirectional"))
      (node (ref "IC3") (pin "12") (pinfunction "Y4_12") (pintype "tri_state"))
    )
    (net (code "195") (name "/PIC_SW_R_7") (class "Default")
      (node (ref "IC2") (pin "84") (pinfunction "ETXCLK/PMD15/CN16/RD7_84") (pintype "bidirectional"))
      (node (ref "IC3") (pin "9") (pinfunction "Y1_9") (pintype "tri_state"))
    )
    (net (code "196") (name "/RC1") (class "Default")
      (node (ref "IC2") (pin "6") (pinfunction "T2CK/RC1_6") (pintype "bidirectional"))
    )
    (net (code "197") (name "/RES") (class "Default")
      (node (ref "C17") (pin "2") (pinfunction "2_2") (pintype "passive"))
      (node (ref "R176") (pin "1") (pinfunction "1_1") (pintype "passive"))
      (node (ref "SW2") (pin "P$4") (pinfunction "P$4_P$4") (pintype "bidirectional"))
      (node (ref "U1") (pin "7") (pinfunction "RES'_7") (pintype "bidirectional"))
    )
    (net (code "198") (name "/RG6") (class "Default")
      (node (ref "IC2") (pin "10") (pinfunction "ECOL/SCK2A/U2BTXU2ARTS/PMA5/CN8/RG6_10") (pintype "bidirectional"))
    )
    (net (code "199") (name "/RG9") (class "Default")
      (node (ref "IC2") (pin "14") (pinfunction "SS2A/U2BRX/U2ACTS/PMA2/CN11/RG9_14") (pintype "bidirectional"))
      (node (ref "R137") (pin "1") (pinfunction "1_1") (pintype "passive"))
      (node (ref "SW3") (pin "P$4") (pinfunction "P$4_P$4") (pintype "bidirectional"))
    )
    (net (code "200") (name "/RGB_BOUT_L") (class "Default")
      (node (ref "RGB_0") (pin "D") (pinfunction "DRAIN_D") (pintype "bidirectional"))
      (node (ref "RGB_CONN") (pin "3") (pinfunction "3_3") (pintype "bidirectional"))
    )
    (net (code "201") (name "/RGB_BOUT_R") (class "Default")
      (node (ref "RGB_3") (pin "D") (pinfunction "DRAIN_D") (pintype "bidirectional"))
      (node (ref "RGB_CONN") (pin "6") (pinfunction "6_6") (pintype "bidirectional"))
    )
    (net (code "202") (name "/RGB_CLK") (class "Default")
      (node (ref "IC2") (pin "98") (pinfunction "PMD2/RE2_98") (pintype "bidirectional"))
      (node (ref "U38") (pin "1") (pinfunction "CLI_1") (pintype "bidirectional"))
    )
    (net (code "203") (name "/RGB_CLK_1") (class "Default")
      (node (ref "U36") (pin "1") (pinfunction "CLI_1") (pintype "bidirectional"))
      (node (ref "U38") (pin "13") (pinfunction "CKO_13") (pintype "bidirectional"))
    )
    (net (code "204") (name "/RGB_CLK_OUT") (class "Default")
      (node (ref "AUX_PORT") (pin "P$9") (pinfunction "9_P$9") (pintype "bidirectional"))
      (node (ref "U36") (pin "13") (pinfunction "CKO_13") (pintype "bidirectional"))
    )
    (net (code "205") (name "/RGB_DATA") (class "Default")
      (node (ref "IC2") (pin "94") (pinfunction "PMD1/RE1_94") (pintype "bidirectional"))
      (node (ref "U38") (pin "2") (pinfunction "SDI_2") (pintype "bidirectional"))
    )
    (net (code "206") (name "/RGB_DATA_1") (class "Default")
      (node (ref "U36") (pin "2") (pinfunction "SDI_2") (pintype "bidirectional"))
      (node (ref "U38") (pin "12") (pinfunction "SDO_12") (pintype "bidirectional"))
    )
    (net (code "207") (name "/RGB_DATA_OUT") (class "Default")
      (node (ref "AUX_PORT") (pin "P$8") (pinfunction "8_P$8") (pintype "bidirectional"))
      (node (ref "U36") (pin "12") (pinfunction "SDO_12") (pintype "bidirectional"))
    )
    (net (code "208") (name "/RGB_GOUT_L") (class "Default")
      (node (ref "RGB_1") (pin "D") (pinfunction "DRAIN_D") (pintype "bidirectional"))
      (node (ref "RGB_CONN") (pin "4") (pinfunction "4_4") (pintype "bidirectional"))
    )
    (net (code "209") (name "/RGB_GOUT_R") (class "Default")
      (node (ref "RGB_4") (pin "D") (pinfunction "DRAIN_D") (pintype "bidirectional"))
      (node (ref "RGB_CONN") (pin "7") (pinfunction "7_7") (pintype "bidirectional"))
    )
    (net (code "210") (name "/RGB_ROUT_L") (class "Default")
      (node (ref "RGB_2") (pin "D") (pinfunction "DRAIN_D") (pintype "bidirectional"))
      (node (ref "RGB_CONN") (pin "5") (pinfunction "5_5") (pintype "bidirectional"))
    )
    (net (code "211") (name "/RGB_ROUT_R") (class "Default")
      (node (ref "RGB_5") (pin "D") (pinfunction "DRAIN_D") (pintype "bidirectional"))
      (node (ref "RGB_CONN") (pin "8") (pinfunction "8_8") (pintype "bidirectional"))
    )
    (net (code "212") (name "/RTS") (class "Default")
      (node (ref "C17") (pin "1") (pinfunction "1_1") (pintype "passive"))
      (node (ref "U2") (pin "2") (pinfunction "RTS#_2") (pintype "bidirectional"))
    )
    (net (code "213") (name "/RXLED") (class "Default")
      (node (ref "R6") (pin "1") (pinfunction "1_1") (pintype "passive"))
      (node (ref "U2") (pin "14") (pinfunction "CBUS1_14") (pintype "bidirectional"))
    )
    (net (code "214") (name "/RX_PIC32") (class "Default")
      (node (ref "BT_TX") (pin "2") (pinfunction "2_2") (pintype "passive"))
      (node (ref "IC2") (pin "52") (pinfunction "SDA1A/SDI1A/U1ARX/RF2_52") (pintype "bidirectional"))
      (node (ref "R2") (pin "2") (pinfunction "2_2") (pintype "passive"))
    )
    (net (code "215") (name "/RX_PROP") (class "Default")
      (node (ref "U1") (pin "37") (pinfunction "P30_37") (pintype "bidirectional"))
      (node (ref "U2") (pin "4") (pinfunction "RXD_4") (pintype "bidirectional"))
    )
    (net (code "216") (name "/R_FLIP") (class "Default")
      (node (ref "CABINET") (pin "P$11") (pinfunction "11_P$11") (pintype "bidirectional"))
      (node (ref "R45") (pin "1") (pinfunction "1_1") (pintype "passive"))
      (node (ref "U12") (pin "13") (pinfunction "D2_13") (pintype "bidirectional"))
    )
    (net (code "217") (name "/SCL_PROP") (class "Default")
      (node (ref "R16") (pin "1") (pinfunction "1_1") (pintype "passive"))
      (node (ref "U1") (pin "35") (pinfunction "P28_35") (pintype "bidirectional"))
      (node (ref "U4") (pin "6") (pinfunction "SCL_6") (pintype "bidirectional"))
    )
    (net (code "218") (name "/SDA_PROP") (class "Default")
      (node (ref "R17") (pin "1") (pinfunction "1_1") (pintype "passive"))
      (node (ref "U1") (pin "36") (pinfunction "P29_36") (pintype "bidirectional"))
      (node (ref "U4") (pin "5") (pinfunction "SDA_5") (pintype "bidirectional"))
    )
    (net (code "219") (name "/SOL_0") (class "Default")
      (node (ref "SOL_0") (pin "G") (pinfunction "GATE_G") (pintype "bidirectional"))
      (node (ref "U14") (pin "3") (pinfunction "Y1_3") (pintype "bidirectional"))
    )
    (net (code "220") (name "/SOL_1") (class "Default")
      (node (ref "SOL_1") (pin "G") (pinfunction "GATE_G") (pintype "bidirectional"))
      (node (ref "U14") (pin "6") (pinfunction "Y2_6") (pintype "bidirectional"))
    )
    (net (code "221") (name "/SOL_2") (class "Default")
      (node (ref "SOL_2") (pin "G") (pinfunction "GATE_G") (pintype "bidirectional"))
      (node (ref "U14") (pin "8") (pinfunction "Y3_8") (pintype "bidirectional"))
    )
    (net (code "222") (name "/SOL_3") (class "Default")
      (node (ref "SOL_3") (pin "G") (pinfunction "GATE_G") (pintype "bidirectional"))
      (node (ref "U14") (pin "11") (pinfunction "Y4_11") (pintype "bidirectional"))
    )
    (net (code "223") (name "/SOL_4") (class "Default")
      (node (ref "SOL_4") (pin "G") (pinfunction "GATE_G") (pintype "bidirectional"))
      (node (ref "U17") (pin "3") (pinfunction "Y1_3") (pintype "bidirectional"))
    )
    (net (code "224") (name "/SOL_5") (class "Default")
      (node (ref "SOL_5") (pin "G") (pinfunction "GATE_G") (pintype "bidirectional"))
      (node (ref "U17") (pin "6") (pinfunction "Y2_6") (pintype "bidirectional"))
    )
    (net (code "225") (name "/SOL_6") (class "Default")
      (node (ref "SOL_6") (pin "G") (pinfunction "GATE_G") (pintype "bidirectional"))
      (node (ref "U17") (pin "8") (pinfunction "Y3_8") (pintype "bidirectional"))
    )
    (net (code "226") (name "/SOL_7") (class "Default")
      (node (ref "SOL_7") (pin "G") (pinfunction "GATE_G") (pintype "bidirectional"))
      (node (ref "U17") (pin "11") (pinfunction "Y4_11") (pintype "bidirectional"))
    )
    (net (code "227") (name "/SOL_8") (class "Default")
      (node (ref "SOL_8") (pin "G") (pinfunction "GATE_G") (pintype "bidirectional"))
      (node (ref "U15") (pin "3") (pinfunction "Y1_3") (pintype "bidirectional"))
    )
    (net (code "228") (name "/SOL_9") (class "Default")
      (node (ref "SOL_9") (pin "G") (pinfunction "GATE_G") (pintype "bidirectional"))
      (node (ref "U15") (pin "6") (pinfunction "Y2_6") (pintype "bidirectional"))
    )
    (net (code "229") (name "/SOL_10") (class "Default")
      (node (ref "SOL_10") (pin "G") (pinfunction "GATE_G") (pintype "bidirectional"))
      (node (ref "U15") (pin "8") (pinfunction "Y3_8") (pintype "bidirectional"))
    )
    (net (code "230") (name "/SOL_11") (class "Default")
      (node (ref "SOL_11") (pin "G") (pinfunction "GATE_G") (pintype "bidirectional"))
      (node (ref "U15") (pin "11") (pinfunction "Y4_11") (pintype "bidirectional"))
    )
    (net (code "231") (name "/SOL_12") (class "Default")
      (node (ref "SOL_12") (pin "G") (pinfunction "GATE_G") (pintype "bidirectional"))
      (node (ref "U18") (pin "3") (pinfunction "Y1_3") (pintype "bidirectional"))
    )
    (net (code "232") (name "/SOL_13") (class "Default")
      (node (ref "SOL_13") (pin "G") (pinfunction "GATE_G") (pintype "bidirectional"))
      (node (ref "U18") (pin "6") (pinfunction "Y2_6") (pintype "bidirectional"))
    )
    (net (code "233") (name "/SOL_14") (class "Default")
      (node (ref "SOL_14") (pin "G") (pinfunction "GATE_G") (pintype "bidirectional"))
      (node (ref "U18") (pin "8") (pinfunction "Y3_8") (pintype "bidirectional"))
    )
    (net (code "234") (name "/SOL_15") (class "Default")
      (node (ref "SOL_15") (pin "G") (pinfunction "GATE_G") (pintype "bidirectional"))
      (node (ref "U18") (pin "11") (pinfunction "Y4_11") (pintype "bidirectional"))
    )
    (net (code "235") (name "/SOL_16") (class "Default")
      (node (ref "SOL_16") (pin "G") (pinfunction "GATE_G") (pintype "bidirectional"))
      (node (ref "U16") (pin "3") (pinfunction "Y1_3") (pintype "bidirectional"))
    )
    (net (code "236") (name "/SOL_17") (class "Default")
      (node (ref "SOL_17") (pin "G") (pinfunction "GATE_G") (pintype "bidirectional"))
      (node (ref "U16") (pin "6") (pinfunction "Y2_6") (pintype "bidirectional"))
    )
    (net (code "237") (name "/SOL_18") (class "Default")
      (node (ref "SOL_18") (pin "G") (pinfunction "GATE_G") (pintype "bidirectional"))
      (node (ref "U16") (pin "8") (pinfunction "Y3_8") (pintype "bidirectional"))
    )
    (net (code "238") (name "/SOL_19") (class "Default")
      (node (ref "SOL_19") (pin "G") (pinfunction "GATE_G") (pintype "bidirectional"))
      (node (ref "U16") (pin "11") (pinfunction "Y4_11") (pintype "bidirectional"))
    )
    (net (code "239") (name "/SOL_20") (class "Default")
      (node (ref "SOL_20") (pin "G") (pinfunction "GATE_G") (pintype "bidirectional"))
      (node (ref "U19") (pin "3") (pinfunction "Y1_3") (pintype "bidirectional"))
    )
    (net (code "240") (name "/SOL_21") (class "Default")
      (node (ref "SOL_21") (pin "G") (pinfunction "GATE_G") (pintype "bidirectional"))
      (node (ref "U19") (pin "6") (pinfunction "Y2_6") (pintype "bidirectional"))
    )
    (net (code "241") (name "/SOL_22") (class "Default")
      (node (ref "SOL_22") (pin "G") (pinfunction "GATE_G") (pintype "bidirectional"))
      (node (ref "U19") (pin "8") (pinfunction "Y3_8") (pintype "bidirectional"))
    )
    (net (code "242") (name "/SOL_23") (class "Default")
      (node (ref "SOL_23") (pin "G") (pinfunction "GATE_G") (pintype "bidirectional"))
      (node (ref "U19") (pin "11") (pinfunction "Y4_11") (pintype "bidirectional"))
    )
    (net (code "243") (name "/SOL_GND") (class "Default")
      (node (ref "R136") (pin "2") (pinfunction "2_2") (pintype "passive"))
      (node (ref "SOL_0") (pin "S") (pinfunction "SOURCE_S") (pintype "bidirectional"))
      (node (ref "SOL_1") (pin "S") (pinfunction "SOURCE_S") (pintype "bidirectional"))
      (node (ref "SOL_10") (pin "S") (pinfunction "SOURCE_S") (pintype "bidirectional"))
      (node (ref "SOL_11") (pin "S") (pinfunction "SOURCE_S") (pintype "bidirectional"))
      (node (ref "SOL_12") (pin "S") (pinfunction "SOURCE_S") (pintype "bidirectional"))
      (node (ref "SOL_13") (pin "S") (pinfunction "SOURCE_S") (pintype "bidirectional"))
      (node (ref "SOL_14") (pin "S") (pinfunction "SOURCE_S") (pintype "bidirectional"))
      (node (ref "SOL_15") (pin "S") (pinfunction "SOURCE_S") (pintype "bidirectional"))
      (node (ref "SOL_16") (pin "S") (pinfunction "SOURCE_S") (pintype "bidirectional"))
      (node (ref "SOL_17") (pin "S") (pinfunction "SOURCE_S") (pintype "bidirectional"))
      (node (ref "SOL_18") (pin "S") (pinfunction "SOURCE_S") (pintype "bidirectional"))
      (node (ref "SOL_19") (pin "S") (pinfunction "SOURCE_S") (pintype "bidirectional"))
      (node (ref "SOL_2") (pin "S") (pinfunction "SOURCE_S") (pintype "bidirectional"))
      (node (ref "SOL_20") (pin "S") (pinfunction "SOURCE_S") (pintype "bidirectional"))
      (node (ref "SOL_21") (pin "S") (pinfunction "SOURCE_S") (pintype "bidirectional"))
      (node (ref "SOL_22") (pin "S") (pinfunction "SOURCE_S") (pintype "bidirectional"))
      (node (ref "SOL_23") (pin "S") (pinfunction "SOURCE_S") (pintype "bidirectional"))
      (node (ref "SOL_3") (pin "S") (pinfunction "SOURCE_S") (pintype "bidirectional"))
      (node (ref "SOL_4") (pin "S") (pinfunction "SOURCE_S") (pintype "bidirectional"))
      (node (ref "SOL_5") (pin "S") (pinfunction "SOURCE_S") (pintype "bidirectional"))
      (node (ref "SOL_6") (pin "S") (pinfunction "SOURCE_S") (pintype "bidirectional"))
      (node (ref "SOL_7") (pin "S") (pinfunction "SOURCE_S") (pintype "bidirectional"))
      (node (ref "SOL_8") (pin "S") (pinfunction "SOURCE_S") (pintype "bidirectional"))
      (node (ref "SOL_9") (pin "S") (pinfunction "SOURCE_S") (pintype "bidirectional"))
      (node (ref "SOL_PWR") (pin "1") (pinfunction "1_1") (pintype "passive"))
      (node (ref "SOL_PWR") (pin "2") (pinfunction "2_2") (pintype "passive"))
    )
    (net (code "244") (name "/SOL_PWR_0") (class "Default")
      (node (ref "KNOCKER") (pin "3") (pinfunction "3_3") (pintype "passive"))
      (node (ref "SOL_0") (pin "D") (pinfunction "DRAIN_D") (pintype "bidirectional"))
      (node (ref "SOL_BANK_0") (pin "P$2") (pinfunction "2_P$2") (pintype "bidirectional"))
    )
    (net (code "245") (name "/SOL_PWR_1") (class "Default")
      (node (ref "SOL_1") (pin "D") (pinfunction "DRAIN_D") (pintype "bidirectional"))
      (node (ref "SOL_BANK_0") (pin "P$3") (pinfunction "3_P$3") (pintype "bidirectional"))
    )
    (net (code "246") (name "/SOL_PWR_2") (class "Default")
      (node (ref "SOL_2") (pin "D") (pinfunction "DRAIN_D") (pintype "bidirectional"))
      (node (ref "SOL_BANK_0") (pin "P$4") (pinfunction "4_P$4") (pintype "bidirectional"))
    )
    (net (code "247") (name "/SOL_PWR_3") (class "Default")
      (node (ref "SOL_3") (pin "D") (pinfunction "DRAIN_D") (pintype "bidirectional"))
      (node (ref "SOL_BANK_0") (pin "P$5") (pinfunction "5_P$5") (pintype "bidirectional"))
    )
    (net (code "248") (name "/SOL_PWR_4") (class "Default")
      (node (ref "SOL_4") (pin "D") (pinfunction "DRAIN_D") (pintype "bidirectional"))
      (node (ref "SOL_BANK_0") (pin "P$7") (pinfunction "7_P$7") (pintype "bidirectional"))
    )
    (net (code "249") (name "/SOL_PWR_5") (class "Default")
      (node (ref "SOL_5") (pin "D") (pinfunction "DRAIN_D") (pintype "bidirectional"))
      (node (ref "SOL_BANK_0") (pin "P$8") (pinfunction "8_P$8") (pintype "bidirectional"))
    )
    (net (code "250") (name "/SOL_PWR_6") (class "Default")
      (node (ref "SOL_6") (pin "D") (pinfunction "DRAIN_D") (pintype "bidirectional"))
      (node (ref "SOL_BANK_0") (pin "P$9") (pinfunction "9_P$9") (pintype "bidirectional"))
    )
    (net (code "251") (name "/SOL_PWR_7") (class "Default")
      (node (ref "SOL_7") (pin "D") (pinfunction "DRAIN_D") (pintype "bidirectional"))
      (node (ref "SOL_BANK_0") (pin "P$10") (pinfunction "10_P$10") (pintype "bidirectional"))
    )
    (net (code "252") (name "/SOL_PWR_8") (class "Default")
      (node (ref "SOL_8") (pin "D") (pinfunction "DRAIN_D") (pintype "bidirectional"))
      (node (ref "SOL_BANK_1") (pin "P$2") (pinfunction "2_P$2") (pintype "bidirectional"))
    )
    (net (code "253") (name "/SOL_PWR_9") (class "Default")
      (node (ref "SOL_9") (pin "D") (pinfunction "DRAIN_D") (pintype "bidirectional"))
      (node (ref "SOL_BANK_1") (pin "P$3") (pinfunction "3_P$3") (pintype "bidirectional"))
    )
    (net (code "254") (name "/SOL_PWR_10") (class "Default")
      (node (ref "SOL_10") (pin "D") (pinfunction "DRAIN_D") (pintype "bidirectional"))
      (node (ref "SOL_BANK_1") (pin "P$4") (pinfunction "4_P$4") (pintype "bidirectional"))
    )
    (net (code "255") (name "/SOL_PWR_11") (class "Default")
      (node (ref "SOL_11") (pin "D") (pinfunction "DRAIN_D") (pintype "bidirectional"))
      (node (ref "SOL_BANK_1") (pin "P$5") (pinfunction "5_P$5") (pintype "bidirectional"))
    )
    (net (code "256") (name "/SOL_PWR_12") (class "Default")
      (node (ref "SOL_12") (pin "D") (pinfunction "DRAIN_D") (pintype "bidirectional"))
      (node (ref "SOL_BANK_1") (pin "P$6") (pinfunction "6_P$6") (pintype "bidirectional"))
    )
    (net (code "257") (name "/SOL_PWR_13") (class "Default")
      (node (ref "SOL_13") (pin "D") (pinfunction "DRAIN_D") (pintype "bidirectional"))
      (node (ref "SOL_BANK_1") (pin "P$8") (pinfunction "8_P$8") (pintype "bidirectional"))
    )
    (net (code "258") (name "/SOL_PWR_14") (class "Default")
      (node (ref "SOL_14") (pin "D") (pinfunction "DRAIN_D") (pintype "bidirectional"))
      (node (ref "SOL_BANK_1") (pin "P$9") (pinfunction "9_P$9") (pintype "bidirectional"))
    )
    (net (code "259") (name "/SOL_PWR_15") (class "Default")
      (node (ref "SOL_15") (pin "D") (pinfunction "DRAIN_D") (pintype "bidirectional"))
      (node (ref "SOL_BANK_1") (pin "P$10") (pinfunction "10_P$10") (pintype "bidirectional"))
    )
    (net (code "260") (name "/SOL_PWR_16") (class "Default")
      (node (ref "SOL_16") (pin "D") (pinfunction "DRAIN_D") (pintype "bidirectional"))
      (node (ref "SOL_BANK_2") (pin "P$2") (pinfunction "2_P$2") (pintype "bidirectional"))
    )
    (net (code "261") (name "/SOL_PWR_17") (class "Default")
      (node (ref "SOL_17") (pin "D") (pinfunction "DRAIN_D") (pintype "bidirectional"))
      (node (ref "SOL_BANK_2") (pin "P$3") (pinfunction "3_P$3") (pintype "bidirectional"))
    )
    (net (code "262") (name "/SOL_PWR_18") (class "Default")
      (node (ref "SOL_18") (pin "D") (pinfunction "DRAIN_D") (pintype "bidirectional"))
      (node (ref "SOL_BANK_2") (pin "P$4") (pinfunction "4_P$4") (pintype "bidirectional"))
    )
    (net (code "263") (name "/SOL_PWR_19") (class "Default")
      (node (ref "SOL_19") (pin "D") (pinfunction "DRAIN_D") (pintype "bidirectional"))
      (node (ref "SOL_BANK_2") (pin "P$5") (pinfunction "5_P$5") (pintype "bidirectional"))
    )
    (net (code "264") (name "/SOL_PWR_20") (class "Default")
      (node (ref "SOL_20") (pin "D") (pinfunction "DRAIN_D") (pintype "bidirectional"))
      (node (ref "SOL_BANK_2") (pin "P$6") (pinfunction "6_P$6") (pintype "bidirectional"))
    )
    (net (code "265") (name "/SOL_PWR_21") (class "Default")
      (node (ref "SOL_21") (pin "D") (pinfunction "DRAIN_D") (pintype "bidirectional"))
      (node (ref "SOL_BANK_2") (pin "P$7") (pinfunction "7_P$7") (pintype "bidirectional"))
    )
    (net (code "266") (name "/SOL_PWR_22") (class "Default")
      (node (ref "SOL_22") (pin "D") (pinfunction "DRAIN_D") (pintype "bidirectional"))
      (node (ref "SOL_BANK_2") (pin "P$9") (pinfunction "9_P$9") (pintype "bidirectional"))
    )
    (net (code "267") (name "/SOL_PWR_23") (class "Default")
      (node (ref "SOL_23") (pin "D") (pinfunction "DRAIN_D") (pintype "bidirectional"))
      (node (ref "SOL_BANK_2") (pin "P$10") (pinfunction "10_P$10") (pintype "bidirectional"))
    )
    (net (code "268") (name "/ST_BU") (class "Default")
      (node (ref "CABINET") (pin "P$4") (pinfunction "4_P$4") (pintype "bidirectional"))
      (node (ref "R38") (pin "1") (pinfunction "1_1") (pintype "passive"))
      (node (ref "U11") (pin "14") (pinfunction "D3_14") (pintype "bidirectional"))
    )
    (net (code "269") (name "/ST_LI") (class "Default")
      (node (ref "CABINET") (pin "P$3") (pinfunction "3_P$3") (pintype "bidirectional"))
      (node (ref "U37") (pin "D") (pinfunction "COLLECTOR_D") (pintype "bidirectional"))
    )
    (net (code "270") (name "/ST_LI_GATE") (class "Default")
      (node (ref "IC2") (pin "59") (pinfunction "SDA2/RA3_59") (pintype "bidirectional"))
      (node (ref "R116") (pin "2") (pinfunction "2_2") (pintype "passive"))
    )
    (net (code "271") (name "/SW_C_0") (class "Default")
      (node (ref "IC4") (pin "18") (pinfunction "Y1_18") (pintype "tri_state"))
      (node (ref "SW_COL") (pin "P$10") (pinfunction "10_P$10") (pintype "bidirectional"))
    )
    (net (code "272") (name "/SW_C_1") (class "Default")
      (node (ref "IC4") (pin "3") (pinfunction "Y4_3") (pintype "tri_state"))
      (node (ref "SW_COL") (pin "P$9") (pinfunction "9_P$9") (pintype "bidirectional"))
    )
    (net (code "273") (name "/SW_C_2") (class "Default")
      (node (ref "IC4") (pin "16") (pinfunction "Y2_16") (pintype "tri_state"))
      (node (ref "SW_COL") (pin "P$8") (pinfunction "8_P$8") (pintype "bidirectional"))
    )
    (net (code "274") (name "/SW_C_3") (class "Default")
      (node (ref "IC4") (pin "5") (pinfunction "Y3_5") (pintype "tri_state"))
      (node (ref "SW_COL") (pin "P$7") (pinfunction "7_P$7") (pintype "bidirectional"))
    )
    (net (code "275") (name "/SW_C_4") (class "Default")
      (node (ref "IC4") (pin "14") (pinfunction "Y3_14") (pintype "tri_state"))
      (node (ref "SW_COL") (pin "P$6") (pinfunction "6_P$6") (pintype "bidirectional"))
    )
    (net (code "276") (name "/SW_C_5") (class "Default")
      (node (ref "IC4") (pin "7") (pinfunction "Y2_7") (pintype "tri_state"))
      (node (ref "SW_COL") (pin "P$4") (pinfunction "4_P$4") (pintype "bidirectional"))
    )
    (net (code "277") (name "/SW_C_6") (class "Default")
      (node (ref "IC4") (pin "12") (pinfunction "Y4_12") (pintype "tri_state"))
      (node (ref "SW_COL") (pin "P$3") (pinfunction "3_P$3") (pintype "bidirectional"))
    )
    (net (code "278") (name "/SW_C_7") (class "Default")
      (node (ref "IC4") (pin "9") (pinfunction "Y1_9") (pintype "tri_state"))
      (node (ref "SW_COL") (pin "P$2") (pinfunction "2_P$2") (pintype "bidirectional"))
    )
    (net (code "279") (name "/SW_R_0") (class "Default")
      (node (ref "IC3") (pin "2") (pinfunction "A1_2") (pintype "input"))
      (node (ref "R82") (pin "1") (pinfunction "1_1") (pintype "passive"))
      (node (ref "SW_ROW") (pin "P$10") (pinfunction "10_P$10") (pintype "bidirectional"))
    )
    (net (code "280") (name "/SW_R_1") (class "Default")
      (node (ref "IC3") (pin "17") (pinfunction "A4_17") (pintype "input"))
      (node (ref "R81") (pin "1") (pinfunction "1_1") (pintype "passive"))
      (node (ref "SW_ROW") (pin "P$9") (pinfunction "9_P$9") (pintype "bidirectional"))
    )
    (net (code "281") (name "/SW_R_2") (class "Default")
      (node (ref "IC3") (pin "4") (pinfunction "A2_4") (pintype "input"))
      (node (ref "R80") (pin "1") (pinfunction "1_1") (pintype "passive"))
      (node (ref "SW_ROW") (pin "P$8") (pinfunction "8_P$8") (pintype "bidirectional"))
    )
    (net (code "282") (name "/SW_R_3") (class "Default")
      (node (ref "IC3") (pin "15") (pinfunction "A3_15") (pintype "input"))
      (node (ref "R79") (pin "1") (pinfunction "1_1") (pintype "passive"))
      (node (ref "SW_ROW") (pin "P$7") (pinfunction "7_P$7") (pintype "bidirectional"))
    )
    (net (code "283") (name "/SW_R_4") (class "Default")
      (node (ref "IC3") (pin "6") (pinfunction "A3_6") (pintype "input"))
      (node (ref "R78") (pin "2") (pinfunction "2_2") (pintype "passive"))
      (node (ref "SW_ROW") (pin "P$6") (pinfunction "6_P$6") (pintype "bidirectional"))
    )
    (net (code "284") (name "/SW_R_5") (class "Default")
      (node (ref "IC3") (pin "13") (pinfunction "A2_13") (pintype "input"))
      (node (ref "R77") (pin "2") (pinfunction "2_2") (pintype "passive"))
      (node (ref "SW_ROW") (pin "P$5") (pinfunction "5_P$5") (pintype "bidirectional"))
    )
    (net (code "285") (name "/SW_R_6") (class "Default")
      (node (ref "IC3") (pin "8") (pinfunction "A4_8") (pintype "input"))
      (node (ref "R76") (pin "2") (pinfunction "2_2") (pintype "passive"))
      (node (ref "SW_ROW") (pin "P$3") (pinfunction "3_P$3") (pintype "bidirectional"))
    )
    (net (code "286") (name "/SW_R_7") (class "Default")
      (node (ref "IC3") (pin "11") (pinfunction "A1_11") (pintype "input"))
      (node (ref "R75") (pin "2") (pinfunction "2_2") (pintype "passive"))
      (node (ref "SW_ROW") (pin "P$2") (pinfunction "2_P$2") (pintype "bidirectional"))
    )
    (net (code "287") (name "/S_L") (class "Default")
      (node (ref "J6") (pin "5") (pinfunction "T_5") (pintype "bidirectional"))
      (node (ref "R32") (pin "2") (pinfunction "2_2") (pintype "passive"))
    )
    (net (code "288") (name "/S_R") (class "Default")
      (node (ref "J6") (pin "2") (pinfunction "R_2") (pintype "bidirectional"))
      (node (ref "R34") (pin "2") (pinfunction "2_2") (pintype "passive"))
    )
    (net (code "289") (name "/TILT") (class "Default")
      (node (ref "CABINET") (pin "P$5") (pinfunction "5_P$5") (pintype "bidirectional"))
      (node (ref "R50") (pin "1") (pinfunction "1_1") (pintype "passive"))
      (node (ref "U12") (pin "6") (pinfunction "D7_6") (pintype "bidirectional"))
    )
    (net (code "290") (name "/TXLED") (class "Default")
      (node (ref "R15") (pin "1") (pinfunction "1_1") (pintype "passive"))
      (node (ref "U2") (pin "7") (pinfunction "CBUS2_7") (pintype "bidirectional"))
    )
    (net (code "291") (name "/TX_PIC32") (class "Default")
      (node (ref "BT_RX") (pin "2") (pinfunction "2_2") (pintype "passive"))
      (node (ref "IC2") (pin "53") (pinfunction "SCL1A/SDO1A/U1ATX/RF8_53") (pintype "bidirectional"))
      (node (ref "R1") (pin "2") (pinfunction "2_2") (pintype "passive"))
    )
    (net (code "292") (name "/TX_PROP") (class "Default")
      (node (ref "U1") (pin "38") (pinfunction "P31_38") (pintype "bidirectional"))
      (node (ref "U2") (pin "1") (pinfunction "TXD_1") (pintype "bidirectional"))
    )
    (net (code "293") (name "/USBD+") (class "Default")
      (node (ref "IC2") (pin "57") (pinfunction "D+/RG2_57") (pintype "bidirectional"))
    )
    (net (code "294") (name "/USBD-") (class "Default")
      (node (ref "IC2") (pin "56") (pinfunction "D-/RG3_56") (pintype "bidirectional"))
    )
    (net (code "295") (name "/USBDM") (class "Default")
      (node (ref "R180") (pin "1") (pinfunction "1_1") (pintype "passive"))
      (node (ref "U2") (pin "9") (pinfunction "USBDM_9") (pintype "bidirectional"))
    )
    (net (code "296") (name "/USBDP") (class "Default")
      (node (ref "R181") (pin "1") (pinfunction "1_1") (pintype "passive"))
      (node (ref "U2") (pin "8") (pinfunction "USBDP_8") (pintype "bidirectional"))
    )
    (net (code "297") (name "/USB_BUS") (class "Default")
      (node (ref "C12") (pin "1") (pinfunction "1_1") (pintype "passive"))
      (node (ref "C18") (pin "1") (pinfunction "1_1") (pintype "passive"))
      (node (ref "IC1") (pin "20") (pinfunction "VCC_20") (pintype "bidirectional"))
      (node (ref "J1") (pin "5V") (pinfunction "5V_5V") (pintype "bidirectional"))
      (node (ref "PIC_USB") (pin "ANODE") (pinfunction "ANODE_ANODE") (pintype "bidirectional"))
    )
    (net (code "298") (name "/USER_0") (class "Default")
      (node (ref "CABINET") (pin "P$10") (pinfunction "10_P$10") (pintype "bidirectional"))
      (node (ref "R44") (pin "1") (pinfunction "1_1") (pintype "passive"))
      (node (ref "U12") (pin "12") (pinfunction "D1_12") (pintype "bidirectional"))
    )
    (net (code "299") (name "/VBUS_PROP") (class "Default")
      (node (ref "C15") (pin "1") (pinfunction "1_1") (pintype "passive"))
      (node (ref "J2") (pin "5V") (pinfunction "5V_5V") (pintype "bidirectional"))
      (node (ref "PROP_RX") (pin "ANODE") (pinfunction "ANODE_ANODE") (pintype "bidirectional"))
      (node (ref "PROP_TX") (pin "ANODE") (pinfunction "ANODE_ANODE") (pintype "bidirectional"))
      (node (ref "PROP_USB") (pin "ANODE") (pinfunction "ANODE_ANODE") (pintype "bidirectional"))
      (node (ref "U2") (pin "12") (pinfunction "VCC_12") (pintype "bidirectional"))
    )
    (net (code "300") (name "/VUSB") (class "Default")
      (node (ref "IC2") (pin "54") (pinfunction "VBUS_54") (pintype "bidirectional"))
    )
    (net (code "301") (name "/WATCHDOG") (class "Default")
      (node (ref "J3") (pin "1") (pinfunction "1_1") (pintype "passive"))
      (node (ref "R135") (pin "1") (pinfunction "1_1") (pintype "passive"))
      (node (ref "U10") (pin "3") (pinfunction "2A_3") (pintype "bidirectional"))
      (node (ref "U14") (pin "1") (pinfunction "A1_1") (pintype "bidirectional"))
      (node (ref "U14") (pin "12") (pinfunction "A4_12") (pintype "bidirectional"))
      (node (ref "U14") (pin "4") (pinfunction "A2_4") (pintype "bidirectional"))
      (node (ref "U14") (pin "9") (pinfunction "A3_9") (pintype "bidirectional"))
      (node (ref "U15") (pin "1") (pinfunction "A1_1") (pintype "bidirectional"))
      (node (ref "U15") (pin "12") (pinfunction "A4_12") (pintype "bidirectional"))
      (node (ref "U15") (pin "4") (pinfunction "A2_4") (pintype "bidirectional"))
      (node (ref "U15") (pin "9") (pinfunction "A3_9") (pintype "bidirectional"))
      (node (ref "U16") (pin "1") (pinfunction "A1_1") (pintype "bidirectional"))
      (node (ref "U16") (pin "12") (pinfunction "A4_12") (pintype "bidirectional"))
      (node (ref "U16") (pin "4") (pinfunction "A2_4") (pintype "bidirectional"))
      (node (ref "U16") (pin "9") (pinfunction "A3_9") (pintype "bidirectional"))
      (node (ref "U17") (pin "1") (pinfunction "A1_1") (pintype "bidirectional"))
      (node (ref "U17") (pin "12") (pinfunction "A4_12") (pintype "bidirectional"))
      (node (ref "U17") (pin "4") (pinfunction "A2_4") (pintype "bidirectional"))
      (node (ref "U17") (pin "9") (pinfunction "A3_9") (pintype "bidirectional"))
      (node (ref "U18") (pin "1") (pinfunction "A1_1") (pintype "bidirectional"))
      (node (ref "U18") (pin "12") (pinfunction "A4_12") (pintype "bidirectional"))
      (node (ref "U18") (pin "4") (pinfunction "A2_4") (pintype "bidirectional"))
      (node (ref "U18") (pin "9") (pinfunction "A3_9") (pintype "bidirectional"))
      (node (ref "U19") (pin "1") (pinfunction "A1_1") (pintype "bidirectional"))
      (node (ref "U19") (pin "12") (pinfunction "A4_12") (pintype "bidirectional"))
      (node (ref "U19") (pin "4") (pinfunction "A2_4") (pintype "bidirectional"))
      (node (ref "U19") (pin "9") (pinfunction "A3_9") (pintype "bidirectional"))
      (node (ref "U52") (pin "13") (pinfunction "1Q_13") (pintype "bidirectional"))
      (node (ref "WD") (pin "ANODE") (pinfunction "ANODE_ANODE") (pintype "bidirectional"))
    )
    (net (code "302") (name "/WATCHDOG_ADJUST") (class "Default")
      (node (ref "C27") (pin "POS") (pinfunction "POS_POS") (pintype "bidirectional"))
      (node (ref "D2") (pin "2") (pinfunction "ANODE_2") (pintype "bidirectional"))
      (node (ref "P1") (pin "3") (pinfunction "3_CW_3") (pintype "bidirectional"))
      (node (ref "U52") (pin "15") (pinfunction "1RXCX_15") (pintype "bidirectional"))
    )
    (net (code "303") (name "/X0") (class "Default")
      (node (ref "U1") (pin "29") (pinfunction "X0_29") (pintype "bidirectional"))
      (node (ref "X2") (pin "P$1") (pinfunction "P$1_P$1") (pintype "bidirectional"))
    )
    (net (code "304") (name "/X1") (class "Default")
      (node (ref "U1") (pin "28") (pinfunction "X1_28") (pintype "bidirectional"))
      (node (ref "X2") (pin "P$2") (pinfunction "P$2_P$2") (pintype "bidirectional"))
    )
    (net (code "305") (name "/~{AN_BLANK}") (class "Default")
      (node (ref "J3") (pin "4") (pinfunction "4_4") (pintype "passive"))
      (node (ref "U10") (pin "4") (pinfunction "2Y_4") (pintype "bidirectional"))
    )
    (net (code "306") (name "/~{DATA_LAT}") (class "Default")
      (node (ref "U10") (pin "6") (pinfunction "1Y_6") (pintype "bidirectional"))
      (node (ref "U3") (pin "12") (pinfunction "STCP_12") (pintype "bidirectional"))
      (node (ref "U5") (pin "12") (pinfunction "STCP_12") (pintype "bidirectional"))
    )
    (net (code "307") (name "Net-(D1-COM)") (class "Default")
      (node (ref "D1") (pin "3") (pinfunction "COM_3") (pintype "bidirectional"))
      (node (ref "IC2") (pin "13") (pinfunction "MCLR_13") (pintype "bidirectional"))
      (node (ref "R12") (pin "1") (pinfunction "1_1") (pintype "passive"))
    )
    (net (code "308") (name "Net-(D8-D3)") (class "Default")
      (node (ref "D8") (pin "4") (pinfunction "D3_4") (pintype "bidirectional"))
      (node (ref "J11") (pin "4") (pinfunction "4_4") (pintype "passive"))
      (node (ref "R13") (pin "2") (pinfunction "2_2") (pintype "passive"))
    )
    (net (code "309") (name "Net-(D8-D4)") (class "Default")
      (node (ref "D8") (pin "5") (pinfunction "D4_5") (pintype "bidirectional"))
      (node (ref "J11") (pin "5") (pinfunction "5_5") (pintype "passive"))
      (node (ref "R14") (pin "2") (pinfunction "2_2") (pintype "passive"))
    )
    (net (code "310") (name "Net-(IC1-CBUS0)") (class "Default")
      (node (ref "IC1") (pin "23") (pinfunction "CBUS0_23") (pintype "bidirectional"))
      (node (ref "R7") (pin "1") (pinfunction "1_1") (pintype "passive"))
    )
    (net (code "311") (name "Net-(IC1-CBUS1)") (class "Default")
      (node (ref "IC1") (pin "22") (pinfunction "CBUS1_22") (pintype "bidirectional"))
      (node (ref "R9") (pin "1") (pinfunction "1_1") (pintype "passive"))
    )
    (net (code "312") (name "Net-(IC1-DTR#)") (class "Default")
      (node (ref "C1") (pin "1") (pinfunction "1_1") (pintype "passive"))
      (node (ref "IC1") (pin "2") (pinfunction "DTR#_2") (pintype "bidirectional"))
    )
    (net (code "313") (name "Net-(IC1-RTS#)") (class "Default")
      (node (ref "IC1") (pin "3") (pinfunction "RTS#_3") (pintype "bidirectional"))
      (node (ref "R10") (pin "1") (pinfunction "1_1") (pintype "passive"))
    )
    (net (code "314") (name "Net-(IC1-RXD)") (class "Default")
      (node (ref "IC1") (pin "5") (pinfunction "RXD_5") (pintype "bidirectional"))
      (node (ref "R1") (pin "1") (pinfunction "1_1") (pintype "passive"))
    )
    (net (code "315") (name "Net-(IC1-TXD)") (class "Default")
      (node (ref "IC1") (pin "1") (pinfunction "TXD_1") (pintype "bidirectional"))
      (node (ref "R2") (pin "1") (pinfunction "1_1") (pintype "passive"))
    )
    (net (code "316") (name "Net-(IC2A-VCAP{slash}VDDCORE)") (class "Default")
      (node (ref "C10") (pin "1") (pinfunction "1_1") (pintype "passive"))
      (node (ref "IC2") (pin "85") (pinfunction "VCAP/VDDCORE_85") (pintype "bidirectional"))
    )
    (net (code "317") (name "Net-(IC2D-OSC1{slash}CLKI{slash}RC12)") (class "Default")
      (node (ref "C14") (pin "1") (pinfunction "1_1") (pintype "passive"))
      (node (ref "IC2") (pin "63") (pinfunction "OSC1/CLKI/RC12_63") (pintype "bidirectional"))
      (node (ref "X1") (pin "3") (pinfunction "2_3") (pintype "passive"))
    )
    (net (code "318") (name "Net-(IC2D-OSC2{slash}CLKO{slash}RC15)") (class "Default")
      (node (ref "C13") (pin "1") (pinfunction "1_1") (pintype "passive"))
      (node (ref "IC2") (pin "64") (pinfunction "OSC2/CLKO/RC15_64") (pintype "bidirectional"))
      (node (ref "X1") (pin "1") (pinfunction "1_1") (pintype "passive"))
    )
    (net (code "319") (name "Net-(P1-2_WIPER)") (class "Default")
      (node (ref "P1") (pin "2") (pinfunction "2_WIPER_2") (pintype "bidirectional"))
      (node (ref "R134") (pin "1") (pinfunction "1_1") (pintype "passive"))
    )
    (net (code "320") (name "Net-(PIC_RX-PadCATHODE)") (class "Default")
      (node (ref "PIC_RX") (pin "CATHODE") (pinfunction "CATHODE_CATHODE") (pintype "bidirectional"))
      (node (ref "R9") (pin "2") (pinfunction "2_2") (pintype "passive"))
    )
    (net (code "321") (name "Net-(PIC_TX-PadCATHODE)") (class "Default")
      (node (ref "PIC_TX") (pin "CATHODE") (pinfunction "CATHODE_CATHODE") (pintype "bidirectional"))
      (node (ref "R7") (pin "2") (pinfunction "2_2") (pintype "passive"))
    )
    (net (code "322") (name "Net-(PIC_USB-PadCATHODE)") (class "Default")
      (node (ref "PIC_USB") (pin "CATHODE") (pinfunction "CATHODE_CATHODE") (pintype "bidirectional"))
      (node (ref "R11") (pin "2") (pinfunction "2_2") (pintype "passive"))
    )
    (net (code "323") (name "Net-(PROP_ACT-PadCATHODE)") (class "Default")
      (node (ref "PROP_ACT") (pin "CATHODE") (pinfunction "CATHODE_CATHODE") (pintype "bidirectional"))
      (node (ref "R30") (pin "2") (pinfunction "2_2") (pintype "passive"))
    )
    (net (code "324") (name "Net-(PROP_RX-PadCATHODE)") (class "Default")
      (node (ref "PROP_RX") (pin "CATHODE") (pinfunction "CATHODE_CATHODE") (pintype "bidirectional"))
      (node (ref "R6") (pin "2") (pinfunction "2_2") (pintype "passive"))
    )
    (net (code "325") (name "Net-(PROP_TX-PadCATHODE)") (class "Default")
      (node (ref "PROP_TX") (pin "CATHODE") (pinfunction "CATHODE_CATHODE") (pintype "bidirectional"))
      (node (ref "R15") (pin "2") (pinfunction "2_2") (pintype "passive"))
    )
    (net (code "326") (name "Net-(PROP_USB-PadCATHODE)") (class "Default")
      (node (ref "PROP_USB") (pin "CATHODE") (pinfunction "CATHODE_CATHODE") (pintype "bidirectional"))
      (node (ref "R5") (pin "2") (pinfunction "2_2") (pintype "passive"))
    )
    (net (code "327") (name "Net-(PSU_PWR-PadCATHODE)") (class "Default")
      (node (ref "PSU_PWR") (pin "CATHODE") (pinfunction "CATHODE_CATHODE") (pintype "bidirectional"))
      (node (ref "R117") (pin "2") (pinfunction "2_2") (pintype "passive"))
    )
    (net (code "328") (name "Net-(R8-Pad1)") (class "Default")
      (node (ref "R8") (pin "1") (pinfunction "1_1") (pintype "passive"))
      (node (ref "SW1") (pin "P$3") (pinfunction "P$3_P$3") (pintype "bidirectional"))
    )
    (net (code "329") (name "Net-(R118-Pad1)") (class "Default")
      (node (ref "R118") (pin "1") (pinfunction "1_1") (pintype "passive"))
      (node (ref "WD") (pin "CATHODE") (pinfunction "CATHODE_CATHODE") (pintype "bidirectional"))
    )
    (net (code "330") (name "Net-(RGB_0-GATE)") (class "Default")
      (node (ref "R119") (pin "1") (pinfunction "1_1") (pintype "passive"))
      (node (ref "RGB_0") (pin "G") (pinfunction "GATE_G") (pintype "bidirectional"))
      (node (ref "U38") (pin "8") (pinfunction "BOUT_8") (pintype "bidirectional"))
    )
    (net (code "331") (name "Net-(RGB_1-GATE)") (class "Default")
      (node (ref "R120") (pin "1") (pinfunction "1_1") (pintype "passive"))
      (node (ref "RGB_1") (pin "G") (pinfunction "GATE_G") (pintype "bidirectional"))
      (node (ref "U38") (pin "9") (pinfunction "GOUT_9") (pintype "bidirectional"))
    )
    (net (code "332") (name "Net-(RGB_2-GATE)") (class "Default")
      (node (ref "R121") (pin "1") (pinfunction "1_1") (pintype "passive"))
      (node (ref "RGB_2") (pin "G") (pinfunction "GATE_G") (pintype "bidirectional"))
      (node (ref "U38") (pin "10") (pinfunction "ROUT_10") (pintype "bidirectional"))
    )
    (net (code "333") (name "Net-(RGB_3-GATE)") (class "Default")
      (node (ref "R122") (pin "1") (pinfunction "1_1") (pintype "passive"))
      (node (ref "RGB_3") (pin "G") (pinfunction "GATE_G") (pintype "bidirectional"))
      (node (ref "U36") (pin "8") (pinfunction "BOUT_8") (pintype "bidirectional"))
    )
    (net (code "334") (name "Net-(RGB_4-GATE)") (class "Default")
      (node (ref "R123") (pin "1") (pinfunction "1_1") (pintype "passive"))
      (node (ref "RGB_4") (pin "G") (pinfunction "GATE_G") (pintype "bidirectional"))
      (node (ref "U36") (pin "9") (pinfunction "GOUT_9") (pintype "bidirectional"))
    )
    (net (code "335") (name "Net-(RGB_5-GATE)") (class "Default")
      (node (ref "R124") (pin "1") (pinfunction "1_1") (pintype "passive"))
      (node (ref "RGB_5") (pin "G") (pinfunction "GATE_G") (pintype "bidirectional"))
      (node (ref "U36") (pin "10") (pinfunction "ROUT_10") (pintype "bidirectional"))
    )
    (net (code "336") (name "Net-(SD0-IRQ)") (class "Default")
      (node (ref "R21") (pin "2") (pinfunction "2_2") (pintype "passive"))
      (node (ref "SD0") (pin "8") (pinfunction "IRQ_8") (pintype "bidirectional"))
    )
    (net (code "337") (name "Net-(SD0-RW)") (class "Default")
      (node (ref "R23") (pin "2") (pinfunction "2_2") (pintype "passive"))
      (node (ref "SD0") (pin "9") (pinfunction "RW_9") (pintype "bidirectional"))
    )
    (net (code "338") (name "Net-(U6-BASE)") (class "Default")
      (node (ref "R99") (pin "2") (pinfunction "2_2") (pintype "passive"))
      (node (ref "U6") (pin "G") (pinfunction "BASE_G") (pintype "bidirectional"))
    )
    (net (code "339") (name "Net-(U7-BASE)") (class "Default")
      (node (ref "R101") (pin "2") (pinfunction "2_2") (pintype "passive"))
      (node (ref "U7") (pin "G") (pinfunction "BASE_G") (pintype "bidirectional"))
    )
    (net (code "340") (name "Net-(U8-BASE)") (class "Default")
      (node (ref "R103") (pin "2") (pinfunction "2_2") (pintype "passive"))
      (node (ref "U8") (pin "G") (pinfunction "BASE_G") (pintype "bidirectional"))
    )
    (net (code "341") (name "Net-(U9-BASE)") (class "Default")
      (node (ref "R105") (pin "2") (pinfunction "2_2") (pintype "passive"))
      (node (ref "U9") (pin "G") (pinfunction "BASE_G") (pintype "bidirectional"))
    )
    (net (code "342") (name "Net-(U28-BASE)") (class "Default")
      (node (ref "R100") (pin "2") (pinfunction "2_2") (pintype "passive"))
      (node (ref "U28") (pin "G") (pinfunction "BASE_G") (pintype "bidirectional"))
    )
    (net (code "343") (name "Net-(U29-BASE)") (class "Default")
      (node (ref "R102") (pin "2") (pinfunction "2_2") (pintype "passive"))
      (node (ref "U29") (pin "G") (pinfunction "BASE_G") (pintype "bidirectional"))
    )
    (net (code "344") (name "Net-(U30-BASE)") (class "Default")
      (node (ref "R104") (pin "2") (pinfunction "2_2") (pintype "passive"))
      (node (ref "U30") (pin "G") (pinfunction "BASE_G") (pintype "bidirectional"))
    )
    (net (code "345") (name "Net-(U31-BASE)") (class "Default")
      (node (ref "R106") (pin "2") (pinfunction "2_2") (pintype "passive"))
      (node (ref "U31") (pin "G") (pinfunction "BASE_G") (pintype "bidirectional"))
    )
    (net (code "346") (name "Net-(U32-BASE)") (class "Default")
      (node (ref "R108") (pin "2") (pinfunction "2_2") (pintype "passive"))
      (node (ref "U32") (pin "G") (pinfunction "BASE_G") (pintype "bidirectional"))
    )
    (net (code "347") (name "Net-(U33-BASE)") (class "Default")
      (node (ref "R110") (pin "2") (pinfunction "2_2") (pintype "passive"))
      (node (ref "U33") (pin "G") (pinfunction "BASE_G") (pintype "bidirectional"))
    )
    (net (code "348") (name "Net-(U34-BASE)") (class "Default")
      (node (ref "R112") (pin "2") (pinfunction "2_2") (pintype "passive"))
      (node (ref "U34") (pin "G") (pinfunction "BASE_G") (pintype "bidirectional"))
    )
    (net (code "349") (name "Net-(U35-BASE)") (class "Default")
      (node (ref "R114") (pin "2") (pinfunction "2_2") (pintype "passive"))
      (node (ref "U35") (pin "G") (pinfunction "BASE_G") (pintype "bidirectional"))
    )
    (net (code "350") (name "Net-(U37-BASE)") (class "Default")
      (node (ref "R115") (pin "2") (pinfunction "2_2") (pintype "passive"))
      (node (ref "R116") (pin "1") (pinfunction "1_1") (pintype "passive"))
      (node (ref "U37") (pin "G") (pinfunction "BASE_G") (pintype "bidirectional"))
    )
    (net (code "351") (name "Net-(U40-BASE)") (class "Default")
      (node (ref "R107") (pin "2") (pinfunction "2_2") (pintype "passive"))
      (node (ref "U40") (pin "G") (pinfunction "BASE_G") (pintype "bidirectional"))
    )
    (net (code "352") (name "Net-(U41-BASE)") (class "Default")
      (node (ref "R109") (pin "2") (pinfunction "2_2") (pintype "passive"))
      (node (ref "U41") (pin "G") (pinfunction "BASE_G") (pintype "bidirectional"))
    )
    (net (code "353") (name "Net-(U42-BASE)") (class "Default")
      (node (ref "R111") (pin "2") (pinfunction "2_2") (pintype "passive"))
      (node (ref "U42") (pin "G") (pinfunction "BASE_G") (pintype "bidirectional"))
    )
    (net (code "354") (name "Net-(U43-BASE)") (class "Default")
      (node (ref "R113") (pin "2") (pinfunction "2_2") (pintype "passive"))
      (node (ref "U43") (pin "G") (pinfunction "BASE_G") (pintype "bidirectional"))
    )
    (net (code "355") (name "Net-(U44-BASE)") (class "Default")
      (node (ref "R125") (pin "2") (pinfunction "2_2") (pintype "passive"))
      (node (ref "U44") (pin "G") (pinfunction "BASE_G") (pintype "bidirectional"))
    )
    (net (code "356") (name "Net-(U45-BASE)") (class "Default")
      (node (ref "R126") (pin "2") (pinfunction "2_2") (pintype "passive"))
      (node (ref "U45") (pin "G") (pinfunction "BASE_G") (pintype "bidirectional"))
    )
    (net (code "357") (name "Net-(U46-BASE)") (class "Default")
      (node (ref "R127") (pin "2") (pinfunction "2_2") (pintype "passive"))
      (node (ref "U46") (pin "G") (pinfunction "BASE_G") (pintype "bidirectional"))
    )
    (net (code "358") (name "Net-(U47-BASE)") (class "Default")
      (node (ref "R128") (pin "2") (pinfunction "2_2") (pintype "passive"))
      (node (ref "U47") (pin "G") (pinfunction "BASE_G") (pintype "bidirectional"))
    )
    (net (code "359") (name "Net-(U48-BASE)") (class "Default")
      (node (ref "R129") (pin "2") (pinfunction "2_2") (pintype "passive"))
      (node (ref "U48") (pin "G") (pinfunction "BASE_G") (pintype "bidirectional"))
    )
    (net (code "360") (name "Net-(U49-BASE)") (class "Default")
      (node (ref "R130") (pin "2") (pinfunction "2_2") (pintype "passive"))
      (node (ref "U49") (pin "G") (pinfunction "BASE_G") (pintype "bidirectional"))
    )
    (net (code "361") (name "Net-(U50-BASE)") (class "Default")
      (node (ref "R131") (pin "2") (pinfunction "2_2") (pintype "passive"))
      (node (ref "U50") (pin "G") (pinfunction "BASE_G") (pintype "bidirectional"))
    )
    (net (code "362") (name "Net-(U51-BASE)") (class "Default")
      (node (ref "R132") (pin "2") (pinfunction "2_2") (pintype "passive"))
      (node (ref "U51") (pin "G") (pinfunction "BASE_G") (pintype "bidirectional"))
    )
    (net (code "363") (name "unconnected-(BOARD_POWER-Pad7)") (class "Default")
      (node (ref "BOARD_POWER") (pin "7") (pinfunction "7_7") (pintype "bidirectional"))
    )
    (net (code "364") (name "unconnected-(BT1-AIO1-Pad35)") (class "Default")
      (node (ref "BT1") (pin "35") (pinfunction "AIO1_35") (pintype "bidirectional"))
    )
    (net (code "365") (name "unconnected-(BT1-AIO2-Pad30)") (class "Default")
      (node (ref "BT1") (pin "30") (pinfunction "AIO2_30") (pintype "bidirectional"))
    )
    (net (code "366") (name "unconnected-(BT1-NC-Pad26)") (class "Default")
      (node (ref "BT1") (pin "26") (pinfunction "NC_26") (pintype "bidirectional"))
    )
    (net (code "367") (name "unconnected-(BT1-PCMCLK-Pad7)") (class "Default")
      (node (ref "BT1") (pin "7") (pinfunction "PCMCLK_7") (pintype "bidirectional"))
    )
    (net (code "368") (name "unconnected-(BT1-PCMIN-Pad9)") (class "Default")
      (node (ref "BT1") (pin "9") (pinfunction "PCMIN_9") (pintype "bidirectional"))
    )
    (net (code "369") (name "unconnected-(BT1-PCMOUT-Pad10)") (class "Default")
      (node (ref "BT1") (pin "10") (pinfunction "PCMOUT_10") (pintype "bidirectional"))
    )
    (net (code "370") (name "unconnected-(BT1-PCMSYNC-Pad8)") (class "Default")
      (node (ref "BT1") (pin "8") (pinfunction "PCMSYNC_8") (pintype "bidirectional"))
    )
    (net (code "371") (name "unconnected-(BT1-PIO2-Pad19)") (class "Default")
      (node (ref "BT1") (pin "19") (pinfunction "PIO2_19") (pintype "bidirectional"))
    )
    (net (code "372") (name "unconnected-(BT1-PIO3-Pad20)") (class "Default")
      (node (ref "BT1") (pin "20") (pinfunction "PIO3_20") (pintype "bidirectional"))
    )
    (net (code "373") (name "unconnected-(BT1-PIO4-Pad22)") (class "Default")
      (node (ref "BT1") (pin "22") (pinfunction "PIO4_22") (pintype "bidirectional"))
    )
    (net (code "374") (name "unconnected-(BT1-PIO5-Pad21)") (class "Default")
      (node (ref "BT1") (pin "21") (pinfunction "PIO5_21") (pintype "bidirectional"))
    )
    (net (code "375") (name "unconnected-(BT1-PIO6-Pad3)") (class "Default")
      (node (ref "BT1") (pin "3") (pinfunction "PIO6_3") (pintype "bidirectional"))
    )
    (net (code "376") (name "unconnected-(BT1-PIO7-Pad4)") (class "Default")
      (node (ref "BT1") (pin "4") (pinfunction "PIO7_4") (pintype "bidirectional"))
    )
    (net (code "377") (name "unconnected-(BT1-PIO8-Pad31)") (class "Default")
      (node (ref "BT1") (pin "31") (pinfunction "PIO8_31") (pintype "bidirectional"))
    )
    (net (code "378") (name "unconnected-(BT1-PIO9-Pad32)") (class "Default")
      (node (ref "BT1") (pin "32") (pinfunction "PIO9_32") (pintype "bidirectional"))
    )
    (net (code "379") (name "unconnected-(BT1-PIO10-Pad33)") (class "Default")
      (node (ref "BT1") (pin "33") (pinfunction "PIO10_33") (pintype "bidirectional"))
    )
    (net (code "380") (name "unconnected-(BT1-PIO11-Pad34)") (class "Default")
      (node (ref "BT1") (pin "34") (pinfunction "PIO11_34") (pintype "bidirectional"))
    )
    (net (code "381") (name "unconnected-(BT1-SPICLK-Pad6)") (class "Default")
      (node (ref "BT1") (pin "6") (pinfunction "SPICLK_6") (pintype "bidirectional"))
    )
    (net (code "382") (name "unconnected-(BT1-SPICSB-Pad23)") (class "Default")
      (node (ref "BT1") (pin "23") (pinfunction "SPICSB_23") (pintype "bidirectional"))
    )
    (net (code "383") (name "unconnected-(BT1-SPIMISO-Pad24)") (class "Default")
      (node (ref "BT1") (pin "24") (pinfunction "SPIMISO_24") (pintype "bidirectional"))
    )
    (net (code "384") (name "unconnected-(BT1-SPIMOSI-Pad2)") (class "Default")
      (node (ref "BT1") (pin "2") (pinfunction "SPIMOSI_2") (pintype "bidirectional"))
    )
    (net (code "385") (name "unconnected-(BT1-UARTCTS-Pad16)") (class "Default")
      (node (ref "BT1") (pin "16") (pinfunction "UARTCTS_16") (pintype "bidirectional"))
    )
    (net (code "386") (name "unconnected-(BT1-UARTRTS-Pad15)") (class "Default")
      (node (ref "BT1") (pin "15") (pinfunction "UARTRTS_15") (pintype "bidirectional"))
    )
    (net (code "387") (name "unconnected-(BT1-USBD+-Pad17)") (class "Default")
      (node (ref "BT1") (pin "17") (pinfunction "USBD+_17") (pintype "bidirectional"))
    )
    (net (code "388") (name "unconnected-(BT1-USBD--Pad18)") (class "Default")
      (node (ref "BT1") (pin "18") (pinfunction "USBD-_18") (pintype "bidirectional"))
    )
    (net (code "389") (name "unconnected-(D8-D1-Pad1)") (class "Default")
      (node (ref "D8") (pin "1") (pinfunction "D1_1") (pintype "bidirectional"))
    )
    (net (code "390") (name "unconnected-(IC1-CBUS2-Pad13)") (class "Default")
      (node (ref "IC1") (pin "13") (pinfunction "CBUS2_13") (pintype "bidirectional"))
    )
    (net (code "391") (name "unconnected-(IC1-CBUS3-Pad14)") (class "Default")
      (node (ref "IC1") (pin "14") (pinfunction "CBUS3_14") (pintype "bidirectional"))
    )
    (net (code "392") (name "unconnected-(IC1-CBUS4-Pad12)") (class "Default")
      (node (ref "IC1") (pin "12") (pinfunction "CBUS4_12") (pintype "bidirectional"))
    )
    (net (code "393") (name "unconnected-(IC1-CTS#-Pad11)") (class "Default")
      (node (ref "IC1") (pin "11") (pinfunction "CTS#_11") (pintype "bidirectional"))
    )
    (net (code "394") (name "unconnected-(IC1-DCD#-Pad10)") (class "Default")
      (node (ref "IC1") (pin "10") (pinfunction "DCD#_10") (pintype "bidirectional"))
    )
    (net (code "395") (name "unconnected-(IC1-DSR#-Pad9)") (class "Default")
      (node (ref "IC1") (pin "9") (pinfunction "DSR#_9") (pintype "bidirectional"))
    )
    (net (code "396") (name "unconnected-(IC1-OSCI-Pad27)") (class "Default")
      (node (ref "IC1") (pin "27") (pinfunction "OSCI_27") (pintype "bidirectional"))
    )
    (net (code "397") (name "unconnected-(IC1-OSCO-Pad28)") (class "Default")
      (node (ref "IC1") (pin "28") (pinfunction "OSCO_28") (pintype "bidirectional"))
    )
    (net (code "398") (name "unconnected-(IC1-RI#-Pad6)") (class "Default")
      (node (ref "IC1") (pin "6") (pinfunction "RI#_6") (pintype "bidirectional"))
    )
    (net (code "399") (name "unconnected-(IC5-CD+-Pad10)") (class "Default")
      (node (ref "IC5") (pin "10") (pinfunction "CD+_10") (pintype "passive"))
    )
    (net (code "400") (name "unconnected-(J1-PadID)") (class "Default")
      (node (ref "J1") (pin "ID") (pinfunction "ID_ID") (pintype "bidirectional"))
    )
    (net (code "401") (name "unconnected-(J2-PadID)") (class "Default")
      (node (ref "J2") (pin "ID") (pinfunction "ID_ID") (pintype "bidirectional"))
    )
    (net (code "402") (name "unconnected-(J11-Pad6)") (class "Default")
      (node (ref "J11") (pin "6") (pinfunction "6_6") (pintype "passive"))
    )
    (net (code "403") (name "unconnected-(LIGHT_COL-2-PadP$2)") (class "Default")
      (node (ref "LIGHT_COL") (pin "P$2") (pinfunction "2_P$2") (pintype "bidirectional"))
    )
    (net (code "404") (name "unconnected-(LIGHT_ROW-3-PadP$3)") (class "Default")
      (node (ref "LIGHT_ROW") (pin "P$3") (pinfunction "3_P$3") (pintype "bidirectional"))
    )
    (net (code "405") (name "unconnected-(P1-1_CCW-Pad1)") (class "Default")
      (node (ref "P1") (pin "1") (pinfunction "1_CCW_1") (pintype "bidirectional"))
    )
    (net (code "406") (name "unconnected-(SOL_BANK_0-6-PadP$6)") (class "Default")
      (node (ref "SOL_BANK_0") (pin "P$6") (pinfunction "6_P$6") (pintype "bidirectional"))
    )
    (net (code "407") (name "unconnected-(SOL_BANK_1-7-PadP$7)") (class "Default")
      (node (ref "SOL_BANK_1") (pin "P$7") (pinfunction "7_P$7") (pintype "bidirectional"))
    )
    (net (code "408") (name "unconnected-(SOL_BANK_2-8-PadP$8)") (class "Default")
      (node (ref "SOL_BANK_2") (pin "P$8") (pinfunction "8_P$8") (pintype "bidirectional"))
    )
    (net (code "409") (name "unconnected-(SW1-PadP$2)") (class "Default")
      (node (ref "SW1") (pin "P$2") (pinfunction "P$2_P$2") (pintype "bidirectional"))
    )
    (net (code "410") (name "unconnected-(SW1-PadP$4)") (class "Default")
      (node (ref "SW1") (pin "P$4") (pinfunction "P$4_P$4") (pintype "bidirectional"))
    )
    (net (code "411") (name "unconnected-(SW2-PadP$1)") (class "Default")
      (node (ref "SW2") (pin "P$1") (pinfunction "P$1_P$1") (pintype "bidirectional"))
    )
    (net (code "412") (name "unconnected-(SW2-PadP$3)") (class "Default")
      (node (ref "SW2") (pin "P$3") (pinfunction "P$3_P$3") (pintype "bidirectional"))
    )
    (net (code "413") (name "unconnected-(SW3-PadP$3)") (class "Default")
      (node (ref "SW3") (pin "P$3") (pinfunction "P$3_P$3") (pintype "bidirectional"))
    )
    (net (code "414") (name "unconnected-(SW_COL-5-PadP$5)") (class "Default")
      (node (ref "SW_COL") (pin "P$5") (pinfunction "5_P$5") (pintype "bidirectional"))
    )
    (net (code "415") (name "unconnected-(SW_ROW-4-PadP$4)") (class "Default")
      (node (ref "SW_ROW") (pin "P$4") (pinfunction "4_P$4") (pintype "bidirectional"))
    )
    (net (code "416") (name "unconnected-(U2-CBUS0-Pad15)") (class "Default")
      (node (ref "U2") (pin "15") (pinfunction "CBUS0_15") (pintype "bidirectional"))
    )
    (net (code "417") (name "unconnected-(U2-CBUS3-Pad16)") (class "Default")
      (node (ref "U2") (pin "16") (pinfunction "CBUS3_16") (pintype "bidirectional"))
    )
    (net (code "418") (name "unconnected-(U2-CTS#-Pad6)") (class "Default")
      (node (ref "U2") (pin "6") (pinfunction "CTS#_6") (pintype "bidirectional"))
    )
    (net (code "419") (name "unconnected-(U5-Q7S-Pad9)") (class "Default")
      (node (ref "U5") (pin "9") (pinfunction "Q7S_9") (pintype "bidirectional"))
    )
    (net (code "420") (name "unconnected-(U11-QH'-Pad7)") (class "Default")
      (node (ref "U11") (pin "7") (pinfunction "QH'_7") (pintype "bidirectional"))
    )
    (net (code "421") (name "unconnected-(U12-QH'-Pad7)") (class "Default")
      (node (ref "U12") (pin "7") (pinfunction "QH'_7") (pintype "bidirectional"))
    )
    (net (code "422") (name "unconnected-(U12-SER-Pad10)") (class "Default")
      (node (ref "U12") (pin "10") (pinfunction "SER_10") (pintype "bidirectional"))
    )
    (net (code "423") (name "unconnected-(U52-2B-Pad10)") (class "Default")
      (node (ref "U52") (pin "10") (pinfunction "2B_10") (pintype "bidirectional"))
    )
    (net (code "424") (name "unconnected-(U52-2CX-Pad6)") (class "Default")
      (node (ref "U52") (pin "6") (pinfunction "2CX_6") (pintype "bidirectional"))
    )
    (net (code "425") (name "unconnected-(U52-2Q-Pad5)") (class "Default")
      (node (ref "U52") (pin "5") (pinfunction "2Q_5") (pintype "bidirectional"))
    )
    (net (code "426") (name "unconnected-(U52-2RXCX-Pad7)") (class "Default")
      (node (ref "U52") (pin "7") (pinfunction "2RXCX_7") (pintype "bidirectional"))
    )
    (net (code "427") (name "unconnected-(U52-~{1Q}-Pad4)") (class "Default")
      (node (ref "U52") (pin "4") (pinfunction "~{1Q}_4") (pintype "bidirectional"))
    )
    (net (code "428") (name "unconnected-(U52-~{2A}-Pad9)") (class "Default")
      (node (ref "U52") (pin "9") (pinfunction "~{2A}_9") (pintype "bidirectional"))
    )
    (net (code "429") (name "unconnected-(U52-~{2Q}-Pad12)") (class "Default")
      (node (ref "U52") (pin "12") (pinfunction "~{2Q}_12") (pintype "bidirectional"))
    )
    (net (code "430") (name "unconnected-(U52-~{2R}-Pad11)") (class "Default")
      (node (ref "U52") (pin "11") (pinfunction "~{2R}_11") (pintype "bidirectional"))
    )
  )
)
